# rt10.net
KiCad netlist of a schematic drawn in EAGLE
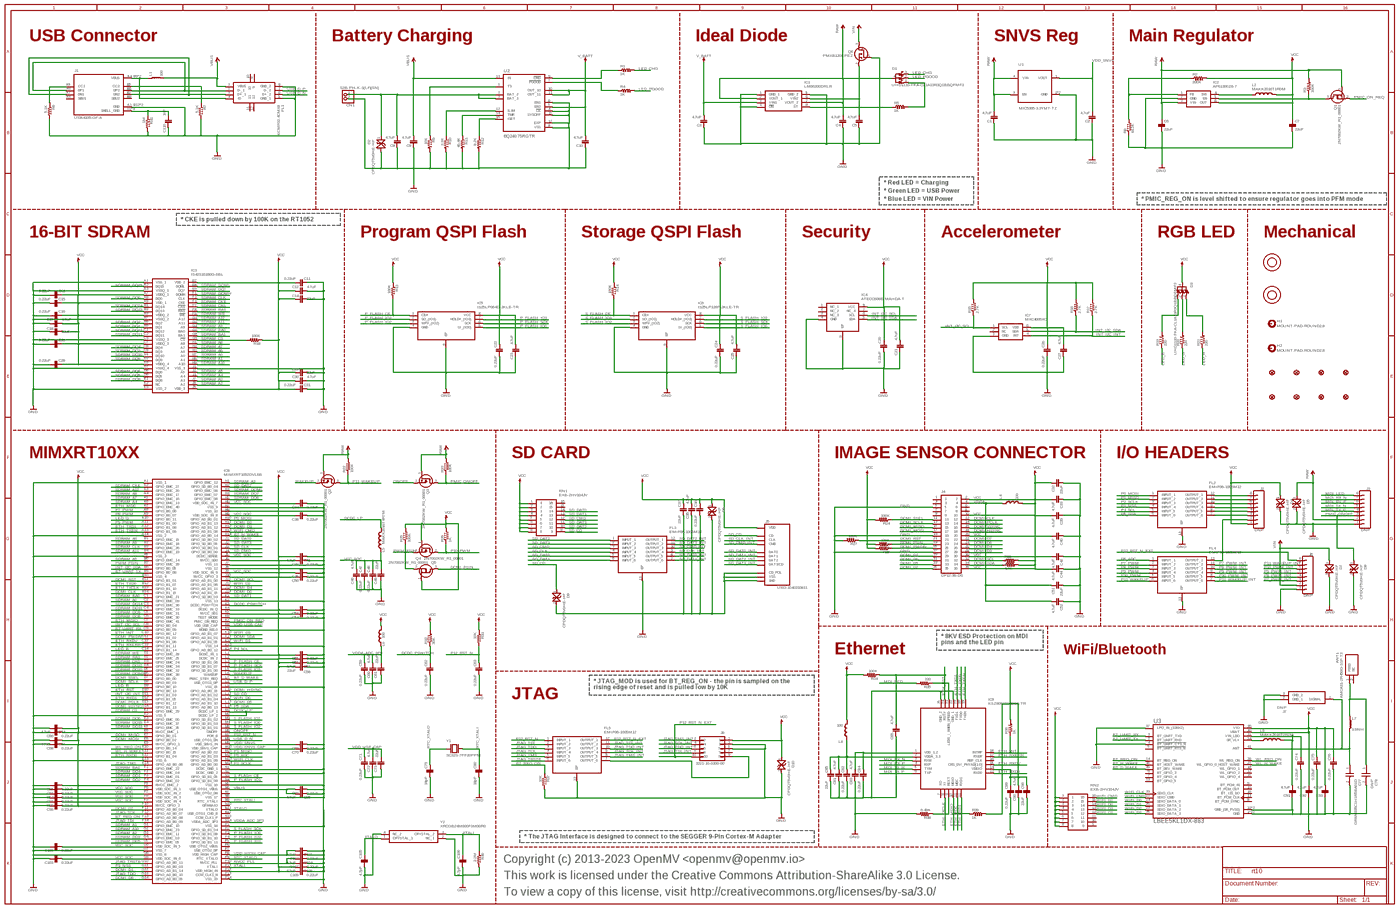
[diagram p0: schematic, sheet 1, overview]
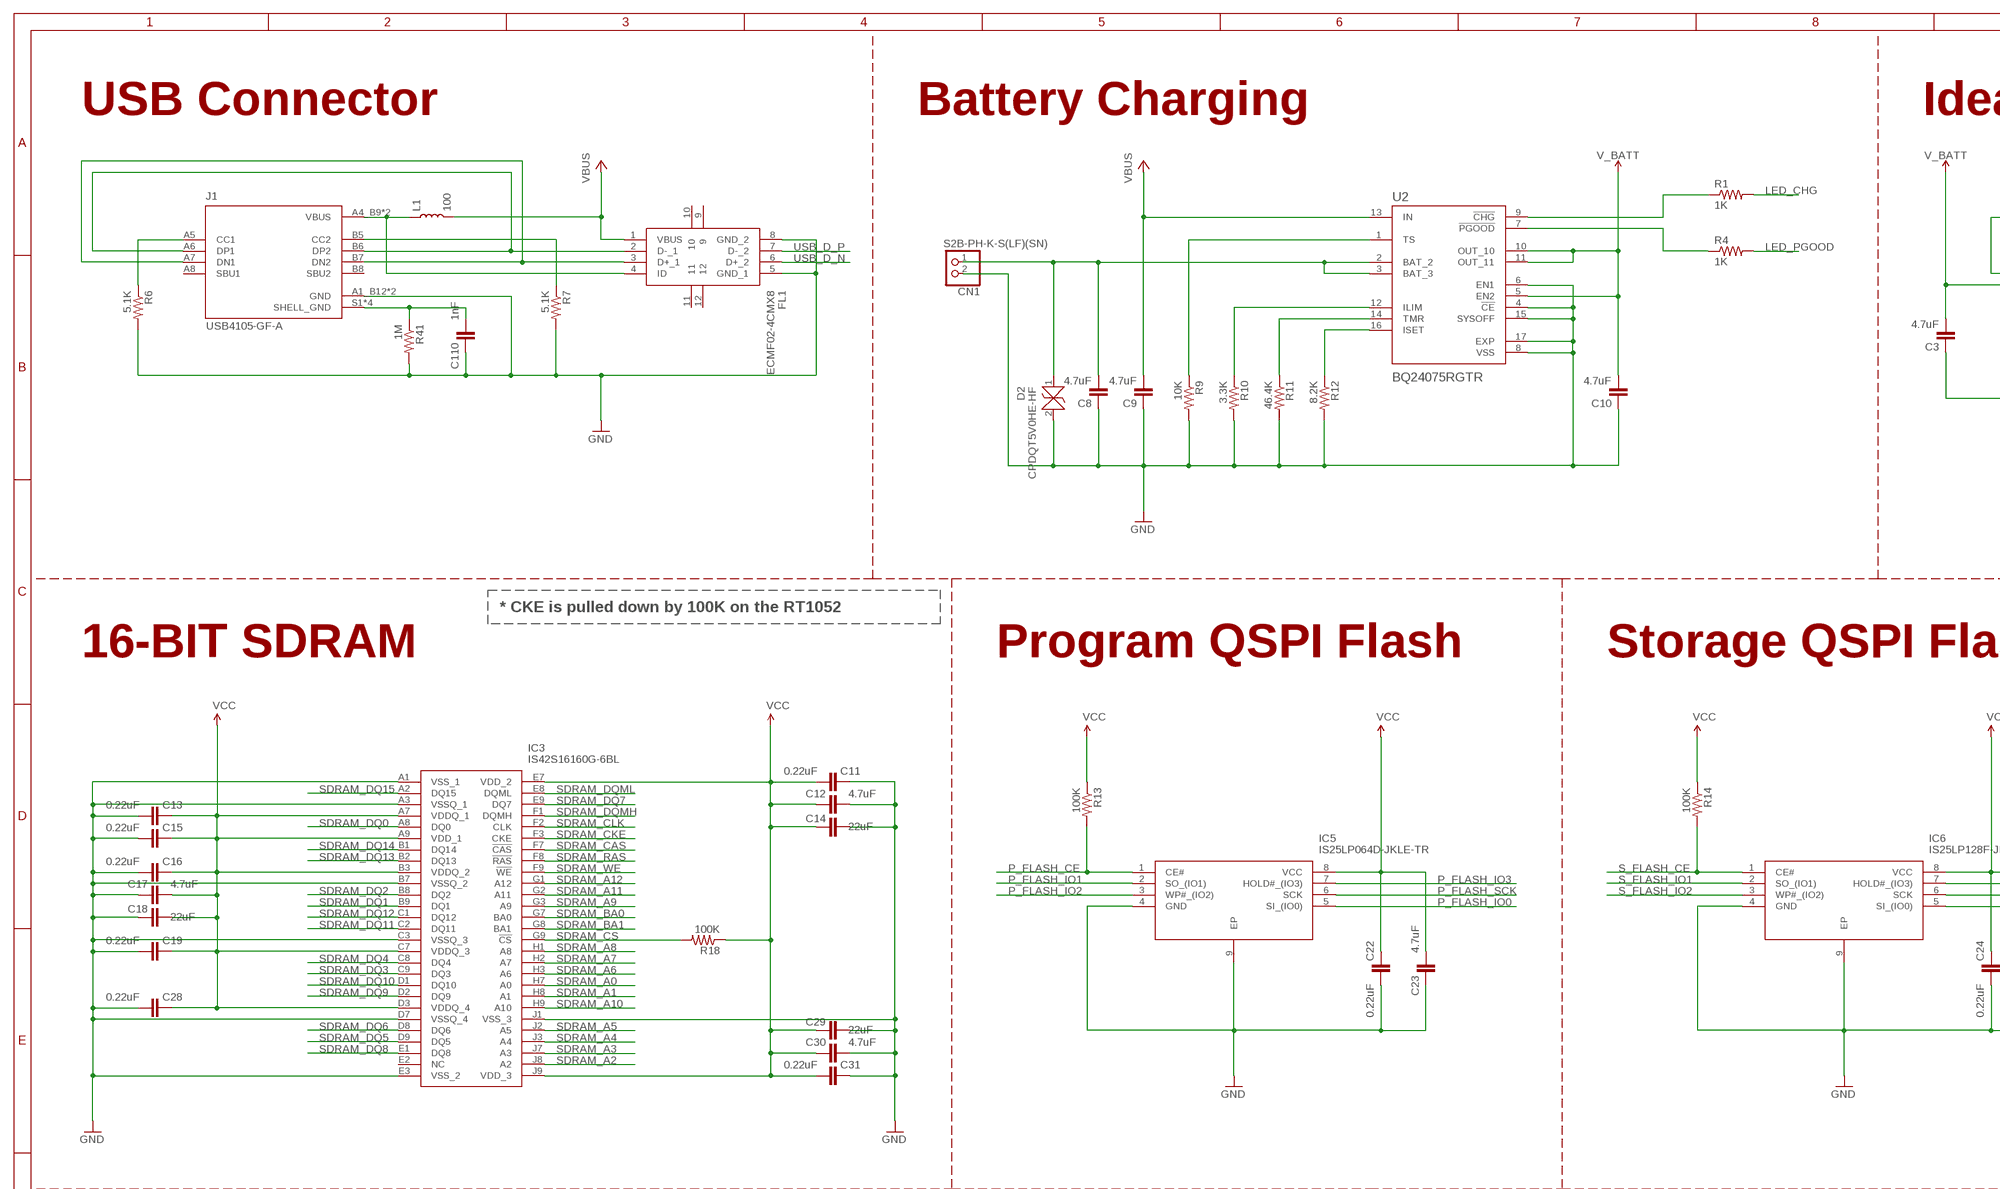
[diagram p1: schematic, sheet 1, part 1 of 4]
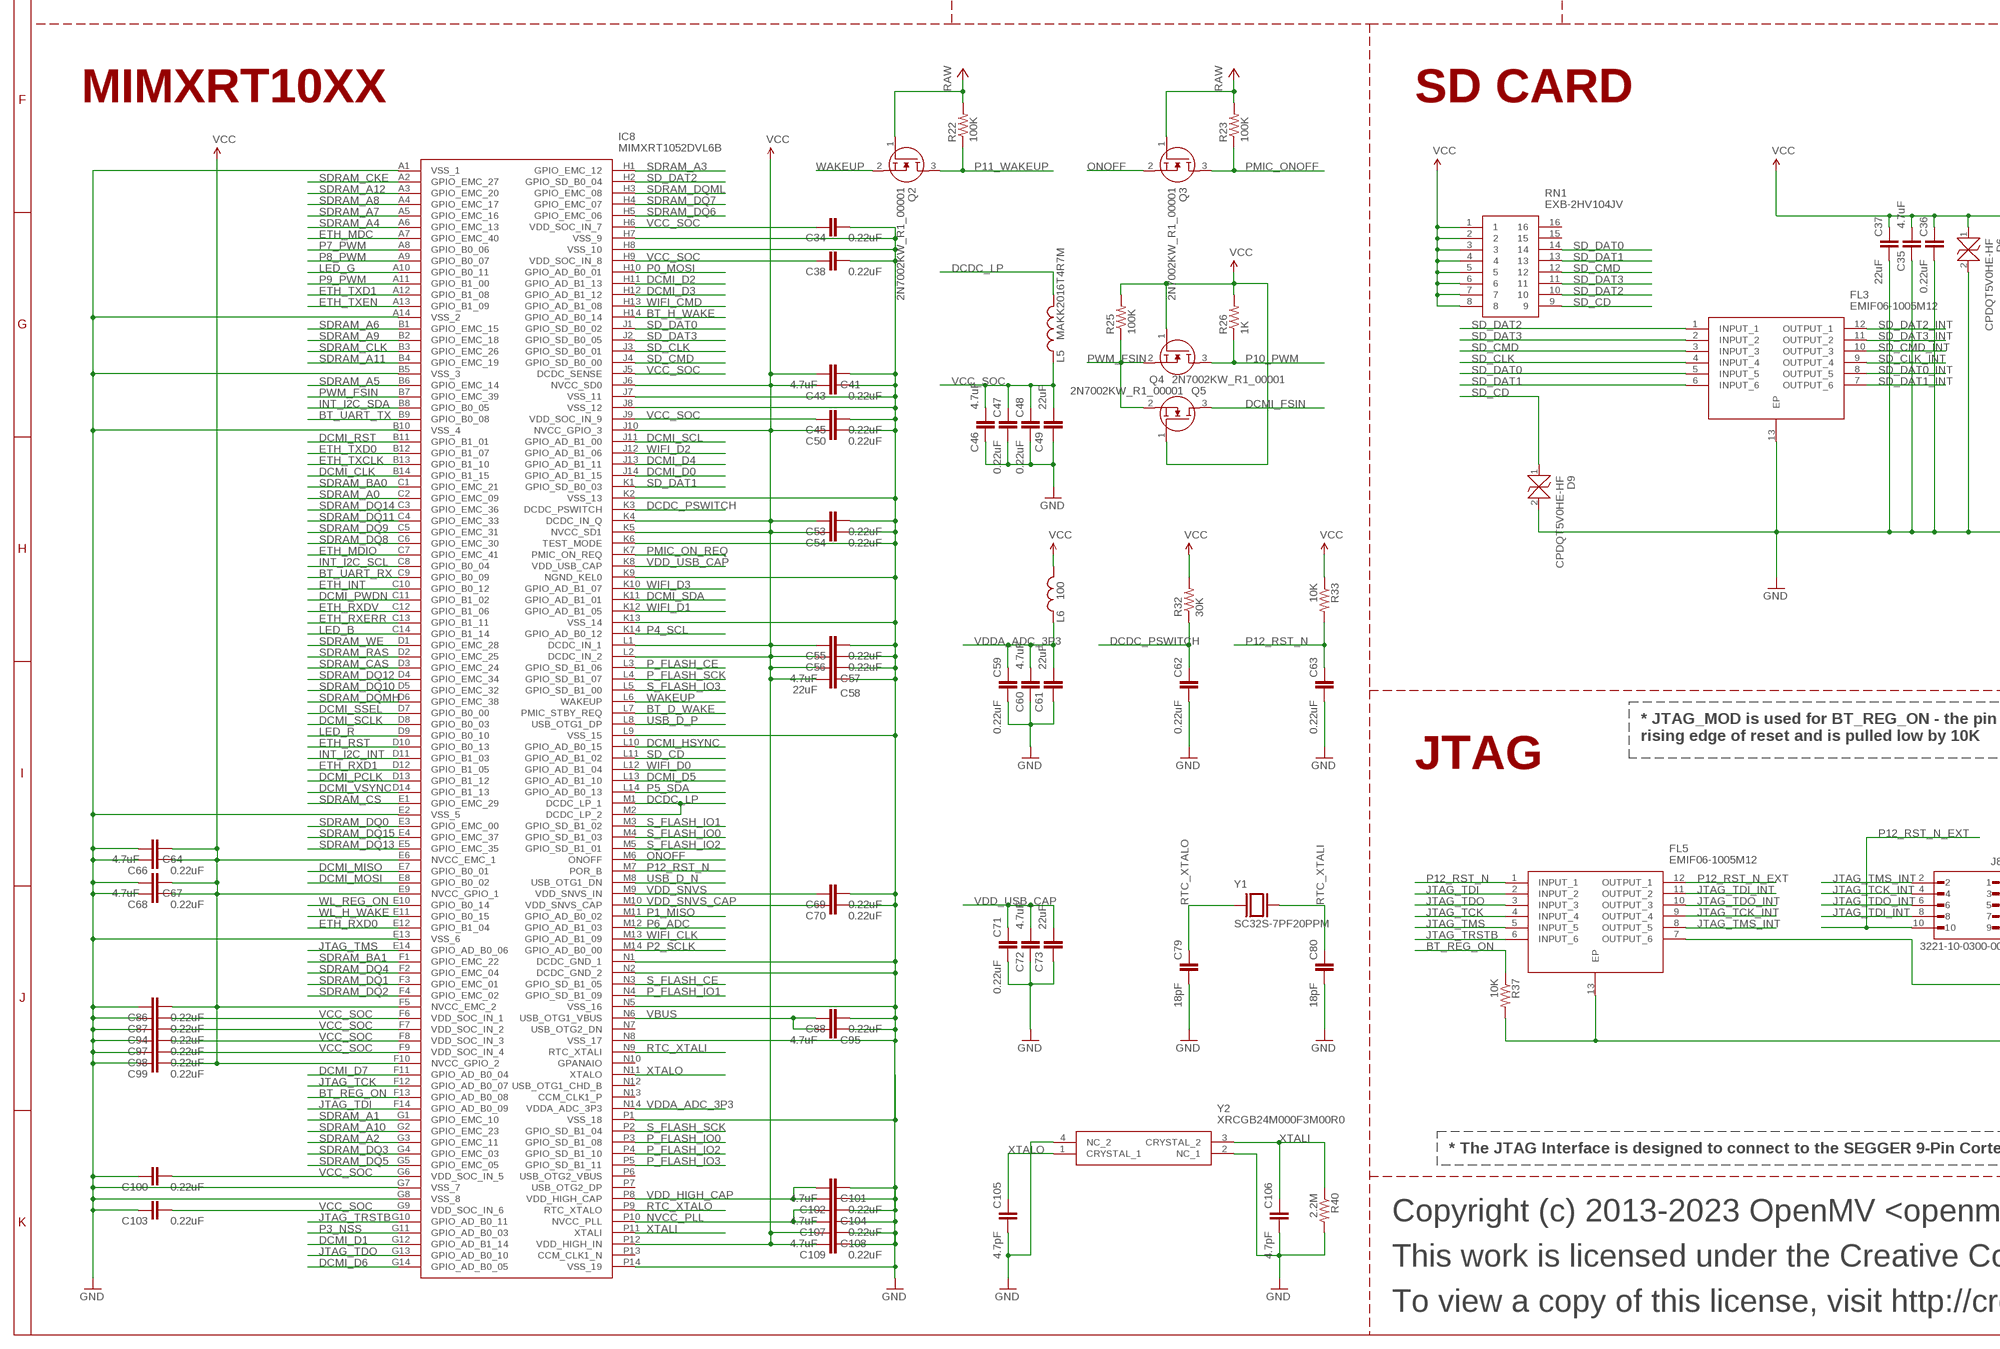
[diagram p2: schematic, sheet 1, part 2 of 4]
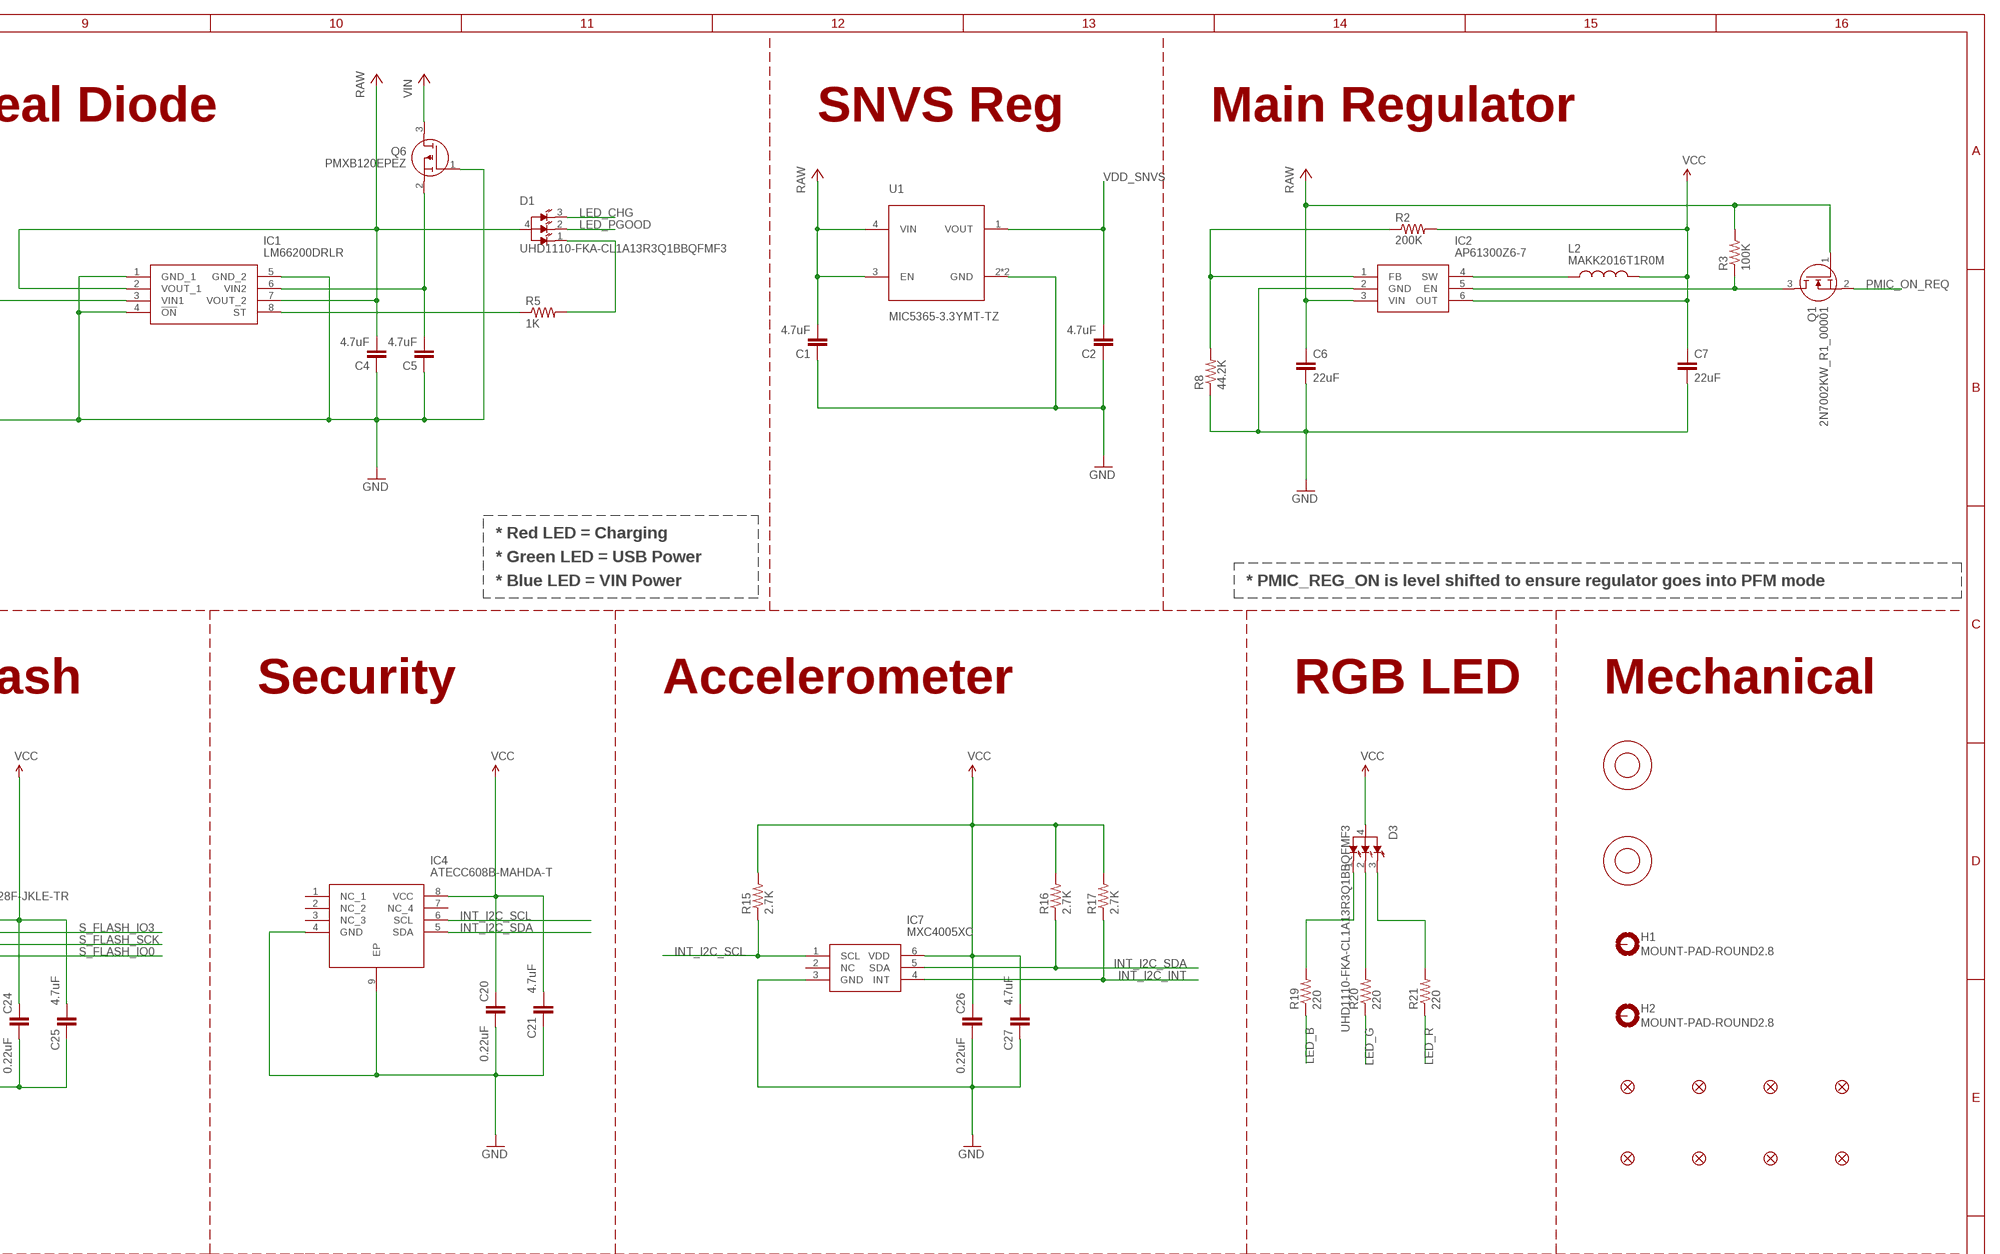
[diagram p3: schematic, sheet 1, part 3 of 4]
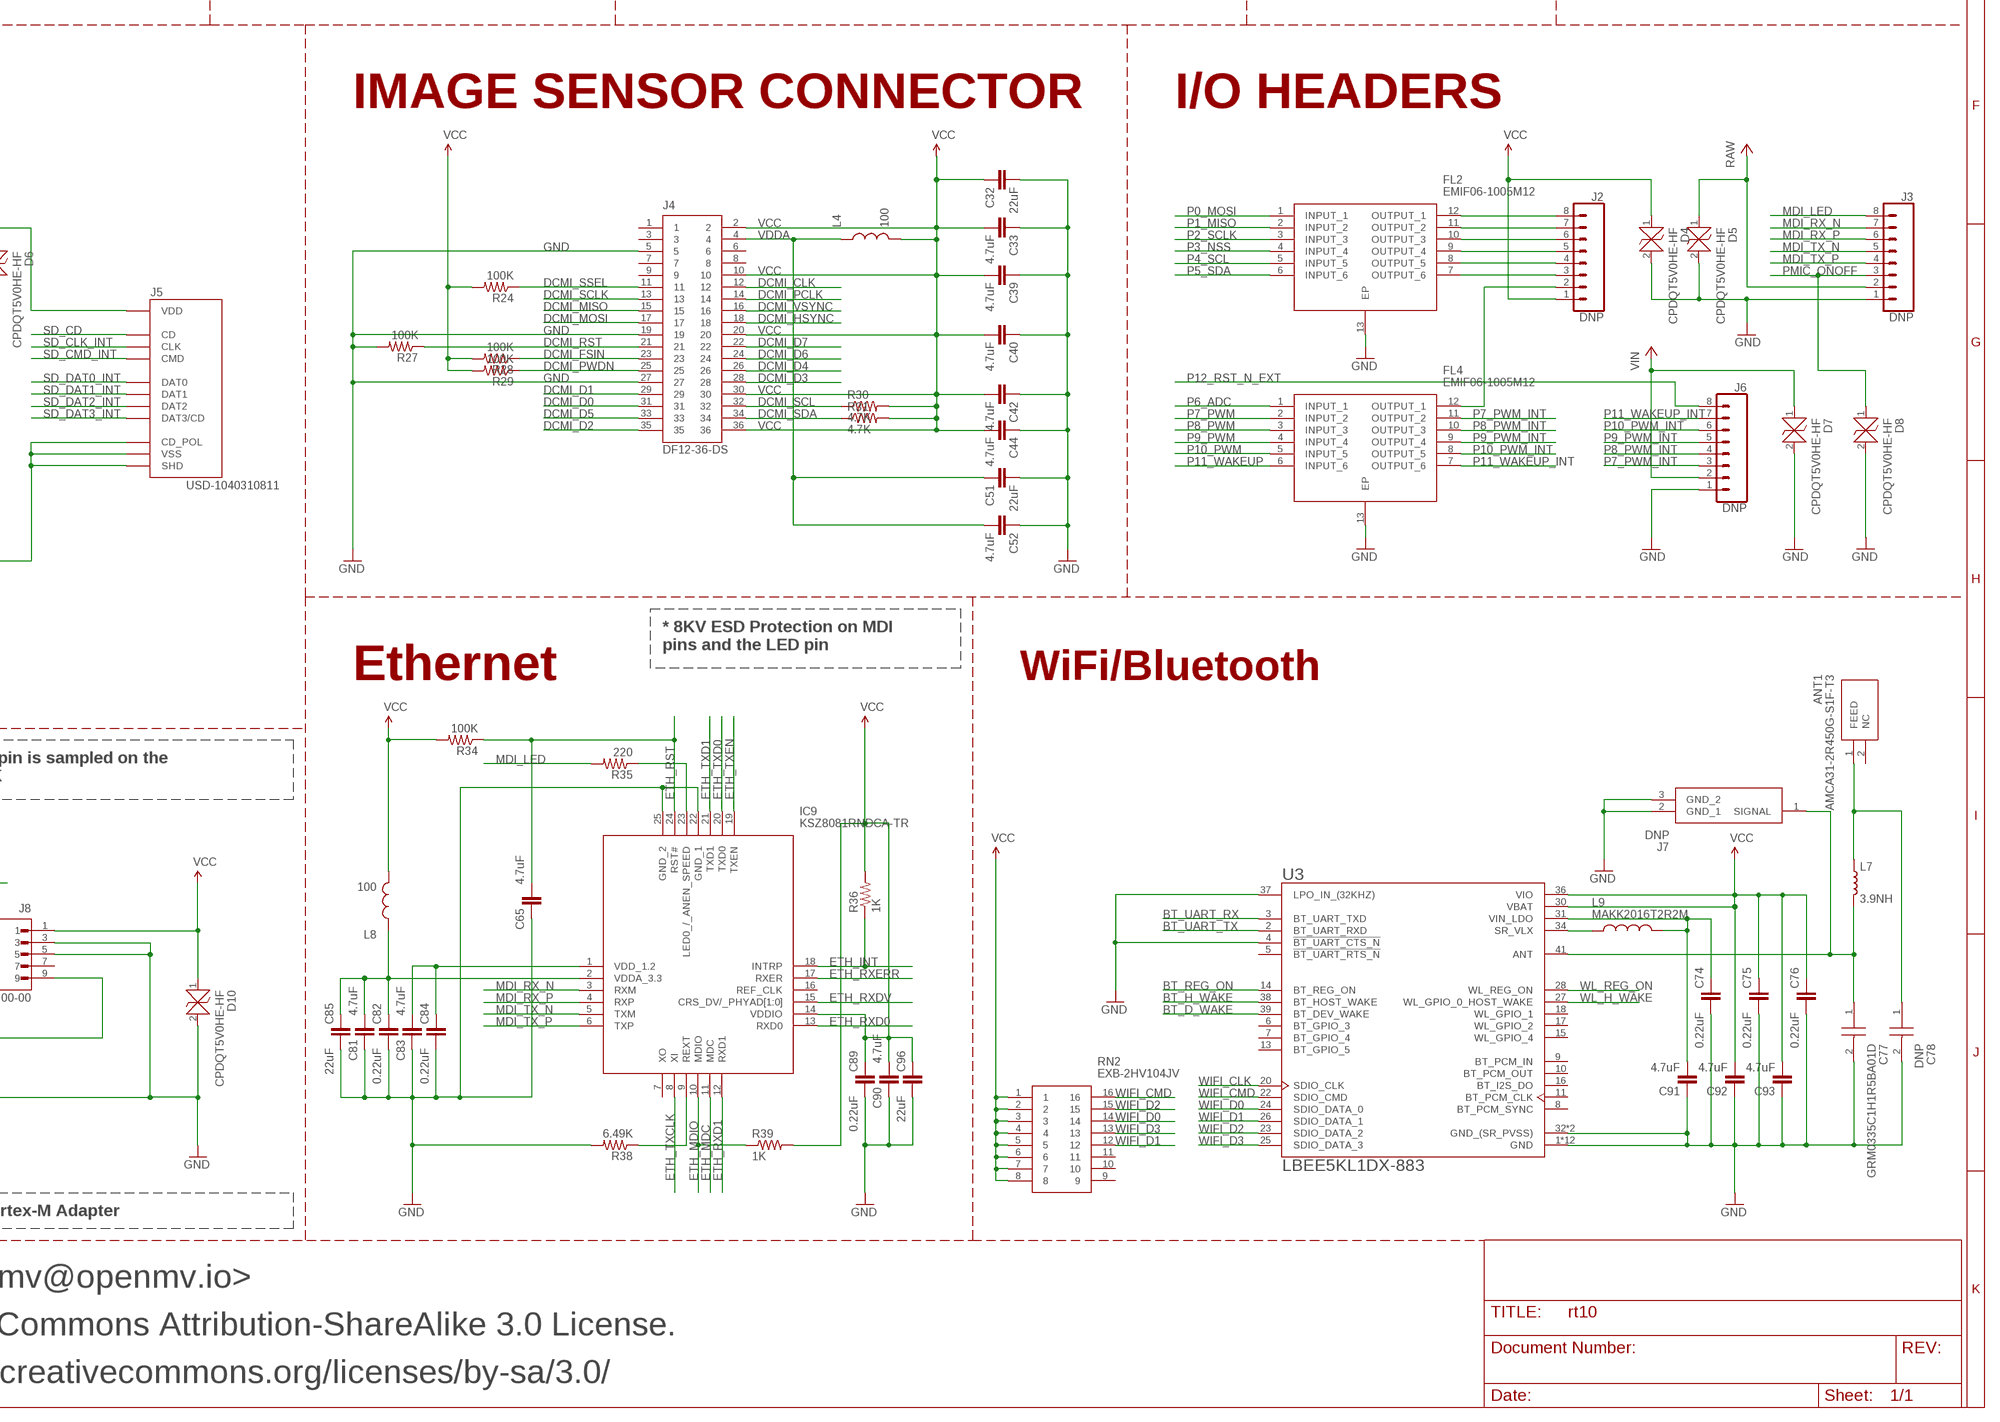
[diagram p4: schematic, sheet 1, part 4 of 4]

(export (version "E")
  (design (tool "Eeschema 10.0.6"))
  (components
    (comp (ref "ANT1")
      (value "AMCA31-2R450G-S1F-T3")
      (footprint "eagle-import:ANTC3216X140N")
      (fields (field (name "MOUSER_PART_NUMBER") "815-CA312R450GS1FT3"))
      (libsource (lib "eagle-import") (part "AMCA31-2R450G-S1F-T3"))
    )
    (comp (ref "C1")
      (value "4.7uF")
      (footprint "eagle-import:0402-CAP")
      (fields (field (name "MPN") "JMK105BBJ475MV-F"))
      (libsource (lib "eagle-import") (part "CAP0402-CAP"))
    )
    (comp (ref "C2")
      (value "4.7uF")
      (footprint "eagle-import:0402-CAP")
      (fields (field (name "MPN") "JMK105BBJ475MV-F"))
      (libsource (lib "eagle-import") (part "CAP0402-CAP"))
    )
    (comp (ref "C3")
      (value "4.7uF")
      (footprint "eagle-import:0402-CAP")
      (fields (field (name "MPN") "JMK105BBJ475MV-F"))
      (libsource (lib "eagle-import") (part "CAP0402-CAP"))
    )
    (comp (ref "C4")
      (value "4.7uF")
      (footprint "eagle-import:0402-CAP")
      (fields (field (name "MPN") "JMK105BBJ475MV-F"))
      (libsource (lib "eagle-import") (part "CAP0402-CAP"))
    )
    (comp (ref "C5")
      (value "4.7uF")
      (footprint "eagle-import:0402-CAP")
      (fields (field (name "MPN") "JMK105BBJ475MV-F"))
      (libsource (lib "eagle-import") (part "CAP0402-CAP"))
    )
    (comp (ref "C6")
      (value "22uF")
      (footprint "eagle-import:0805")
      (fields (field (name "MPN") "CL21A226MQQNNNE"))
      (libsource (lib "eagle-import") (part "22UF-0805-6.3V-20%"))
    )
    (comp (ref "C7")
      (value "22uF")
      (footprint "eagle-import:0805")
      (fields (field (name "MPN") "CL21A226MQQNNNE"))
      (libsource (lib "eagle-import") (part "22UF-0805-6.3V-20%"))
    )
    (comp (ref "C8")
      (value "4.7uF")
      (footprint "eagle-import:0402-CAP")
      (fields (field (name "MPN") "JMK105BBJ475MV-F"))
      (libsource (lib "eagle-import") (part "CAP0402-CAP"))
    )
    (comp (ref "C9")
      (value "4.7uF")
      (footprint "eagle-import:0402-CAP")
      (fields (field (name "MPN") "JMK105BBJ475MV-F"))
      (libsource (lib "eagle-import") (part "CAP0402-CAP"))
    )
    (comp (ref "C10")
      (value "4.7uF")
      (footprint "eagle-import:0402-CAP")
      (fields (field (name "MPN") "JMK105BBJ475MV-F"))
      (libsource (lib "eagle-import") (part "CAP0402-CAP"))
    )
    (comp (ref "C11")
      (value "0.22uF")
      (footprint "eagle-import:C0201")
      (fields (field (name "MPN") "GRM033R60J224ME15D"))
      (libsource (lib "eagle-import") (part "C-EUC0201"))
    )
    (comp (ref "C12")
      (value "4.7uF")
      (footprint "eagle-import:0402-CAP")
      (fields (field (name "MPN") "JMK105BBJ475MV-F"))
      (libsource (lib "eagle-import") (part "CAP0402-CAP"))
    )
    (comp (ref "C13")
      (value "0.22uF")
      (footprint "eagle-import:C0201")
      (fields (field (name "MPN") "GRM033R60J224ME15D"))
      (libsource (lib "eagle-import") (part "C-EUC0201"))
    )
    (comp (ref "C14")
      (value "22uF")
      (footprint "eagle-import:0805")
      (fields (field (name "MPN") "CL21A226MQQNNNE"))
      (libsource (lib "eagle-import") (part "22UF-0805-6.3V-20%"))
    )
    (comp (ref "C15")
      (value "0.22uF")
      (footprint "eagle-import:C0201")
      (fields (field (name "MPN") "GRM033R60J224ME15D"))
      (libsource (lib "eagle-import") (part "C-EUC0201"))
    )
    (comp (ref "C16")
      (value "0.22uF")
      (footprint "eagle-import:C0201")
      (fields (field (name "MPN") "GRM033R60J224ME15D"))
      (libsource (lib "eagle-import") (part "C-EUC0201"))
    )
    (comp (ref "C17")
      (value "4.7uF")
      (footprint "eagle-import:0402-CAP")
      (fields (field (name "MPN") "JMK105BBJ475MV-F"))
      (libsource (lib "eagle-import") (part "CAP0402-CAP"))
    )
    (comp (ref "C18")
      (value "22uF")
      (footprint "eagle-import:0805")
      (fields (field (name "MPN") "CL21A226MQQNNNE"))
      (libsource (lib "eagle-import") (part "22UF-0805-6.3V-20%"))
    )
    (comp (ref "C19")
      (value "0.22uF")
      (footprint "eagle-import:C0201")
      (fields (field (name "MPN") "GRM033R60J224ME15D"))
      (libsource (lib "eagle-import") (part "C-EUC0201"))
    )
    (comp (ref "C20")
      (value "0.22uF")
      (footprint "eagle-import:C0201")
      (fields (field (name "MPN") "GRM033R60J224ME15D"))
      (libsource (lib "eagle-import") (part "C-EUC0201"))
    )
    (comp (ref "C21")
      (value "4.7uF")
      (footprint "eagle-import:0402-CAP")
      (fields (field (name "MPN") "JMK105BBJ475MV-F"))
      (libsource (lib "eagle-import") (part "CAP0402-CAP"))
    )
    (comp (ref "C22")
      (value "0.22uF")
      (footprint "eagle-import:C0201")
      (fields (field (name "MPN") "GRM033R60J224ME15D"))
      (libsource (lib "eagle-import") (part "C-EUC0201"))
    )
    (comp (ref "C23")
      (value "4.7uF")
      (footprint "eagle-import:0402-CAP")
      (fields (field (name "MPN") "JMK105BBJ475MV-F"))
      (libsource (lib "eagle-import") (part "CAP0402-CAP"))
    )
    (comp (ref "C24")
      (value "0.22uF")
      (footprint "eagle-import:C0201")
      (fields (field (name "MPN") "GRM033R60J224ME15D"))
      (libsource (lib "eagle-import") (part "C-EUC0201"))
    )
    (comp (ref "C25")
      (value "4.7uF")
      (footprint "eagle-import:0402-CAP")
      (fields (field (name "MPN") "JMK105BBJ475MV-F"))
      (libsource (lib "eagle-import") (part "CAP0402-CAP"))
    )
    (comp (ref "C26")
      (value "0.22uF")
      (footprint "eagle-import:C0201")
      (fields (field (name "MPN") "GRM033R60J224ME15D"))
      (libsource (lib "eagle-import") (part "C-EUC0201"))
    )
    (comp (ref "C27")
      (value "4.7uF")
      (footprint "eagle-import:0402-CAP")
      (fields (field (name "MPN") "JMK105BBJ475MV-F"))
      (libsource (lib "eagle-import") (part "CAP0402-CAP"))
    )
    (comp (ref "C28")
      (value "0.22uF")
      (footprint "eagle-import:C0201")
      (fields (field (name "MPN") "GRM033R60J224ME15D"))
      (libsource (lib "eagle-import") (part "C-EUC0201"))
    )
    (comp (ref "C29")
      (value "22uF")
      (footprint "eagle-import:0805")
      (fields (field (name "MPN") "CL21A226MQQNNNE"))
      (libsource (lib "eagle-import") (part "22UF-0805-6.3V-20%"))
    )
    (comp (ref "C30")
      (value "4.7uF")
      (footprint "eagle-import:0402-CAP")
      (fields (field (name "MPN") "JMK105BBJ475MV-F"))
      (libsource (lib "eagle-import") (part "CAP0402-CAP"))
    )
    (comp (ref "C31")
      (value "0.22uF")
      (footprint "eagle-import:C0201")
      (fields (field (name "MPN") "GRM033R60J224ME15D"))
      (libsource (lib "eagle-import") (part "C-EUC0201"))
    )
    (comp (ref "C32")
      (value "22uF")
      (footprint "eagle-import:0805")
      (fields (field (name "MPN") "CL21A226MQQNNNE"))
      (libsource (lib "eagle-import") (part "22UF-0805-6.3V-20%"))
    )
    (comp (ref "C33")
      (value "4.7uF")
      (footprint "eagle-import:0402-CAP")
      (fields (field (name "MPN") "JMK105BBJ475MV-F"))
      (libsource (lib "eagle-import") (part "CAP0402-CAP"))
    )
    (comp (ref "C34")
      (value "0.22uF")
      (footprint "eagle-import:C0201")
      (fields (field (name "MPN") "GRM033R60J224ME15D"))
      (libsource (lib "eagle-import") (part "C-EUC0201"))
    )
    (comp (ref "C35")
      (value "4.7uF")
      (footprint "eagle-import:0402-CAP")
      (fields (field (name "MPN") "JMK105BBJ475MV-F"))
      (libsource (lib "eagle-import") (part "CAP0402-CAP"))
    )
    (comp (ref "C36")
      (value "0.22uF")
      (footprint "eagle-import:C0201")
      (fields (field (name "MPN") "GRM033R60J224ME15D"))
      (libsource (lib "eagle-import") (part "C-EUC0201"))
    )
    (comp (ref "C37")
      (value "22uF")
      (footprint "eagle-import:0805")
      (fields (field (name "MPN") "CL21A226MQQNNNE"))
      (libsource (lib "eagle-import") (part "22UF-0805-6.3V-20%"))
    )
    (comp (ref "C38")
      (value "0.22uF")
      (footprint "eagle-import:C0201")
      (fields (field (name "MPN") "GRM033R60J224ME15D"))
      (libsource (lib "eagle-import") (part "C-EUC0201"))
    )
    (comp (ref "C39")
      (value "4.7uF")
      (footprint "eagle-import:0402-CAP")
      (fields (field (name "MPN") "JMK105BBJ475MV-F"))
      (libsource (lib "eagle-import") (part "CAP0402-CAP"))
    )
    (comp (ref "C40")
      (value "4.7uF")
      (footprint "eagle-import:0402-CAP")
      (fields (field (name "MPN") "JMK105BBJ475MV-F"))
      (libsource (lib "eagle-import") (part "CAP0402-CAP"))
    )
    (comp (ref "C41")
      (value "4.7uF")
      (footprint "eagle-import:0402-CAP")
      (fields (field (name "MPN") "JMK105BBJ475MV-F"))
      (libsource (lib "eagle-import") (part "CAP0402-CAP"))
    )
    (comp (ref "C42")
      (value "4.7uF")
      (footprint "eagle-import:0402-CAP")
      (fields (field (name "MPN") "JMK105BBJ475MV-F"))
      (libsource (lib "eagle-import") (part "CAP0402-CAP"))
    )
    (comp (ref "C43")
      (value "0.22uF")
      (footprint "eagle-import:C0201")
      (fields (field (name "MPN") "GRM033R60J224ME15D"))
      (libsource (lib "eagle-import") (part "C-EUC0201"))
    )
    (comp (ref "C44")
      (value "4.7uF")
      (footprint "eagle-import:0402-CAP")
      (fields (field (name "MPN") "JMK105BBJ475MV-F"))
      (libsource (lib "eagle-import") (part "CAP0402-CAP"))
    )
    (comp (ref "C45")
      (value "0.22uF")
      (footprint "eagle-import:C0201")
      (fields (field (name "MPN") "GRM033R60J224ME15D"))
      (libsource (lib "eagle-import") (part "C-EUC0201"))
    )
    (comp (ref "C46")
      (value "4.7uF")
      (footprint "eagle-import:0402-CAP")
      (fields (field (name "MPN") "JMK105BBJ475MV-F"))
      (libsource (lib "eagle-import") (part "CAP0402-CAP"))
    )
    (comp (ref "C47")
      (value "0.22uF")
      (footprint "eagle-import:C0201")
      (fields (field (name "MPN") "GRM033R60J224ME15D"))
      (libsource (lib "eagle-import") (part "C-EUC0201"))
    )
    (comp (ref "C48")
      (value "0.22uF")
      (footprint "eagle-import:C0201")
      (fields (field (name "MPN") "GRM033R60J224ME15D"))
      (libsource (lib "eagle-import") (part "C-EUC0201"))
    )
    (comp (ref "C49")
      (value "22uF")
      (footprint "eagle-import:0805")
      (fields (field (name "MPN") "CL21A226MQQNNNE"))
      (libsource (lib "eagle-import") (part "22UF-0805-6.3V-20%"))
    )
    (comp (ref "C50")
      (value "0.22uF")
      (footprint "eagle-import:C0201")
      (fields (field (name "MPN") "GRM033R60J224ME15D"))
      (libsource (lib "eagle-import") (part "C-EUC0201"))
    )
    (comp (ref "C51")
      (value "22uF")
      (footprint "eagle-import:0805")
      (fields (field (name "MPN") "CL21A226MQQNNNE"))
      (libsource (lib "eagle-import") (part "22UF-0805-6.3V-20%"))
    )
    (comp (ref "C52")
      (value "4.7uF")
      (footprint "eagle-import:0402-CAP")
      (fields (field (name "MPN") "JMK105BBJ475MV-F"))
      (libsource (lib "eagle-import") (part "CAP0402-CAP"))
    )
    (comp (ref "C53")
      (value "0.22uF")
      (footprint "eagle-import:C0201")
      (fields (field (name "MPN") "GRM033R60J224ME15D"))
      (libsource (lib "eagle-import") (part "C-EUC0201"))
    )
    (comp (ref "C54")
      (value "0.22uF")
      (footprint "eagle-import:C0201")
      (fields (field (name "MPN") "GRM033R60J224ME15D"))
      (libsource (lib "eagle-import") (part "C-EUC0201"))
    )
    (comp (ref "C55")
      (value "0.22uF")
      (footprint "eagle-import:C0201")
      (fields (field (name "MPN") "GRM033R60J224ME15D"))
      (libsource (lib "eagle-import") (part "C-EUC0201"))
    )
    (comp (ref "C56")
      (value "0.22uF")
      (footprint "eagle-import:C0201")
      (fields (field (name "MPN") "GRM033R60J224ME15D"))
      (libsource (lib "eagle-import") (part "C-EUC0201"))
    )
    (comp (ref "C57")
      (value "4.7uF")
      (footprint "eagle-import:0402-CAP")
      (fields (field (name "MPN") "JMK105BBJ475MV-F"))
      (libsource (lib "eagle-import") (part "CAP0402-CAP"))
    )
    (comp (ref "C58")
      (value "22uF")
      (footprint "eagle-import:0805")
      (fields (field (name "MPN") "CL21A226MQQNNNE"))
      (libsource (lib "eagle-import") (part "22UF-0805-6.3V-20%"))
    )
    (comp (ref "C59")
      (value "0.22uF")
      (footprint "eagle-import:C0201")
      (fields (field (name "MPN") "GRM033R60J224ME15D"))
      (libsource (lib "eagle-import") (part "C-EUC0201"))
    )
    (comp (ref "C60")
      (value "4.7uF")
      (footprint "eagle-import:0402-CAP")
      (fields (field (name "MPN") "JMK105BBJ475MV-F"))
      (libsource (lib "eagle-import") (part "CAP0402-CAP"))
    )
    (comp (ref "C61")
      (value "22uF")
      (footprint "eagle-import:0805")
      (fields (field (name "MPN") "CL21A226MQQNNNE"))
      (libsource (lib "eagle-import") (part "22UF-0805-6.3V-20%"))
    )
    (comp (ref "C62")
      (value "0.22uF")
      (footprint "eagle-import:C0201")
      (fields (field (name "MPN") "GRM033R60J224ME15D"))
      (libsource (lib "eagle-import") (part "C-EUC0201"))
    )
    (comp (ref "C63")
      (value "0.22uF")
      (footprint "eagle-import:C0201")
      (fields (field (name "MPN") "GRM033R60J224ME15D"))
      (libsource (lib "eagle-import") (part "C-EUC0201"))
    )
    (comp (ref "C64")
      (value "4.7uF")
      (footprint "eagle-import:0402-CAP")
      (fields (field (name "MPN") "JMK105BBJ475MV-F"))
      (libsource (lib "eagle-import") (part "CAP0402-CAP"))
    )
    (comp (ref "C65")
      (value "4.7uF")
      (footprint "eagle-import:0402-CAP")
      (fields (field (name "MPN") "JMK105BBJ475MV-F"))
      (libsource (lib "eagle-import") (part "CAP0402-CAP"))
    )
    (comp (ref "C66")
      (value "0.22uF")
      (footprint "eagle-import:C0201")
      (fields (field (name "MPN") "GRM033R60J224ME15D"))
      (libsource (lib "eagle-import") (part "C-EUC0201"))
    )
    (comp (ref "C67")
      (value "4.7uF")
      (footprint "eagle-import:0402-CAP")
      (fields (field (name "MPN") "JMK105BBJ475MV-F"))
      (libsource (lib "eagle-import") (part "CAP0402-CAP"))
    )
    (comp (ref "C68")
      (value "0.22uF")
      (footprint "eagle-import:C0201")
      (fields (field (name "MPN") "GRM033R60J224ME15D"))
      (libsource (lib "eagle-import") (part "C-EUC0201"))
    )
    (comp (ref "C69")
      (value "0.22uF")
      (footprint "eagle-import:C0201")
      (fields (field (name "MPN") "GRM033R60J224ME15D"))
      (libsource (lib "eagle-import") (part "C-EUC0201"))
    )
    (comp (ref "C70")
      (value "0.22uF")
      (footprint "eagle-import:C0201")
      (fields (field (name "MPN") "GRM033R60J224ME15D"))
      (libsource (lib "eagle-import") (part "C-EUC0201"))
    )
    (comp (ref "C71")
      (value "0.22uF")
      (footprint "eagle-import:C0201")
      (fields (field (name "MPN") "GRM033R60J224ME15D"))
      (libsource (lib "eagle-import") (part "C-EUC0201"))
    )
    (comp (ref "C72")
      (value "4.7uF")
      (footprint "eagle-import:0402-CAP")
      (fields (field (name "MPN") "JMK105BBJ475MV-F"))
      (libsource (lib "eagle-import") (part "CAP0402-CAP"))
    )
    (comp (ref "C73")
      (value "22uF")
      (footprint "eagle-import:0805")
      (fields (field (name "MPN") "CL21A226MQQNNNE"))
      (libsource (lib "eagle-import") (part "22UF-0805-6.3V-20%"))
    )
    (comp (ref "C74")
      (value "0.22uF")
      (footprint "eagle-import:C0201")
      (fields (field (name "MPN") "GRM033R60J224ME15D"))
      (libsource (lib "eagle-import") (part "C-EUC0201"))
    )
    (comp (ref "C75")
      (value "0.22uF")
      (footprint "eagle-import:C0201")
      (fields (field (name "MPN") "GRM033R60J224ME15D"))
      (libsource (lib "eagle-import") (part "C-EUC0201"))
    )
    (comp (ref "C76")
      (value "0.22uF")
      (footprint "eagle-import:C0201")
      (fields (field (name "MPN") "GRM033R60J224ME15D"))
      (libsource (lib "eagle-import") (part "C-EUC0201"))
    )
    (comp (ref "C77")
      (value "GRM0335C1H1R5BA01D")
      (footprint "eagle-import:CAPC0603X33N")
      (fields (field (name "MOUSER_PART_NUMBER") "81-GRM0335C1H1R5BA1D"))
      (libsource (lib "eagle-import") (part "GRM0335C1H1R5BA01D"))
    )
    (comp (ref "C78")
      (value "DNP")
      (footprint "eagle-import:CAPC0603X33N")
      (fields
        (field (name "MANUFACTURER_PART_NUMBER") "GRM0335C1H1R5BA01D")
        (field (name "MOUSER_PART_NUMBER") "81-GRM0335C1H1R5BA1D")
      )
      (libsource (lib "eagle-import") (part "GRM0335C1H1R5BA01D"))
    )
    (comp (ref "C79")
      (value "18pF")
      (footprint "eagle-import:C0201")
      (fields (field (name "MPN") "GRM0335C1E180JA01D"))
      (libsource (lib "eagle-import") (part "C-EUC0201"))
    )
    (comp (ref "C80")
      (value "18pF")
      (footprint "eagle-import:C0201")
      (fields (field (name "MPN") "GRM0335C1E180JA01D"))
      (libsource (lib "eagle-import") (part "C-EUC0201"))
    )
    (comp (ref "C81")
      (value "4.7uF")
      (footprint "eagle-import:0402-CAP")
      (fields (field (name "MPN") "JMK105BBJ475MV-F"))
      (libsource (lib "eagle-import") (part "CAP0402-CAP"))
    )
    (comp (ref "C82")
      (value "0.22uF")
      (footprint "eagle-import:C0201")
      (fields (field (name "MPN") "GRM033R60J224ME15D"))
      (libsource (lib "eagle-import") (part "C-EUC0201"))
    )
    (comp (ref "C83")
      (value "4.7uF")
      (footprint "eagle-import:0402-CAP")
      (fields (field (name "MPN") "JMK105BBJ475MV-F"))
      (libsource (lib "eagle-import") (part "CAP0402-CAP"))
    )
    (comp (ref "C84")
      (value "0.22uF")
      (footprint "eagle-import:C0201")
      (fields (field (name "MPN") "GRM033R60J224ME15D"))
      (libsource (lib "eagle-import") (part "C-EUC0201"))
    )
    (comp (ref "C85")
      (value "22uF")
      (footprint "eagle-import:0805")
      (fields (field (name "MPN") "CL21A226MQQNNNE"))
      (libsource (lib "eagle-import") (part "22UF-0805-6.3V-20%"))
    )
    (comp (ref "C86")
      (value "0.22uF")
      (footprint "eagle-import:C0201")
      (fields (field (name "MPN") "GRM033R60J224ME15D"))
      (libsource (lib "eagle-import") (part "C-EUC0201"))
    )
    (comp (ref "C87")
      (value "0.22uF")
      (footprint "eagle-import:C0201")
      (fields (field (name "MPN") "GRM033R60J224ME15D"))
      (libsource (lib "eagle-import") (part "C-EUC0201"))
    )
    (comp (ref "C88")
      (value "0.22uF")
      (footprint "eagle-import:C0201")
      (fields (field (name "MPN") "GRM033R60J224ME15D"))
      (libsource (lib "eagle-import") (part "C-EUC0201"))
    )
    (comp (ref "C89")
      (value "0.22uF")
      (footprint "eagle-import:C0201")
      (fields (field (name "MPN") "GRM033R60J224ME15D"))
      (libsource (lib "eagle-import") (part "C-EUC0201"))
    )
    (comp (ref "C90")
      (value "4.7uF")
      (footprint "eagle-import:0402-CAP")
      (fields (field (name "MPN") "JMK105BBJ475MV-F"))
      (libsource (lib "eagle-import") (part "CAP0402-CAP"))
    )
    (comp (ref "C91")
      (value "4.7uF")
      (footprint "eagle-import:0402-CAP")
      (fields (field (name "MPN") "JMK105BBJ475MV-F"))
      (libsource (lib "eagle-import") (part "CAP0402-CAP"))
    )
    (comp (ref "C92")
      (value "4.7uF")
      (footprint "eagle-import:0402-CAP")
      (fields (field (name "MPN") "JMK105BBJ475MV-F"))
      (libsource (lib "eagle-import") (part "CAP0402-CAP"))
    )
    (comp (ref "C93")
      (value "4.7uF")
      (footprint "eagle-import:0402-CAP")
      (fields (field (name "MPN") "JMK105BBJ475MV-F"))
      (libsource (lib "eagle-import") (part "CAP0402-CAP"))
    )
    (comp (ref "C94")
      (value "0.22uF")
      (footprint "eagle-import:C0201")
      (fields (field (name "MPN") "GRM033R60J224ME15D"))
      (libsource (lib "eagle-import") (part "C-EUC0201"))
    )
    (comp (ref "C95")
      (value "4.7uF")
      (footprint "eagle-import:0402-CAP")
      (fields (field (name "MPN") "JMK105BBJ475MV-F"))
      (libsource (lib "eagle-import") (part "CAP0402-CAP"))
    )
    (comp (ref "C96")
      (value "22uF")
      (footprint "eagle-import:0805")
      (fields (field (name "MPN") "CL21A226MQQNNNE"))
      (libsource (lib "eagle-import") (part "22UF-0805-6.3V-20%"))
    )
    (comp (ref "C97")
      (value "0.22uF")
      (footprint "eagle-import:C0201")
      (fields (field (name "MPN") "GRM033R60J224ME15D"))
      (libsource (lib "eagle-import") (part "C-EUC0201"))
    )
    (comp (ref "C98")
      (value "0.22uF")
      (footprint "eagle-import:C0201")
      (fields (field (name "MPN") "GRM033R60J224ME15D"))
      (libsource (lib "eagle-import") (part "C-EUC0201"))
    )
    (comp (ref "C99")
      (value "0.22uF")
      (footprint "eagle-import:C0201")
      (fields (field (name "MPN") "GRM033R60J224ME15D"))
      (libsource (lib "eagle-import") (part "C-EUC0201"))
    )
    (comp (ref "C100")
      (value "0.22uF")
      (footprint "eagle-import:C0201")
      (fields (field (name "MPN") "GRM033R60J224ME15D"))
      (libsource (lib "eagle-import") (part "C-EUC0201"))
    )
    (comp (ref "C101")
      (value "4.7uF")
      (footprint "eagle-import:0402-CAP")
      (fields (field (name "MPN") "JMK105BBJ475MV-F"))
      (libsource (lib "eagle-import") (part "CAP0402-CAP"))
    )
    (comp (ref "C102")
      (value "0.22uF")
      (footprint "eagle-import:C0201")
      (fields (field (name "MPN") "GRM033R60J224ME15D"))
      (libsource (lib "eagle-import") (part "C-EUC0201"))
    )
    (comp (ref "C103")
      (value "0.22uF")
      (footprint "eagle-import:C0201")
      (fields (field (name "MPN") "GRM033R60J224ME15D"))
      (libsource (lib "eagle-import") (part "C-EUC0201"))
    )
    (comp (ref "C104")
      (value "4.7uF")
      (footprint "eagle-import:0402-CAP")
      (fields (field (name "MPN") "JMK105BBJ475MV-F"))
      (libsource (lib "eagle-import") (part "CAP0402-CAP"))
    )
    (comp (ref "C105")
      (value "4.7pF")
      (footprint "eagle-import:C0201")
      (fields (field (name "MPN") "GRM0335C1E4R7CA01D"))
      (libsource (lib "eagle-import") (part "C-EUC0201"))
    )
    (comp (ref "C106")
      (value "4.7pF")
      (footprint "eagle-import:C0201")
      (fields (field (name "MPN") "GRM0335C1E4R7CA01D"))
      (libsource (lib "eagle-import") (part "C-EUC0201"))
    )
    (comp (ref "C107")
      (value "0.22uF")
      (footprint "eagle-import:C0201")
      (fields (field (name "MPN") "GRM033R60J224ME15D"))
      (libsource (lib "eagle-import") (part "C-EUC0201"))
    )
    (comp (ref "C108")
      (value "4.7uF")
      (footprint "eagle-import:0402-CAP")
      (fields (field (name "MPN") "JMK105BBJ475MV-F"))
      (libsource (lib "eagle-import") (part "CAP0402-CAP"))
    )
    (comp (ref "C109")
      (value "0.22uF")
      (footprint "eagle-import:C0201")
      (fields (field (name "MPN") "GRM033R60J224ME15D"))
      (libsource (lib "eagle-import") (part "C-EUC0201"))
    )
    (comp (ref "C110")
      (value "1nF")
      (footprint "eagle-import:0402-CAP")
      (fields (field (name "MPN") "VJ0402Y102JXACW1BC"))
      (libsource (lib "eagle-import") (part "CAP0402-CAP"))
    )
    (comp (ref "CN1")
      (value "S2B-PH-K-S(LF)(SN)")
      (footprint "eagle-import:JST-PH-2-THM-RA")
      (libsource (lib "eagle-import") (part "JST_2PIN-THM-RA"))
    )
    (comp (ref "D1")
      (value "UHD1110-FKA-CL1A13R3Q1BBQFMF3")
      (footprint "eagle-import:LED_UHD1110-FKA-CL1A13R3Q1BBQFMF3")
      (fields (field (name "MF") "Cree Inc.") (field (name "MPN") "UHD1110-FKA-CL1A13r3q1BBQFMF3"))
      (libsource (lib "eagle-import") (part "UHD1110-FKA-CL1A13R3Q1BBQFMF3"))
    )
    (comp (ref "D2")
      (value "CPDQT5V0HE-HF")
      (footprint "eagle-import:CPDQT5V0HEHF")
      (libsource (lib "eagle-import") (part "CPDQT5V0HE-HF"))
    )
    (comp (ref "D3")
      (value "UHD1110-FKA-CL1A13R3Q1BBQFMF3")
      (footprint "eagle-import:LED_UHD1110-FKA-CL1A13R3Q1BBQFMF3")
      (fields (field (name "MF") "Cree Inc.") (field (name "MPN") "UHD1110-FKA-CL1A13r3q1BBQFMF3"))
      (libsource (lib "eagle-import") (part "UHD1110-FKA-CL1A13R3Q1BBQFMF3"))
    )
    (comp (ref "D4")
      (value "CPDQT5V0HE-HF")
      (footprint "eagle-import:CPDQT5V0HEHF")
      (libsource (lib "eagle-import") (part "CPDQT5V0HE-HF"))
    )
    (comp (ref "D5")
      (value "CPDQT5V0HE-HF")
      (footprint "eagle-import:CPDQT5V0HEHF")
      (libsource (lib "eagle-import") (part "CPDQT5V0HE-HF"))
    )
    (comp (ref "D6")
      (value "CPDQT5V0HE-HF")
      (footprint "eagle-import:CPDQT5V0HEHF")
      (libsource (lib "eagle-import") (part "CPDQT5V0HE-HF"))
    )
    (comp (ref "D7")
      (value "CPDQT5V0HE-HF")
      (footprint "eagle-import:CPDQT5V0HEHF")
      (libsource (lib "eagle-import") (part "CPDQT5V0HE-HF"))
    )
    (comp (ref "D8")
      (value "CPDQT5V0HE-HF")
      (footprint "eagle-import:CPDQT5V0HEHF")
      (libsource (lib "eagle-import") (part "CPDQT5V0HE-HF"))
    )
    (comp (ref "D9")
      (value "CPDQT5V0HE-HF")
      (footprint "eagle-import:CPDQT5V0HEHF")
      (libsource (lib "eagle-import") (part "CPDQT5V0HE-HF"))
    )
    (comp (ref "D10")
      (value "CPDQT5V0HE-HF")
      (footprint "eagle-import:CPDQT5V0HEHF")
      (libsource (lib "eagle-import") (part "CPDQT5V0HE-HF"))
    )
    (comp (ref "FD1")
      (value "FIDUCIAL1X2")
      (footprint "eagle-import:FIDUCIAL-1X2")
      (libsource (lib "eagle-import") (part "FIDUCIAL1X2"))
    )
    (comp (ref "FD2")
      (value "FIDUCIAL1X2")
      (footprint "eagle-import:FIDUCIAL-1X2")
      (libsource (lib "eagle-import") (part "FIDUCIAL1X2"))
    )
    (comp (ref "FD3")
      (value "FIDUCIAL1X2")
      (footprint "eagle-import:FIDUCIAL-1X2")
      (libsource (lib "eagle-import") (part "FIDUCIAL1X2"))
    )
    (comp (ref "FD4")
      (value "FIDUCIAL1X2")
      (footprint "eagle-import:FIDUCIAL-1X2")
      (libsource (lib "eagle-import") (part "FIDUCIAL1X2"))
    )
    (comp (ref "FD5")
      (value "FIDUCIAL1X2")
      (footprint "eagle-import:FIDUCIAL-1X2")
      (libsource (lib "eagle-import") (part "FIDUCIAL1X2"))
    )
    (comp (ref "FD6")
      (value "FIDUCIAL1X2")
      (footprint "eagle-import:FIDUCIAL-1X2")
      (libsource (lib "eagle-import") (part "FIDUCIAL1X2"))
    )
    (comp (ref "FD7")
      (value "FIDUCIAL1X2")
      (footprint "eagle-import:FIDUCIAL-1X2")
      (libsource (lib "eagle-import") (part "FIDUCIAL1X2"))
    )
    (comp (ref "FD8")
      (value "FIDUCIAL1X2")
      (footprint "eagle-import:FIDUCIAL-1X2")
      (libsource (lib "eagle-import") (part "FIDUCIAL1X2"))
    )
    (comp (ref "FL1")
      (value "ECMF02-4CMX8")
      (footprint "eagle-import:ECMF024CMX8")
      (fields (field (name "MOUSER_PART_NUMBER") "511-ECMF02-4CMX8"))
      (libsource (lib "eagle-import") (part "ECMF02-4CMX8"))
    )
    (comp (ref "FL2")
      (value "EMIF06-1005M12")
      (footprint "eagle-import:SON40P150X250X65-13N")
      (fields (field (name "MOUSER_PART_NUMBER") "511-EMIF06-1005M12"))
      (libsource (lib "eagle-import") (part "EMIF06-1005M12"))
    )
    (comp (ref "FL3")
      (value "EMIF06-1005M12")
      (footprint "eagle-import:SON40P150X250X65-13N")
      (fields (field (name "MOUSER_PART_NUMBER") "511-EMIF06-1005M12"))
      (libsource (lib "eagle-import") (part "EMIF06-1005M12"))
    )
    (comp (ref "FL4")
      (value "EMIF06-1005M12")
      (footprint "eagle-import:SON40P150X250X65-13N")
      (fields (field (name "MOUSER_PART_NUMBER") "511-EMIF06-1005M12"))
      (libsource (lib "eagle-import") (part "EMIF06-1005M12"))
    )
    (comp (ref "FL5")
      (value "EMIF06-1005M12")
      (footprint "eagle-import:SON40P150X250X65-13N")
      (fields (field (name "MOUSER_PART_NUMBER") "511-EMIF06-1005M12"))
      (libsource (lib "eagle-import") (part "EMIF06-1005M12"))
    )
    (comp (ref "H1")
      (value "MOUNT-PAD-ROUND2.8")
      (footprint "eagle-import:2,8-PAD")
      (libsource (lib "eagle-import") (part "MOUNT-PAD-ROUND2.8"))
    )
    (comp (ref "H2")
      (value "MOUNT-PAD-ROUND2.8")
      (footprint "eagle-import:2,8-PAD")
      (libsource (lib "eagle-import") (part "MOUNT-PAD-ROUND2.8"))
    )
    (comp (ref "IC1")
      (value "LM66200DRLR")
      (footprint "eagle-import:SOTFL50P160X60-8N")
      (fields (field (name "MOUSER_PART_NUMBER") "595-LM66200DRLR"))
      (libsource (lib "eagle-import") (part "LM66200DRLR"))
    )
    (comp (ref "IC2")
      (value "AP61300Z6-7")
      (footprint "eagle-import:SOTFL50P162X60-6N")
      (fields (field (name "MOUSER_PART_NUMBER") "621-AP61300Z6-7"))
      (libsource (lib "eagle-import") (part "AP61300Z6-7"))
    )
    (comp (ref "IC3")
      (value "IS42S16160G-6BL")
      (footprint "eagle-import:BGA54C80P9X9_800X800X120")
      (fields (field (name "MOUSER_PART_NUMBER") "870-IS42S16160G-6BL"))
      (libsource (lib "eagle-import") (part "IS42S16160G-6BL"))
    )
    (comp (ref "IC4")
      (value "ATECC608B-MAHDA-T")
      (footprint "eagle-import:SON50P300X200X60-9N")
      (fields (field (name "MOUSER_PART_NUMBER") "579-TECC608B-MAHDA-T"))
      (libsource (lib "eagle-import") (part "ATECC608B-MAHDA-T"))
    )
    (comp (ref "IC5")
      (value "IS25LP064D-JKLE-TR")
      (footprint "eagle-import:SON127P500X595X80-9N")
      (fields (field (name "MOUSER_PART_NUMBER") "870-5LP064D-JKLE-TR"))
      (libsource (lib "eagle-import") (part "IS25LP064D-JKLE-TR"))
    )
    (comp (ref "IC6")
      (value "IS25LP128F-JKLE-TR")
      (footprint "eagle-import:SON127P500X595X80-9N")
      (fields (field (name "MOUSER_PART_NUMBER") "870-IS25LP128FJKLETR"))
      (libsource (lib "eagle-import") (part "IS25LP128F-JKLE-TR"))
    )
    (comp (ref "IC7")
      (value "MXC4005XC")
      (footprint "eagle-import:MXC4005XC")
      (fields (field (name "MOUSER_PART_NUMBER") "438-MXC4005XC"))
      (libsource (lib "eagle-import") (part "MXC4005XC"))
    )
    (comp (ref "IC8")
      (value "MIMXRT1052DVL6B")
      (footprint "eagle-import:BGA196C65P14X14_1000X1000X143")
      (fields (field (name "MOUSER_PART_NUMBER") "771-MIMXRT1052DVL6B"))
      (libsource (lib "eagle-import") (part "MIMXRT1052DVL6B"))
    )
    (comp (ref "IC9")
      (value "KSZ8081RNDCA-TR")
      (footprint "eagle-import:QFN50P400X400X90-25N")
      (fields (field (name "MOUSER_PART_NUMBER") "998-KSZ8081RNDCATR"))
      (libsource (lib "eagle-import") (part "KSZ8081RNDCA-TR"))
    )
    (comp (ref "J1")
      (value "USB4105-GF-A")
      (footprint "eagle-import:GCT_USB4105-GF-A")
      (fields (field (name "MF") "GCT"))
      (libsource (lib "eagle-import") (part "USB4105-GF-A"))
    )
    (comp (ref "J2")
      (value "DNP")
      (footprint "eagle-import:1X08")
      (libsource (lib "eagle-import") (part "CONN_08{dblquote}"))
    )
    (comp (ref "J3")
      (value "DNP")
      (footprint "eagle-import:1X08")
      (libsource (lib "eagle-import") (part "CONN_08{dblquote}"))
    )
    (comp (ref "J4")
      (value "DF12-36-DS")
      (footprint "eagle-import:DF12-36-DS")
      (fields (field (name "MPN") "DF12NB-36DS-0.5V(51)"))
      (libsource (lib "eagle-import") (part "DF12-36-DS"))
    )
    (comp (ref "J5")
      (value "USD-1040310811")
      (footprint "eagle-import:1040310811")
      (fields (field (name "MPN") "104031-0811"))
      (libsource (lib "eagle-import") (part "USD-1040310811"))
    )
    (comp (ref "J6")
      (value "DNP")
      (footprint "eagle-import:1X08")
      (libsource (lib "eagle-import") (part "CONN_08{dblquote}"))
    )
    (comp (ref "J7")
      (value "DNP")
      (footprint "eagle-import:23370191")
      (fields
        (field (name "MANUFACTURER_PART_NUMBER") "2337019-1")
        (field (name "MOUSER_PART_NUMBER") "571-2337019-1")
      )
      (libsource (lib "eagle-import") (part "2337019-1"))
    )
    (comp (ref "J8")
      (value "3221-10-0300-00")
      (footprint "eagle-import:CNC_3221-10-0300-00")
      (fields (field (name "MF") "CNC Tech"))
      (libsource (lib "eagle-import") (part "3221-10-0300-00"))
    )
    (comp (ref "L1")
      (value "100")
      (footprint "eagle-import:0603")
      (fields (field (name "MPN") "MFBM1V1608-101-R"))
      (libsource (lib "eagle-import") (part "INDUCTOR-0603-33NH"))
    )
    (comp (ref "L2")
      (value "MAKK2016T1R0M")
      (footprint "eagle-import:INDC2016X100N")
      (fields (field (name "MF") "Taiyo Yuden"))
      (libsource (lib "eagle-import") (part "MAKK2016T1R0M"))
    )
    (comp (ref "L4")
      (value "100")
      (footprint "eagle-import:C0402")
      (fields (field (name "MPN") "MFBM1V1005-101-R"))
      (libsource (lib "eagle-import") (part "INDUCTOR0402"))
    )
    (comp (ref "L5")
      (value "MAKK2016T4R7M")
      (footprint "eagle-import:INDC2016X100N")
      (fields (field (name "MF") "Taiyo Yuden"))
      (libsource (lib "eagle-import") (part "MAKK2016T4R7M"))
    )
    (comp (ref "L6")
      (value "100")
      (footprint "eagle-import:C0402")
      (fields (field (name "MPN") "MFBM1V1005-101-R"))
      (libsource (lib "eagle-import") (part "INDUCTOR0402"))
    )
    (comp (ref "L7")
      (value "3.9NH")
      (footprint "eagle-import:0402")
      (fields (field (name "MPN") "L-07C3N9SV6T"))
      (libsource (lib "eagle-import") (part "INDUCTOR-0402-3.9NH"))
    )
    (comp (ref "L8")
      (value "100")
      (footprint "eagle-import:C0402")
      (fields (field (name "MPN") "MFBM1V1005-101-R"))
      (libsource (lib "eagle-import") (part "INDUCTOR0402"))
    )
    (comp (ref "L9")
      (value "MAKK2016T2R2M")
      (footprint "eagle-import:INDC2016X100N")
      (fields (field (name "MF") "Taiyo Yuden"))
      (libsource (lib "eagle-import") (part "MAKK2016T2R2M"))
    )
    (comp (ref "M1")
      (value "9774030151R")
      (footprint "eagle-import:9774030151R")
      (libsource (lib "eagle-import") (part "9774030151R"))
    )
    (comp (ref "M2")
      (value "9774030151R")
      (footprint "eagle-import:9774030151R")
      (libsource (lib "eagle-import") (part "9774030151R"))
    )
    (comp (ref "Q1")
      (value "2N7002KW_R1_00001")
      (footprint "eagle-import:SOT65P210X110-3N")
      (fields (field (name "MOUSER_PART_NUMBER") "241-2N7002KWR100001"))
      (libsource (lib "eagle-import") (part "2N7002KW_R1_00001"))
    )
    (comp (ref "Q2")
      (value "2N7002KW_R1_00001")
      (footprint "eagle-import:SOT65P210X110-3N")
      (fields (field (name "MOUSER_PART_NUMBER") "241-2N7002KWR100001"))
      (libsource (lib "eagle-import") (part "2N7002KW_R1_00001"))
    )
    (comp (ref "Q3")
      (value "2N7002KW_R1_00001")
      (footprint "eagle-import:SOT65P210X110-3N")
      (fields (field (name "MOUSER_PART_NUMBER") "241-2N7002KWR100001"))
      (libsource (lib "eagle-import") (part "2N7002KW_R1_00001"))
    )
    (comp (ref "Q4")
      (value "2N7002KW_R1_00001")
      (footprint "eagle-import:SOT65P210X110-3N")
      (fields (field (name "MOUSER_PART_NUMBER") "241-2N7002KWR100001"))
      (libsource (lib "eagle-import") (part "2N7002KW_R1_00001"))
    )
    (comp (ref "Q5")
      (value "2N7002KW_R1_00001")
      (footprint "eagle-import:SOT65P210X110-3N")
      (fields (field (name "MOUSER_PART_NUMBER") "241-2N7002KWR100001"))
      (libsource (lib "eagle-import") (part "2N7002KW_R1_00001"))
    )
    (comp (ref "Q6")
      (value "PMXB120EPEZ")
      (footprint "eagle-import:PMXB120EPEZ")
      (fields (field (name "MOUSER_PART_NUMBER") "771-PMXB120EPEZ"))
      (libsource (lib "eagle-import") (part "PMXB120EPEZ"))
    )
    (comp (ref "R1")
      (value "1K")
      (footprint "eagle-import:0402-RES")
      (fields (field (name "MPN") "CRCW04021K00FKEDC"))
      (libsource (lib "eagle-import") (part "RESISTOR0402-RES"))
    )
    (comp (ref "R2")
      (value "200K")
      (footprint "eagle-import:0402-RES")
      (fields (field (name "MPN") "CRCW0402200KFKEDC"))
      (libsource (lib "eagle-import") (part "RESISTOR0402-RES"))
    )
    (comp (ref "R3")
      (value "100K")
      (footprint "eagle-import:0402-RES")
      (fields (field (name "MPN") "AC0402FR-07100KL"))
      (libsource (lib "eagle-import") (part "RESISTOR0402-RES"))
    )
    (comp (ref "R4")
      (value "1K")
      (footprint "eagle-import:0402-RES")
      (fields (field (name "MPN") "CRCW04021K00FKEDC"))
      (libsource (lib "eagle-import") (part "RESISTOR0402-RES"))
    )
    (comp (ref "R5")
      (value "1K")
      (footprint "eagle-import:0402-RES")
      (fields (field (name "MPN") "CRCW04021K00FKEDC"))
      (libsource (lib "eagle-import") (part "RESISTOR0402-RES"))
    )
    (comp (ref "R6")
      (value "5.1K")
      (footprint "eagle-import:0402-RES")
      (fields (field (name "MPN") "RC0402JR-075K1L"))
      (libsource (lib "eagle-import") (part "RESISTOR0402-RES"))
    )
    (comp (ref "R7")
      (value "5.1K")
      (footprint "eagle-import:0402-RES")
      (fields (field (name "MPN") "RC0402JR-075K1L"))
      (libsource (lib "eagle-import") (part "RESISTOR0402-RES"))
    )
    (comp (ref "R8")
      (value "44.2K")
      (footprint "eagle-import:0402-RES")
      (fields (field (name "MPN") "AC0402FR-0744K2L"))
      (libsource (lib "eagle-import") (part "RESISTOR0402-RES"))
    )
    (comp (ref "R9")
      (value "10K")
      (footprint "eagle-import:0402-RES")
      (fields (field (name "MPN") "AC0402FR-1310KL"))
      (libsource (lib "eagle-import") (part "RESISTOR0402-RES"))
    )
    (comp (ref "R10")
      (value "3.3K")
      (footprint "eagle-import:0402-RES")
      (fields (field (name "MPN") "CRCW04023K30FKEDC"))
      (libsource (lib "eagle-import") (part "RESISTOR0402-RES"))
    )
    (comp (ref "R11")
      (value "46.4K")
      (footprint "eagle-import:0402-RES")
      (fields (field (name "MPN") "WR04X4642FTL"))
      (libsource (lib "eagle-import") (part "RESISTOR0402-RES"))
    )
    (comp (ref "R12")
      (value "8.2K")
      (footprint "eagle-import:0402-RES")
      (fields (field (name "MPN") "RC0402JR-078K2L"))
      (libsource (lib "eagle-import") (part "RESISTOR0402-RES"))
    )
    (comp (ref "R13")
      (value "100K")
      (footprint "eagle-import:0402-RES")
      (fields (field (name "MPN") "AC0402FR-07100KL"))
      (libsource (lib "eagle-import") (part "RESISTOR0402-RES"))
    )
    (comp (ref "R14")
      (value "100K")
      (footprint "eagle-import:0402-RES")
      (fields (field (name "MPN") "AC0402FR-07100KL"))
      (libsource (lib "eagle-import") (part "RESISTOR0402-RES"))
    )
    (comp (ref "R15")
      (value "2.7K")
      (footprint "eagle-import:0402-RES")
      (fields (field (name "MPN") "AC0402JR-072K7L"))
      (libsource (lib "eagle-import") (part "RESISTOR0402-RES"))
    )
    (comp (ref "R16")
      (value "2.7K")
      (footprint "eagle-import:0402-RES")
      (fields (field (name "MPN") "AC0402JR-072K7L"))
      (libsource (lib "eagle-import") (part "RESISTOR0402-RES"))
    )
    (comp (ref "R17")
      (value "2.7K")
      (footprint "eagle-import:0402-RES")
      (fields (field (name "MPN") "AC0402JR-072K7L"))
      (libsource (lib "eagle-import") (part "RESISTOR0402-RES"))
    )
    (comp (ref "R18")
      (value "100K")
      (footprint "eagle-import:0402-RES")
      (fields (field (name "MPN") "AC0402FR-07100KL"))
      (libsource (lib "eagle-import") (part "RESISTOR0402-RES"))
    )
    (comp (ref "R19")
      (value "220")
      (footprint "eagle-import:0402-RES")
      (fields (field (name "MPN") "CRGCQ0402F220R"))
      (libsource (lib "eagle-import") (part "RESISTOR0402-RES"))
    )
    (comp (ref "R20")
      (value "220")
      (footprint "eagle-import:0402-RES")
      (fields (field (name "MPN") "CRGCQ0402F220R"))
      (libsource (lib "eagle-import") (part "RESISTOR0402-RES"))
    )
    (comp (ref "R21")
      (value "220")
      (footprint "eagle-import:0402-RES")
      (fields (field (name "MPN") "CRGCQ0402F220R"))
      (libsource (lib "eagle-import") (part "RESISTOR0402-RES"))
    )
    (comp (ref "R22")
      (value "100K")
      (footprint "eagle-import:0402-RES")
      (fields (field (name "MPN") "AC0402FR-07100KL"))
      (libsource (lib "eagle-import") (part "RESISTOR0402-RES"))
    )
    (comp (ref "R23")
      (value "100K")
      (footprint "eagle-import:0402-RES")
      (fields (field (name "MPN") "AC0402FR-07100KL"))
      (libsource (lib "eagle-import") (part "RESISTOR0402-RES"))
    )
    (comp (ref "R24")
      (value "100K")
      (footprint "eagle-import:0402-RES")
      (fields (field (name "MPN") "AC0402FR-07100KL"))
      (libsource (lib "eagle-import") (part "RESISTOR0402-RES"))
    )
    (comp (ref "R25")
      (value "100K")
      (footprint "eagle-import:0402-RES")
      (fields (field (name "MPN") "AC0402FR-07100KL"))
      (libsource (lib "eagle-import") (part "RESISTOR0402-RES"))
    )
    (comp (ref "R26")
      (value "1K")
      (footprint "eagle-import:0402-RES")
      (fields (field (name "MPN") "CRCW04021K00FKEDC"))
      (libsource (lib "eagle-import") (part "RESISTOR0402-RES"))
    )
    (comp (ref "R27")
      (value "100K")
      (footprint "eagle-import:0402-RES")
      (fields (field (name "MPN") "AC0402FR-07100KL"))
      (libsource (lib "eagle-import") (part "RESISTOR0402-RES"))
    )
    (comp (ref "R28")
      (value "100K")
      (footprint "eagle-import:0402-RES")
      (fields (field (name "MPN") "AC0402FR-07100KL"))
      (libsource (lib "eagle-import") (part "RESISTOR0402-RES"))
    )
    (comp (ref "R29")
      (value "100K")
      (footprint "eagle-import:0402-RES")
      (fields (field (name "MPN") "AC0402FR-07100KL"))
      (libsource (lib "eagle-import") (part "RESISTOR0402-RES"))
    )
    (comp (ref "R30")
      (value "4.7K")
      (footprint "eagle-import:0402-RES")
      (fields (field (name "MPN") "AC0402FR-074K7L"))
      (libsource (lib "eagle-import") (part "RESISTOR0402-RES"))
    )
    (comp (ref "R31")
      (value "4.7K")
      (footprint "eagle-import:0402-RES")
      (fields (field (name "MPN") "AC0402FR-074K7L"))
      (libsource (lib "eagle-import") (part "RESISTOR0402-RES"))
    )
    (comp (ref "R32")
      (value "30K")
      (footprint "eagle-import:0402-RES")
      (fields (field (name "MPN") "0402WGF3002TCE"))
      (libsource (lib "eagle-import") (part "RESISTOR0402-RES"))
    )
    (comp (ref "R33")
      (value "10K")
      (footprint "eagle-import:0402-RES")
      (fields (field (name "MPN") "AC0402FR-1310KL"))
      (libsource (lib "eagle-import") (part "RESISTOR0402-RES"))
    )
    (comp (ref "R34")
      (value "100K")
      (footprint "eagle-import:0402-RES")
      (fields (field (name "MPN") "AC0402FR-07100KL"))
      (libsource (lib "eagle-import") (part "RESISTOR0402-RES"))
    )
    (comp (ref "R35")
      (value "220")
      (footprint "eagle-import:0402-RES")
      (fields (field (name "MPN") "CRGCQ0402F220R"))
      (libsource (lib "eagle-import") (part "RESISTOR0402-RES"))
    )
    (comp (ref "R36")
      (value "1K")
      (footprint "eagle-import:0402-RES")
      (fields (field (name "MPN") "CRCW04021K00FKEDC"))
      (libsource (lib "eagle-import") (part "RESISTOR0402-RES"))
    )
    (comp (ref "R37")
      (value "10K")
      (footprint "eagle-import:0402-RES")
      (fields (field (name "MPN") "AC0402FR-1310KL"))
      (libsource (lib "eagle-import") (part "RESISTOR0402-RES"))
    )
    (comp (ref "R38")
      (value "6.49K")
      (footprint "eagle-import:0402-RES")
      (fields (field (name "MPN") "CR0402-FX-6491GLF"))
      (libsource (lib "eagle-import") (part "RESISTOR0402-RES"))
    )
    (comp (ref "R39")
      (value "1K")
      (footprint "eagle-import:0402-RES")
      (fields (field (name "MPN") "CRCW04021K00FKEDC"))
      (libsource (lib "eagle-import") (part "RESISTOR0402-RES"))
    )
    (comp (ref "R40")
      (value "2.2M")
      (footprint "eagle-import:0402-RES")
      (fields (field (name "MPN") "RC0402FR-072M2L"))
      (libsource (lib "eagle-import") (part "RESISTOR0402-RES"))
    )
    (comp (ref "R41")
      (value "1M")
      (footprint "eagle-import:0402-RES")
      (fields (field (name "MPN") "CRCW04021M00FKEDC"))
      (libsource (lib "eagle-import") (part "RESISTOR0402-RES"))
    )
    (comp (ref "RN1")
      (value "EXB-2HV104JV")
      (footprint "eagle-import:EXB2HV104JV")
      (fields (field (name "MOUSER_PART_NUMBER") "667-EXB-2HV104JV"))
      (libsource (lib "eagle-import") (part "EXB-2HV104JV"))
    )
    (comp (ref "RN2")
      (value "EXB-2HV104JV")
      (footprint "eagle-import:EXB2HV104JV")
      (fields (field (name "MOUSER_PART_NUMBER") "667-EXB-2HV104JV"))
      (libsource (lib "eagle-import") (part "EXB-2HV104JV"))
    )
    (comp (ref "U1")
      (value "MIC5365-3.3YMT-TZ")
      (footprint "eagle-import:VREG_MIC5365-3.3YMT-TZ")
      (libsource (lib "eagle-import") (part "MIC5365-3.3YMT-TZ"))
    )
    (comp (ref "U2")
      (value "BQ24075RGTR")
      (footprint "eagle-import:QFN50P300X300X100-17N")
      (fields (field (name "MF") "Texas Instruments"))
      (libsource (lib "eagle-import") (part "BQ24075RGTR"))
    )
    (comp (ref "U3")
      (value "LBEE5KL1DX-883")
      (footprint "eagle-import:XCVR_LBEE5KL1DX-TEMP")
      (fields (field (name "MF") "Murata Electronics") (field (name "MP") "LBEE5KL1DX-TEMP"))
      (libsource (lib "eagle-import") (part "LBEE5KL1DX-TEMP"))
    )
    (comp (ref "Y1")
      (value "SC32S-7PF20PPM")
      (footprint "eagle-import:XTAL_ABS07-32.768KHZ-7-T")
      (fields (field (name "MF") "Abracon") (field (name "MP") "ABS07-32.768KHZ-7-T"))
      (libsource (lib "eagle-import") (part "ABS07-32.768KHZ-7-T"))
    )
    (comp (ref "Y2")
      (value "XRCGB24M000F3M00R0")
      (footprint "eagle-import:XRCGB24M000F3M00R0")
      (fields (field (name "MOUSER_PART_NUMBER") "81-XRCGB24M000F3M0R0"))
      (libsource (lib "eagle-import") (part "XRCGB24M000F3M00R0"))
    )
  )
  (nets
    (net (code "1") (name "/BT_D_WAKE") (class "Default")
      (node (ref "IC8") (pin "L7") (pinfunction "PMIC_STBY_REQ_L7") (pintype "bidirectional"))
      (node (ref "U3") (pin "39") (pinfunction "BT_DEV_WAKE_39") (pintype "bidirectional"))
    )
    (net (code "2") (name "/BT_H_WAKE") (class "Default")
      (node (ref "IC8") (pin "H14") (pinfunction "GPIO_AD_B0_14_H14") (pintype "bidirectional"))
      (node (ref "U3") (pin "38") (pinfunction "BT_HOST_WAKE_38") (pintype "bidirectional"))
    )
    (net (code "3") (name "/BT_REG_ON") (class "Default")
      (node (ref "IC8") (pin "F13") (pinfunction "GPIO_AD_B0_08_F13") (pintype "bidirectional"))
      (node (ref "R37") (pin "1") (pinfunction "1_1") (pintype "passive"))
      (node (ref "U3") (pin "14") (pinfunction "BT_REG_ON_14") (pintype "input"))
    )
    (net (code "4") (name "/BT_UART_RX") (class "Default")
      (node (ref "IC8") (pin "C9") (pinfunction "GPIO_B0_09_C9") (pintype "bidirectional"))
      (node (ref "U3") (pin "3") (pinfunction "BT_UART_TXD_3") (pintype "output"))
    )
    (net (code "5") (name "/BT_UART_TX") (class "Default")
      (node (ref "IC8") (pin "B9") (pinfunction "GPIO_B0_08_B9") (pintype "bidirectional"))
      (node (ref "U3") (pin "2") (pinfunction "BT_UART_RXD_2") (pintype "input"))
    )
    (net (code "6") (name "/DCDC_LP") (class "Default")
      (node (ref "IC8") (pin "M1") (pinfunction "DCDC_LP_1_M1") (pintype "bidirectional"))
      (node (ref "IC8") (pin "M2") (pinfunction "DCDC_LP_2_M2") (pintype "bidirectional"))
      (node (ref "L5") (pin "2") (pinfunction "2_2") (pintype "passive"))
    )
    (net (code "7") (name "/DCDC_PSWITCH") (class "Default")
      (node (ref "C62") (pin "1") (pinfunction "1_1") (pintype "passive"))
      (node (ref "IC8") (pin "K3") (pinfunction "DCDC_PSWITCH_K3") (pintype "bidirectional"))
      (node (ref "R32") (pin "1") (pinfunction "1_1") (pintype "passive"))
    )
    (net (code "8") (name "/DCMI_CLK") (class "Default")
      (node (ref "IC8") (pin "B14") (pinfunction "GPIO_B1_15_B14") (pintype "bidirectional"))
      (node (ref "J4") (pin "12") (pinfunction "12_12") (pintype "bidirectional"))
    )
    (net (code "9") (name "/DCMI_D0") (class "Default")
      (node (ref "IC8") (pin "J14") (pinfunction "GPIO_AD_B1_15_J14") (pintype "bidirectional"))
      (node (ref "J4") (pin "31") (pinfunction "31_31") (pintype "bidirectional"))
    )
    (net (code "10") (name "/DCMI_D1") (class "Default")
      (node (ref "IC8") (pin "G12") (pinfunction "GPIO_AD_B1_14_G12") (pintype "bidirectional"))
      (node (ref "J4") (pin "29") (pinfunction "29_29") (pintype "bidirectional"))
    )
    (net (code "11") (name "/DCMI_D2") (class "Default")
      (node (ref "IC8") (pin "H11") (pinfunction "GPIO_AD_B1_13_H11") (pintype "bidirectional"))
      (node (ref "J4") (pin "35") (pinfunction "35_35") (pintype "bidirectional"))
    )
    (net (code "12") (name "/DCMI_D3") (class "Default")
      (node (ref "IC8") (pin "H12") (pinfunction "GPIO_AD_B1_12_H12") (pintype "bidirectional"))
      (node (ref "J4") (pin "28") (pinfunction "28_28") (pintype "bidirectional"))
    )
    (net (code "13") (name "/DCMI_D4") (class "Default")
      (node (ref "IC8") (pin "J13") (pinfunction "GPIO_AD_B1_11_J13") (pintype "bidirectional"))
      (node (ref "J4") (pin "26") (pinfunction "26_26") (pintype "bidirectional"))
    )
    (net (code "14") (name "/DCMI_D5") (class "Default")
      (node (ref "IC8") (pin "L13") (pinfunction "GPIO_AD_B1_10_L13") (pintype "bidirectional"))
      (node (ref "J4") (pin "33") (pinfunction "33_33") (pintype "bidirectional"))
    )
    (net (code "15") (name "/DCMI_D6") (class "Default")
      (node (ref "IC8") (pin "G14") (pinfunction "GPIO_AD_B0_05_G14") (pintype "bidirectional"))
      (node (ref "J4") (pin "24") (pinfunction "24_24") (pintype "bidirectional"))
    )
    (net (code "16") (name "/DCMI_D7") (class "Default")
      (node (ref "IC8") (pin "F11") (pinfunction "GPIO_AD_B0_04_F11") (pintype "bidirectional"))
      (node (ref "J4") (pin "22") (pinfunction "22_22") (pintype "bidirectional"))
    )
    (net (code "17") (name "/DCMI_FSIN") (class "Default")
      (node (ref "J4") (pin "23") (pinfunction "23_23") (pintype "bidirectional"))
      (node (ref "Q5") (pin "3") (pinfunction "D_3") (pintype "bidirectional"))
      (node (ref "R28") (pin "1") (pinfunction "1_1") (pintype "passive"))
    )
    (net (code "18") (name "/DCMI_HSYNC") (class "Default")
      (node (ref "IC8") (pin "L10") (pinfunction "GPIO_AD_B0_15_L10") (pintype "bidirectional"))
      (node (ref "J4") (pin "18") (pinfunction "18_18") (pintype "bidirectional"))
    )
    (net (code "19") (name "/DCMI_MISO") (class "Default")
      (node (ref "IC8") (pin "E7") (pinfunction "GPIO_B0_01_E7") (pintype "bidirectional"))
      (node (ref "J4") (pin "15") (pinfunction "15_15") (pintype "bidirectional"))
    )
    (net (code "20") (name "/DCMI_MOSI") (class "Default")
      (node (ref "IC8") (pin "E8") (pinfunction "GPIO_B0_02_E8") (pintype "bidirectional"))
      (node (ref "J4") (pin "17") (pinfunction "17_17") (pintype "bidirectional"))
    )
    (net (code "21") (name "/DCMI_PCLK") (class "Default")
      (node (ref "IC8") (pin "D13") (pinfunction "GPIO_B1_12_D13") (pintype "bidirectional"))
      (node (ref "J4") (pin "14") (pinfunction "14_14") (pintype "bidirectional"))
    )
    (net (code "22") (name "/DCMI_PWDN") (class "Default")
      (node (ref "IC8") (pin "C11") (pinfunction "GPIO_B1_02_C11") (pintype "bidirectional"))
      (node (ref "J4") (pin "25") (pinfunction "25_25") (pintype "bidirectional"))
      (node (ref "R29") (pin "1") (pinfunction "1_1") (pintype "passive"))
    )
    (net (code "23") (name "/DCMI_RST") (class "Default")
      (node (ref "IC8") (pin "B11") (pinfunction "GPIO_B1_01_B11") (pintype "bidirectional"))
      (node (ref "J4") (pin "21") (pinfunction "21_21") (pintype "bidirectional"))
      (node (ref "R27") (pin "1") (pinfunction "1_1") (pintype "passive"))
    )
    (net (code "24") (name "/DCMI_SCL") (class "Default")
      (node (ref "IC8") (pin "J11") (pinfunction "GPIO_AD_B1_00_J11") (pintype "bidirectional"))
      (node (ref "J4") (pin "32") (pinfunction "32_32") (pintype "bidirectional"))
      (node (ref "R30") (pin "1") (pinfunction "1_1") (pintype "passive"))
    )
    (net (code "25") (name "/DCMI_SCLK") (class "Default")
      (node (ref "IC8") (pin "D8") (pinfunction "GPIO_B0_03_D8") (pintype "bidirectional"))
      (node (ref "J4") (pin "13") (pinfunction "13_13") (pintype "bidirectional"))
    )
    (net (code "26") (name "/DCMI_SDA") (class "Default")
      (node (ref "IC8") (pin "K11") (pinfunction "GPIO_AD_B1_01_K11") (pintype "bidirectional"))
      (node (ref "J4") (pin "34") (pinfunction "34_34") (pintype "bidirectional"))
      (node (ref "R31") (pin "1") (pinfunction "1_1") (pintype "passive"))
    )
    (net (code "27") (name "/DCMI_SSEL") (class "Default")
      (node (ref "IC8") (pin "D7") (pinfunction "GPIO_B0_00_D7") (pintype "bidirectional"))
      (node (ref "J4") (pin "11") (pinfunction "11_11") (pintype "bidirectional"))
      (node (ref "R24") (pin "1") (pinfunction "1_1") (pintype "passive"))
    )
    (net (code "28") (name "/DCMI_VSYNC") (class "Default")
      (node (ref "IC8") (pin "D14") (pinfunction "GPIO_B1_13_D14") (pintype "bidirectional"))
      (node (ref "J4") (pin "16") (pinfunction "16_16") (pintype "bidirectional"))
    )
    (net (code "29") (name "/ETH_INT") (class "Default")
      (node (ref "IC8") (pin "C10") (pinfunction "GPIO_B0_12_C10") (pintype "bidirectional"))
      (node (ref "IC9") (pin "18") (pinfunction "INTRP_18") (pintype "bidirectional"))
      (node (ref "R36") (pin "1") (pinfunction "1_1") (pintype "passive"))
    )
    (net (code "30") (name "/ETH_MDC") (class "Default")
      (node (ref "IC8") (pin "A7") (pinfunction "GPIO_EMC_40_A7") (pintype "bidirectional"))
      (node (ref "IC9") (pin "11") (pinfunction "MDC_11") (pintype "bidirectional"))
    )
    (net (code "31") (name "/ETH_MDIO") (class "Default")
      (node (ref "IC8") (pin "C7") (pinfunction "GPIO_EMC_41_C7") (pintype "bidirectional"))
      (node (ref "IC9") (pin "10") (pinfunction "MDIO_10") (pintype "bidirectional"))
      (node (ref "R39") (pin "1") (pinfunction "1_1") (pintype "passive"))
    )
    (net (code "32") (name "/ETH_RST") (class "Default")
      (node (ref "C65") (pin "2") (pinfunction "2_2") (pintype "passive"))
      (node (ref "IC8") (pin "D10") (pinfunction "GPIO_B0_13_D10") (pintype "bidirectional"))
      (node (ref "IC9") (pin "24") (pinfunction "RST#_24") (pintype "bidirectional"))
      (node (ref "R34") (pin "1") (pinfunction "1_1") (pintype "passive"))
    )
    (net (code "33") (name "/ETH_RXD0") (class "Default")
      (node (ref "IC8") (pin "E12") (pinfunction "GPIO_B1_04_E12") (pintype "bidirectional"))
      (node (ref "IC9") (pin "13") (pinfunction "RXD0_13") (pintype "bidirectional"))
    )
    (net (code "34") (name "/ETH_RXD1") (class "Default")
      (node (ref "IC8") (pin "D12") (pinfunction "GPIO_B1_05_D12") (pintype "bidirectional"))
      (node (ref "IC9") (pin "12") (pinfunction "RXD1_12") (pintype "bidirectional"))
    )
    (net (code "35") (name "/ETH_RXDV") (class "Default")
      (node (ref "IC8") (pin "C12") (pinfunction "GPIO_B1_06_C12") (pintype "bidirectional"))
      (node (ref "IC9") (pin "15") (pinfunction "CRS_DV/_PHYAD[1:0]_15") (pintype "bidirectional"))
    )
    (net (code "36") (name "/ETH_RXERR") (class "Default")
      (node (ref "IC8") (pin "C13") (pinfunction "GPIO_B1_11_C13") (pintype "bidirectional"))
      (node (ref "IC9") (pin "17") (pinfunction "RXER_17") (pintype "bidirectional"))
    )
    (net (code "37") (name "/ETH_TXCLK") (class "Default")
      (node (ref "IC8") (pin "B13") (pinfunction "GPIO_B1_10_B13") (pintype "bidirectional"))
      (node (ref "IC9") (pin "8") (pinfunction "XI_8") (pintype "bidirectional"))
    )
    (net (code "38") (name "/ETH_TXD0") (class "Default")
      (node (ref "IC8") (pin "B12") (pinfunction "GPIO_B1_07_B12") (pintype "bidirectional"))
      (node (ref "IC9") (pin "20") (pinfunction "TXD0_20") (pintype "bidirectional"))
    )
    (net (code "39") (name "/ETH_TXD1") (class "Default")
      (node (ref "IC8") (pin "A12") (pinfunction "GPIO_B1_08_A12") (pintype "bidirectional"))
      (node (ref "IC9") (pin "21") (pinfunction "TXD1_21") (pintype "bidirectional"))
    )
    (net (code "40") (name "/ETH_TXEN") (class "Default")
      (node (ref "IC8") (pin "A13") (pinfunction "GPIO_B1_09_A13") (pintype "bidirectional"))
      (node (ref "IC9") (pin "19") (pinfunction "TXEN_19") (pintype "bidirectional"))
    )
    (net (code "41") (name "/INT_I2C_INT") (class "Default")
      (node (ref "IC7") (pin "4") (pinfunction "INT_4") (pintype "bidirectional"))
      (node (ref "IC8") (pin "D11") (pinfunction "GPIO_B1_03_D11") (pintype "bidirectional"))
      (node (ref "R17") (pin "1") (pinfunction "1_1") (pintype "passive"))
    )
    (net (code "42") (name "/INT_I2C_SCL") (class "Default")
      (node (ref "IC4") (pin "6") (pinfunction "SCL_6") (pintype "bidirectional"))
      (node (ref "IC7") (pin "1") (pinfunction "SCL_1") (pintype "bidirectional"))
      (node (ref "IC8") (pin "C8") (pinfunction "GPIO_B0_04_C8") (pintype "bidirectional"))
      (node (ref "R15") (pin "1") (pinfunction "1_1") (pintype "passive"))
    )
    (net (code "43") (name "/INT_I2C_SDA") (class "Default")
      (node (ref "IC4") (pin "5") (pinfunction "SDA_5") (pintype "bidirectional"))
      (node (ref "IC7") (pin "5") (pinfunction "SDA_5") (pintype "bidirectional"))
      (node (ref "IC8") (pin "B8") (pinfunction "GPIO_B0_05_B8") (pintype "bidirectional"))
      (node (ref "R16") (pin "1") (pinfunction "1_1") (pintype "passive"))
    )
    (net (code "44") (name "/JTAG_TCK") (class "Default")
      (node (ref "FL5") (pin "4") (pinfunction "INPUT_4_4") (pintype "bidirectional"))
      (node (ref "IC8") (pin "F12") (pinfunction "GPIO_AD_B0_07_F12") (pintype "bidirectional"))
    )
    (net (code "45") (name "/JTAG_TCK_INT") (class "Default")
      (node (ref "FL5") (pin "9") (pinfunction "OUTPUT_4_9") (pintype "bidirectional"))
      (node (ref "J8") (pin "4") (pinfunction "4_4") (pintype "passive"))
    )
    (net (code "46") (name "/JTAG_TDI") (class "Default")
      (node (ref "FL5") (pin "2") (pinfunction "INPUT_2_2") (pintype "bidirectional"))
      (node (ref "IC8") (pin "F14") (pinfunction "GPIO_AD_B0_09_F14") (pintype "bidirectional"))
    )
    (net (code "47") (name "/JTAG_TDI_INT") (class "Default")
      (node (ref "FL5") (pin "11") (pinfunction "OUTPUT_2_11") (pintype "bidirectional"))
      (node (ref "J8") (pin "8") (pinfunction "8_8") (pintype "passive"))
    )
    (net (code "48") (name "/JTAG_TDO") (class "Default")
      (node (ref "FL5") (pin "3") (pinfunction "INPUT_3_3") (pintype "bidirectional"))
      (node (ref "IC8") (pin "G13") (pinfunction "GPIO_AD_B0_10_G13") (pintype "bidirectional"))
    )
    (net (code "49") (name "/JTAG_TDO_INT") (class "Default")
      (node (ref "FL5") (pin "10") (pinfunction "OUTPUT_3_10") (pintype "bidirectional"))
      (node (ref "J8") (pin "6") (pinfunction "6_6") (pintype "passive"))
    )
    (net (code "50") (name "/JTAG_TMS") (class "Default")
      (node (ref "FL5") (pin "5") (pinfunction "INPUT_5_5") (pintype "bidirectional"))
      (node (ref "IC8") (pin "E14") (pinfunction "GPIO_AD_B0_06_E14") (pintype "bidirectional"))
    )
    (net (code "51") (name "/JTAG_TMS_INT") (class "Default")
      (node (ref "FL5") (pin "8") (pinfunction "OUTPUT_5_8") (pintype "bidirectional"))
      (node (ref "J8") (pin "2") (pinfunction "2_2") (pintype "passive"))
    )
    (net (code "52") (name "/JTAG_TRSTB") (class "Default")
      (node (ref "FL5") (pin "6") (pinfunction "INPUT_6_6") (pintype "bidirectional"))
      (node (ref "IC8") (pin "G10") (pinfunction "GPIO_AD_B0_11_G10") (pintype "bidirectional"))
    )
    (net (code "53") (name "/LED_B") (class "Default")
      (node (ref "IC8") (pin "C14") (pinfunction "GPIO_B1_14_C14") (pintype "bidirectional"))
      (node (ref "R19") (pin "1") (pinfunction "1_1") (pintype "passive"))
    )
    (net (code "54") (name "/LED_CHG") (class "Default")
      (node (ref "D1") (pin "3") (pinfunction "RED_3") (pintype "passive"))
      (node (ref "R1") (pin "2") (pinfunction "2_2") (pintype "passive"))
    )
    (net (code "55") (name "/LED_G") (class "Default")
      (node (ref "IC8") (pin "A10") (pinfunction "GPIO_B0_11_A10") (pintype "bidirectional"))
      (node (ref "R20") (pin "1") (pinfunction "1_1") (pintype "passive"))
    )
    (net (code "56") (name "/LED_PGOOD") (class "Default")
      (node (ref "D1") (pin "2") (pinfunction "GREEN_2") (pintype "passive"))
      (node (ref "R4") (pin "2") (pinfunction "2_2") (pintype "passive"))
    )
    (net (code "57") (name "/LED_R") (class "Default")
      (node (ref "IC8") (pin "D9") (pinfunction "GPIO_B0_10_D9") (pintype "bidirectional"))
      (node (ref "R21") (pin "1") (pinfunction "1_1") (pintype "passive"))
    )
    (net (code "58") (name "/MDI_LED") (class "Default")
      (node (ref "J3") (pin "8") (pinfunction "8_8") (pintype "passive"))
      (node (ref "R35") (pin "2") (pinfunction "2_2") (pintype "passive"))
    )
    (net (code "59") (name "/MDI_RX_N") (class "Default")
      (node (ref "IC9") (pin "3") (pinfunction "RXM_3") (pintype "bidirectional"))
      (node (ref "J3") (pin "7") (pinfunction "7_7") (pintype "passive"))
    )
    (net (code "60") (name "/MDI_RX_P") (class "Default")
      (node (ref "IC9") (pin "4") (pinfunction "RXP_4") (pintype "bidirectional"))
      (node (ref "J3") (pin "6") (pinfunction "6_6") (pintype "passive"))
    )
    (net (code "61") (name "/MDI_TX_N") (class "Default")
      (node (ref "IC9") (pin "5") (pinfunction "TXM_5") (pintype "bidirectional"))
      (node (ref "J3") (pin "5") (pinfunction "5_5") (pintype "passive"))
    )
    (net (code "62") (name "/MDI_TX_P") (class "Default")
      (node (ref "IC9") (pin "6") (pinfunction "TXP_6") (pintype "bidirectional"))
      (node (ref "J3") (pin "4") (pinfunction "4_4") (pintype "passive"))
    )
    (net (code "63") (name "/NVCC_PLL") (class "Default")
      (node (ref "C104") (pin "2") (pinfunction "2_2") (pintype "passive"))
      (node (ref "C107") (pin "1") (pinfunction "1_1") (pintype "passive"))
      (node (ref "IC8") (pin "P10") (pinfunction "NVCC_PLL_P10") (pintype "bidirectional"))
    )
    (net (code "64") (name "/ONOFF") (class "Default")
      (node (ref "IC8") (pin "M6") (pinfunction "ONOFF_M6") (pintype "bidirectional"))
      (node (ref "Q3") (pin "2") (pinfunction "S_2") (pintype "bidirectional"))
    )
    (net (code "65") (name "/P0_MOSI") (class "Default")
      (node (ref "FL2") (pin "1") (pinfunction "INPUT_1_1") (pintype "bidirectional"))
      (node (ref "IC8") (pin "H10") (pinfunction "GPIO_AD_B0_01_H10") (pintype "bidirectional"))
    )
    (net (code "66") (name "/P1_MISO") (class "Default")
      (node (ref "FL2") (pin "2") (pinfunction "INPUT_2_2") (pintype "bidirectional"))
      (node (ref "IC8") (pin "M11") (pinfunction "GPIO_AD_B0_02_M11") (pintype "bidirectional"))
    )
    (net (code "67") (name "/P2_SCLK") (class "Default")
      (node (ref "FL2") (pin "3") (pinfunction "INPUT_3_3") (pintype "bidirectional"))
      (node (ref "IC8") (pin "M14") (pinfunction "GPIO_AD_B0_00_M14") (pintype "bidirectional"))
    )
    (net (code "68") (name "/P3_NSS") (class "Default")
      (node (ref "FL2") (pin "4") (pinfunction "INPUT_4_4") (pintype "bidirectional"))
      (node (ref "IC8") (pin "G11") (pinfunction "GPIO_AD_B0_03_G11") (pintype "bidirectional"))
    )
    (net (code "69") (name "/P4_SCL") (class "Default")
      (node (ref "FL2") (pin "5") (pinfunction "INPUT_5_5") (pintype "bidirectional"))
      (node (ref "IC8") (pin "K14") (pinfunction "GPIO_AD_B0_12_K14") (pintype "bidirectional"))
    )
    (net (code "70") (name "/P5_SDA") (class "Default")
      (node (ref "FL2") (pin "6") (pinfunction "INPUT_6_6") (pintype "bidirectional"))
      (node (ref "IC8") (pin "L14") (pinfunction "GPIO_AD_B0_13_L14") (pintype "bidirectional"))
    )
    (net (code "71") (name "/P6_ADC") (class "Default")
      (node (ref "FL4") (pin "1") (pinfunction "INPUT_1_1") (pintype "bidirectional"))
      (node (ref "IC8") (pin "M12") (pinfunction "GPIO_AD_B1_03_M12") (pintype "bidirectional"))
    )
    (net (code "72") (name "/P7_PWM") (class "Default")
      (node (ref "FL4") (pin "2") (pinfunction "INPUT_2_2") (pintype "bidirectional"))
      (node (ref "IC8") (pin "A8") (pinfunction "GPIO_B0_06_A8") (pintype "bidirectional"))
    )
    (net (code "73") (name "/P7_PWM_INT") (class "Default")
      (node (ref "FL4") (pin "11") (pinfunction "OUTPUT_2_11") (pintype "bidirectional"))
      (node (ref "J6") (pin "3") (pinfunction "3_3") (pintype "passive"))
    )
    (net (code "74") (name "/P8_PWM") (class "Default")
      (node (ref "FL4") (pin "3") (pinfunction "INPUT_3_3") (pintype "bidirectional"))
      (node (ref "IC8") (pin "A9") (pinfunction "GPIO_B0_07_A9") (pintype "bidirectional"))
    )
    (net (code "75") (name "/P8_PWM_INT") (class "Default")
      (node (ref "FL4") (pin "10") (pinfunction "OUTPUT_3_10") (pintype "bidirectional"))
      (node (ref "J6") (pin "4") (pinfunction "4_4") (pintype "passive"))
    )
    (net (code "76") (name "/P9_PWM") (class "Default")
      (node (ref "FL4") (pin "4") (pinfunction "INPUT_4_4") (pintype "bidirectional"))
      (node (ref "IC8") (pin "A11") (pinfunction "GPIO_B1_00_A11") (pintype "bidirectional"))
    )
    (net (code "77") (name "/P9_PWM_INT") (class "Default")
      (node (ref "FL4") (pin "9") (pinfunction "OUTPUT_4_9") (pintype "bidirectional"))
      (node (ref "J6") (pin "5") (pinfunction "5_5") (pintype "passive"))
    )
    (net (code "78") (name "/P10_PWM") (class "Default")
      (node (ref "FL4") (pin "5") (pinfunction "INPUT_5_5") (pintype "bidirectional"))
      (node (ref "Q4") (pin "3") (pinfunction "D_3") (pintype "bidirectional"))
      (node (ref "R26") (pin "1") (pinfunction "1_1") (pintype "passive"))
    )
    (net (code "79") (name "/P10_PWM_INT") (class "Default")
      (node (ref "FL4") (pin "8") (pinfunction "OUTPUT_5_8") (pintype "bidirectional"))
      (node (ref "J6") (pin "6") (pinfunction "6_6") (pintype "passive"))
    )
    (net (code "80") (name "/P11_WAKEUP") (class "Default")
      (node (ref "FL4") (pin "6") (pinfunction "INPUT_6_6") (pintype "bidirectional"))
      (node (ref "Q2") (pin "3") (pinfunction "D_3") (pintype "bidirectional"))
      (node (ref "R22") (pin "1") (pinfunction "1_1") (pintype "passive"))
    )
    (net (code "81") (name "/P11_WAKEUP_INT") (class "Default")
      (node (ref "FL4") (pin "7") (pinfunction "OUTPUT_6_7") (pintype "bidirectional"))
      (node (ref "J6") (pin "7") (pinfunction "7_7") (pintype "passive"))
    )
    (net (code "82") (name "/P12_RST_N") (class "Default")
      (node (ref "C63") (pin "1") (pinfunction "1_1") (pintype "passive"))
      (node (ref "FL5") (pin "1") (pinfunction "INPUT_1_1") (pintype "bidirectional"))
      (node (ref "IC8") (pin "M7") (pinfunction "POR_B_M7") (pintype "bidirectional"))
      (node (ref "R33") (pin "2") (pinfunction "2_2") (pintype "passive"))
    )
    (net (code "83") (name "/P12_RST_N_EXT") (class "Default")
      (node (ref "FL5") (pin "12") (pinfunction "OUTPUT_1_12") (pintype "bidirectional"))
      (node (ref "J6") (pin "8") (pinfunction "8_8") (pintype "passive"))
      (node (ref "J8") (pin "10") (pinfunction "10_10") (pintype "passive"))
    )
    (net (code "84") (name "/PMIC_ONOFF") (class "Default")
      (node (ref "D8") (pin "1") (pinfunction "1_1") (pintype "bidirectional"))
      (node (ref "J3") (pin "3") (pinfunction "3_3") (pintype "passive"))
      (node (ref "Q3") (pin "3") (pinfunction "D_3") (pintype "bidirectional"))
      (node (ref "R23") (pin "1") (pinfunction "1_1") (pintype "passive"))
    )
    (net (code "85") (name "/PMIC_ON_REQ") (class "Default")
      (node (ref "IC8") (pin "K7") (pinfunction "PMIC_ON_REQ_K7") (pintype "bidirectional"))
      (node (ref "Q1") (pin "2") (pinfunction "S_2") (pintype "bidirectional"))
    )
    (net (code "86") (name "/PWM_FSIN") (class "Default")
      (node (ref "IC8") (pin "B7") (pinfunction "GPIO_EMC_39_B7") (pintype "bidirectional"))
      (node (ref "Q4") (pin "2") (pinfunction "S_2") (pintype "bidirectional"))
      (node (ref "Q5") (pin "2") (pinfunction "S_2") (pintype "bidirectional"))
      (node (ref "R25") (pin "1") (pinfunction "1_1") (pintype "passive"))
    )
    (net (code "87") (name "/P_FLASH_CE") (class "Default")
      (node (ref "IC5") (pin "1") (pinfunction "CE#_1") (pintype "bidirectional"))
      (node (ref "IC8") (pin "L3") (pinfunction "GPIO_SD_B1_06_L3") (pintype "bidirectional"))
      (node (ref "R13") (pin "2") (pinfunction "2_2") (pintype "passive"))
    )
    (net (code "88") (name "/P_FLASH_IO0") (class "Default")
      (node (ref "IC5") (pin "5") (pinfunction "SI_(IO0)_5") (pintype "bidirectional"))
      (node (ref "IC8") (pin "P3") (pinfunction "GPIO_SD_B1_08_P3") (pintype "bidirectional"))
    )
    (net (code "89") (name "/P_FLASH_IO1") (class "Default")
      (node (ref "IC5") (pin "2") (pinfunction "SO_(IO1)_2") (pintype "bidirectional"))
      (node (ref "IC8") (pin "N4") (pinfunction "GPIO_SD_B1_09_N4") (pintype "bidirectional"))
    )
    (net (code "90") (name "/P_FLASH_IO2") (class "Default")
      (node (ref "IC5") (pin "3") (pinfunction "WP#_(IO2)_3") (pintype "bidirectional"))
      (node (ref "IC8") (pin "P4") (pinfunction "GPIO_SD_B1_10_P4") (pintype "bidirectional"))
    )
    (net (code "91") (name "/P_FLASH_IO3") (class "Default")
      (node (ref "IC5") (pin "7") (pinfunction "HOLD#_(IO3)_7") (pintype "bidirectional"))
      (node (ref "IC8") (pin "P5") (pinfunction "GPIO_SD_B1_11_P5") (pintype "bidirectional"))
    )
    (net (code "92") (name "/P_FLASH_SCK") (class "Default")
      (node (ref "IC5") (pin "6") (pinfunction "SCK_6") (pintype "bidirectional"))
      (node (ref "IC8") (pin "L4") (pinfunction "GPIO_SD_B1_07_L4") (pintype "bidirectional"))
    )
    (net (code "93") (name "/RTC_XTALI") (class "Default")
      (node (ref "C80") (pin "1") (pinfunction "1_1") (pintype "passive"))
      (node (ref "IC8") (pin "N9") (pinfunction "RTC_XTALI_N9") (pintype "bidirectional"))
      (node (ref "Y1") (pin "2") (pinfunction "2_2") (pintype "passive"))
    )
    (net (code "94") (name "/RTC_XTALO") (class "Default")
      (node (ref "C79") (pin "1") (pinfunction "1_1") (pintype "passive"))
      (node (ref "IC8") (pin "P9") (pinfunction "RTC_XTALO_P9") (pintype "bidirectional"))
      (node (ref "Y1") (pin "1") (pinfunction "1_1") (pintype "passive"))
    )
    (net (code "95") (name "/SDRAM_A0") (class "Default")
      (node (ref "IC3") (pin "H7") (pinfunction "A0_H7") (pintype "bidirectional"))
      (node (ref "IC8") (pin "C2") (pinfunction "GPIO_EMC_09_C2") (pintype "bidirectional"))
    )
    (net (code "96") (name "/SDRAM_A1") (class "Default")
      (node (ref "IC3") (pin "H8") (pinfunction "A1_H8") (pintype "bidirectional"))
      (node (ref "IC8") (pin "G1") (pinfunction "GPIO_EMC_10_G1") (pintype "bidirectional"))
    )
    (net (code "97") (name "/SDRAM_A2") (class "Default")
      (node (ref "IC3") (pin "J8") (pinfunction "A2_J8") (pintype "bidirectional"))
      (node (ref "IC8") (pin "G3") (pinfunction "GPIO_EMC_11_G3") (pintype "bidirectional"))
    )
    (net (code "98") (name "/SDRAM_A3") (class "Default")
      (node (ref "IC3") (pin "J7") (pinfunction "A3_J7") (pintype "bidirectional"))
      (node (ref "IC8") (pin "H1") (pinfunction "GPIO_EMC_12_H1") (pintype "bidirectional"))
    )
    (net (code "99") (name "/SDRAM_A4") (class "Default")
      (node (ref "IC3") (pin "J3") (pinfunction "A4_J3") (pintype "bidirectional"))
      (node (ref "IC8") (pin "A6") (pinfunction "GPIO_EMC_13_A6") (pintype "bidirectional"))
    )
    (net (code "100") (name "/SDRAM_A5") (class "Default")
      (node (ref "IC3") (pin "J2") (pinfunction "A5_J2") (pintype "bidirectional"))
      (node (ref "IC8") (pin "B6") (pinfunction "GPIO_EMC_14_B6") (pintype "bidirectional"))
    )
    (net (code "101") (name "/SDRAM_A6") (class "Default")
      (node (ref "IC3") (pin "H3") (pinfunction "A6_H3") (pintype "bidirectional"))
      (node (ref "IC8") (pin "B1") (pinfunction "GPIO_EMC_15_B1") (pintype "bidirectional"))
    )
    (net (code "102") (name "/SDRAM_A7") (class "Default")
      (node (ref "IC3") (pin "H2") (pinfunction "A7_H2") (pintype "bidirectional"))
      (node (ref "IC8") (pin "A5") (pinfunction "GPIO_EMC_16_A5") (pintype "bidirectional"))
    )
    (net (code "103") (name "/SDRAM_A8") (class "Default")
      (node (ref "IC3") (pin "H1") (pinfunction "A8_H1") (pintype "bidirectional"))
      (node (ref "IC8") (pin "A4") (pinfunction "GPIO_EMC_17_A4") (pintype "bidirectional"))
    )
    (net (code "104") (name "/SDRAM_A9") (class "Default")
      (node (ref "IC3") (pin "G3") (pinfunction "A9_G3") (pintype "bidirectional"))
      (node (ref "IC8") (pin "B2") (pinfunction "GPIO_EMC_18_B2") (pintype "bidirectional"))
    )
    (net (code "105") (name "/SDRAM_A10") (class "Default")
      (node (ref "IC3") (pin "H9") (pinfunction "A10_H9") (pintype "bidirectional"))
      (node (ref "IC8") (pin "G2") (pinfunction "GPIO_EMC_23_G2") (pintype "bidirectional"))
    )
    (net (code "106") (name "/SDRAM_A11") (class "Default")
      (node (ref "IC3") (pin "G2") (pinfunction "A11_G2") (pintype "bidirectional"))
      (node (ref "IC8") (pin "B4") (pinfunction "GPIO_EMC_19_B4") (pintype "bidirectional"))
    )
    (net (code "107") (name "/SDRAM_A12") (class "Default")
      (node (ref "IC3") (pin "G1") (pinfunction "A12_G1") (pintype "bidirectional"))
      (node (ref "IC8") (pin "A3") (pinfunction "GPIO_EMC_20_A3") (pintype "bidirectional"))
    )
    (net (code "108") (name "/SDRAM_BA0") (class "Default")
      (node (ref "IC3") (pin "G7") (pinfunction "BA0_G7") (pintype "bidirectional"))
      (node (ref "IC8") (pin "C1") (pinfunction "GPIO_EMC_21_C1") (pintype "bidirectional"))
    )
    (net (code "109") (name "/SDRAM_BA1") (class "Default")
      (node (ref "IC3") (pin "G8") (pinfunction "BA1_G8") (pintype "bidirectional"))
      (node (ref "IC8") (pin "F1") (pinfunction "GPIO_EMC_22_F1") (pintype "bidirectional"))
    )
    (net (code "110") (name "/SDRAM_CAS") (class "Default")
      (node (ref "IC3") (pin "F7") (pinfunction "~{CAS}_F7") (pintype "bidirectional"))
      (node (ref "IC8") (pin "D3") (pinfunction "GPIO_EMC_24_D3") (pintype "bidirectional"))
    )
    (net (code "111") (name "/SDRAM_CKE") (class "Default")
      (node (ref "IC3") (pin "F3") (pinfunction "CKE_F3") (pintype "bidirectional"))
      (node (ref "IC8") (pin "A2") (pinfunction "GPIO_EMC_27_A2") (pintype "bidirectional"))
    )
    (net (code "112") (name "/SDRAM_CLK") (class "Default")
      (node (ref "IC3") (pin "F2") (pinfunction "CLK_F2") (pintype "bidirectional"))
      (node (ref "IC8") (pin "B3") (pinfunction "GPIO_EMC_26_B3") (pintype "bidirectional"))
    )
    (net (code "113") (name "/SDRAM_CS") (class "Default")
      (node (ref "IC3") (pin "G9") (pinfunction "~{CS}_G9") (pintype "bidirectional"))
      (node (ref "IC8") (pin "E1") (pinfunction "GPIO_EMC_29_E1") (pintype "bidirectional"))
      (node (ref "R18") (pin "2") (pinfunction "2_2") (pintype "passive"))
    )
    (net (code "114") (name "/SDRAM_DQ0") (class "Default")
      (node (ref "IC3") (pin "A8") (pinfunction "DQ0_A8") (pintype "bidirectional"))
      (node (ref "IC8") (pin "E3") (pinfunction "GPIO_EMC_00_E3") (pintype "bidirectional"))
    )
    (net (code "115") (name "/SDRAM_DQ1") (class "Default")
      (node (ref "IC3") (pin "B9") (pinfunction "DQ1_B9") (pintype "bidirectional"))
      (node (ref "IC8") (pin "F3") (pinfunction "GPIO_EMC_01_F3") (pintype "bidirectional"))
    )
    (net (code "116") (name "/SDRAM_DQ2") (class "Default")
      (node (ref "IC3") (pin "B8") (pinfunction "DQ2_B8") (pintype "bidirectional"))
      (node (ref "IC8") (pin "F4") (pinfunction "GPIO_EMC_02_F4") (pintype "bidirectional"))
    )
    (net (code "117") (name "/SDRAM_DQ3") (class "Default")
      (node (ref "IC3") (pin "C9") (pinfunction "DQ3_C9") (pintype "bidirectional"))
      (node (ref "IC8") (pin "G4") (pinfunction "GPIO_EMC_03_G4") (pintype "bidirectional"))
    )
    (net (code "118") (name "/SDRAM_DQ4") (class "Default")
      (node (ref "IC3") (pin "C8") (pinfunction "DQ4_C8") (pintype "bidirectional"))
      (node (ref "IC8") (pin "F2") (pinfunction "GPIO_EMC_04_F2") (pintype "bidirectional"))
    )
    (net (code "119") (name "/SDRAM_DQ5") (class "Default")
      (node (ref "IC3") (pin "D9") (pinfunction "DQ5_D9") (pintype "bidirectional"))
      (node (ref "IC8") (pin "G5") (pinfunction "GPIO_EMC_05_G5") (pintype "bidirectional"))
    )
    (net (code "120") (name "/SDRAM_DQ6") (class "Default")
      (node (ref "IC3") (pin "D8") (pinfunction "DQ6_D8") (pintype "bidirectional"))
      (node (ref "IC8") (pin "H5") (pinfunction "GPIO_EMC_06_H5") (pintype "bidirectional"))
    )
    (net (code "121") (name "/SDRAM_DQ7") (class "Default")
      (node (ref "IC3") (pin "E9") (pinfunction "DQ7_E9") (pintype "bidirectional"))
      (node (ref "IC8") (pin "H4") (pinfunction "GPIO_EMC_07_H4") (pintype "bidirectional"))
    )
    (net (code "122") (name "/SDRAM_DQ8") (class "Default")
      (node (ref "IC3") (pin "E1") (pinfunction "DQ8_E1") (pintype "bidirectional"))
      (node (ref "IC8") (pin "C6") (pinfunction "GPIO_EMC_30_C6") (pintype "bidirectional"))
    )
    (net (code "123") (name "/SDRAM_DQ9") (class "Default")
      (node (ref "IC3") (pin "D2") (pinfunction "DQ9_D2") (pintype "bidirectional"))
      (node (ref "IC8") (pin "C5") (pinfunction "GPIO_EMC_31_C5") (pintype "bidirectional"))
    )
    (net (code "124") (name "/SDRAM_DQ10") (class "Default")
      (node (ref "IC3") (pin "D1") (pinfunction "DQ10_D1") (pintype "bidirectional"))
      (node (ref "IC8") (pin "D5") (pinfunction "GPIO_EMC_32_D5") (pintype "bidirectional"))
    )
    (net (code "125") (name "/SDRAM_DQ11") (class "Default")
      (node (ref "IC3") (pin "C2") (pinfunction "DQ11_C2") (pintype "bidirectional"))
      (node (ref "IC8") (pin "C4") (pinfunction "GPIO_EMC_33_C4") (pintype "bidirectional"))
    )
    (net (code "126") (name "/SDRAM_DQ12") (class "Default")
      (node (ref "IC3") (pin "C1") (pinfunction "DQ12_C1") (pintype "bidirectional"))
      (node (ref "IC8") (pin "D4") (pinfunction "GPIO_EMC_34_D4") (pintype "bidirectional"))
    )
    (net (code "127") (name "/SDRAM_DQ13") (class "Default")
      (node (ref "IC3") (pin "B2") (pinfunction "DQ13_B2") (pintype "bidirectional"))
      (node (ref "IC8") (pin "E5") (pinfunction "GPIO_EMC_35_E5") (pintype "bidirectional"))
    )
    (net (code "128") (name "/SDRAM_DQ14") (class "Default")
      (node (ref "IC3") (pin "B1") (pinfunction "DQ14_B1") (pintype "bidirectional"))
      (node (ref "IC8") (pin "C3") (pinfunction "GPIO_EMC_36_C3") (pintype "bidirectional"))
    )
    (net (code "129") (name "/SDRAM_DQ15") (class "Default")
      (node (ref "IC3") (pin "A2") (pinfunction "DQ15_A2") (pintype "bidirectional"))
      (node (ref "IC8") (pin "E4") (pinfunction "GPIO_EMC_37_E4") (pintype "bidirectional"))
    )
    (net (code "130") (name "/SDRAM_DQMH") (class "Default")
      (node (ref "IC3") (pin "F1") (pinfunction "DQMH_F1") (pintype "bidirectional"))
      (node (ref "IC8") (pin "D6") (pinfunction "GPIO_EMC_38_D6") (pintype "bidirectional"))
    )
    (net (code "131") (name "/SDRAM_DQML") (class "Default")
      (node (ref "IC3") (pin "E8") (pinfunction "DQML_E8") (pintype "bidirectional"))
      (node (ref "IC8") (pin "H3") (pinfunction "GPIO_EMC_08_H3") (pintype "bidirectional"))
    )
    (net (code "132") (name "/SDRAM_RAS") (class "Default")
      (node (ref "IC3") (pin "F8") (pinfunction "~{RAS}_F8") (pintype "bidirectional"))
      (node (ref "IC8") (pin "D2") (pinfunction "GPIO_EMC_25_D2") (pintype "bidirectional"))
    )
    (net (code "133") (name "/SDRAM_WE") (class "Default")
      (node (ref "IC3") (pin "F9") (pinfunction "~{WE}_F9") (pintype "bidirectional"))
      (node (ref "IC8") (pin "D1") (pinfunction "GPIO_EMC_28_D1") (pintype "bidirectional"))
    )
    (net (code "134") (name "/SD_CD") (class "Default")
      (node (ref "D9") (pin "1") (pinfunction "1_1") (pintype "bidirectional"))
      (node (ref "IC8") (pin "L11") (pinfunction "GPIO_AD_B1_02_L11") (pintype "bidirectional"))
      (node (ref "J5") (pin "CD$1") (pinfunction "CD_CD$1") (pintype "power_in"))
      (node (ref "RN1") (pin "9") (pinfunction "9_9") (pintype "bidirectional"))
    )
    (net (code "135") (name "/SD_CLK") (class "Default")
      (node (ref "FL3") (pin "4") (pinfunction "INPUT_4_4") (pintype "bidirectional"))
      (node (ref "IC8") (pin "J3") (pinfunction "GPIO_SD_B0_01_J3") (pintype "bidirectional"))
    )
    (net (code "136") (name "/SD_CLK_INT") (class "Default")
      (node (ref "FL3") (pin "9") (pinfunction "OUTPUT_4_9") (pintype "bidirectional"))
      (node (ref "J5") (pin "P$5") (pinfunction "CLK_P$5") (pintype "bidirectional"))
    )
    (net (code "137") (name "/SD_CMD") (class "Default")
      (node (ref "FL3") (pin "3") (pinfunction "INPUT_3_3") (pintype "bidirectional"))
      (node (ref "IC8") (pin "J4") (pinfunction "GPIO_SD_B0_00_J4") (pintype "bidirectional"))
      (node (ref "RN1") (pin "12") (pinfunction "12_12") (pintype "bidirectional"))
    )
    (net (code "138") (name "/SD_CMD_INT") (class "Default")
      (node (ref "FL3") (pin "10") (pinfunction "OUTPUT_3_10") (pintype "bidirectional"))
      (node (ref "J5") (pin "P$3") (pinfunction "CMD_P$3") (pintype "bidirectional"))
    )
    (net (code "139") (name "/SD_DAT0") (class "Default")
      (node (ref "FL3") (pin "5") (pinfunction "INPUT_5_5") (pintype "bidirectional"))
      (node (ref "IC8") (pin "J1") (pinfunction "GPIO_SD_B0_02_J1") (pintype "bidirectional"))
      (node (ref "RN1") (pin "14") (pinfunction "14_14") (pintype "bidirectional"))
    )
    (net (code "140") (name "/SD_DAT0_INT") (class "Default")
      (node (ref "FL3") (pin "8") (pinfunction "OUTPUT_5_8") (pintype "bidirectional"))
      (node (ref "J5") (pin "P$7") (pinfunction "DAT0_P$7") (pintype "bidirectional"))
    )
    (net (code "141") (name "/SD_DAT1") (class "Default")
      (node (ref "FL3") (pin "6") (pinfunction "INPUT_6_6") (pintype "bidirectional"))
      (node (ref "IC8") (pin "K1") (pinfunction "GPIO_SD_B0_03_K1") (pintype "bidirectional"))
      (node (ref "RN1") (pin "13") (pinfunction "13_13") (pintype "bidirectional"))
    )
    (net (code "142") (name "/SD_DAT1_INT") (class "Default")
      (node (ref "FL3") (pin "7") (pinfunction "OUTPUT_6_7") (pintype "bidirectional"))
      (node (ref "J5") (pin "P$8") (pinfunction "DAT1_P$8") (pintype "bidirectional"))
    )
    (net (code "143") (name "/SD_DAT2") (class "Default")
      (node (ref "FL3") (pin "1") (pinfunction "INPUT_1_1") (pintype "bidirectional"))
      (node (ref "IC8") (pin "H2") (pinfunction "GPIO_SD_B0_04_H2") (pintype "bidirectional"))
      (node (ref "RN1") (pin "10") (pinfunction "10_10") (pintype "bidirectional"))
    )
    (net (code "144") (name "/SD_DAT2_INT") (class "Default")
      (node (ref "FL3") (pin "12") (pinfunction "OUTPUT_1_12") (pintype "bidirectional"))
      (node (ref "J5") (pin "P$1") (pinfunction "DAT2_P$1") (pintype "bidirectional"))
    )
    (net (code "145") (name "/SD_DAT3") (class "Default")
      (node (ref "FL3") (pin "2") (pinfunction "INPUT_2_2") (pintype "bidirectional"))
      (node (ref "IC8") (pin "J2") (pinfunction "GPIO_SD_B0_05_J2") (pintype "bidirectional"))
      (node (ref "RN1") (pin "11") (pinfunction "11_11") (pintype "bidirectional"))
    )
    (net (code "146") (name "/SD_DAT3_INT") (class "Default")
      (node (ref "FL3") (pin "11") (pinfunction "OUTPUT_2_11") (pintype "bidirectional"))
      (node (ref "J5") (pin "P$2") (pinfunction "DAT3/CD_P$2") (pintype "bidirectional"))
    )
    (net (code "147") (name "/S_FLASH_CE") (class "Default")
      (node (ref "IC6") (pin "1") (pinfunction "CE#_1") (pintype "bidirectional"))
      (node (ref "IC8") (pin "N3") (pinfunction "GPIO_SD_B1_05_N3") (pintype "bidirectional"))
      (node (ref "R14") (pin "2") (pinfunction "2_2") (pintype "passive"))
    )
    (net (code "148") (name "/S_FLASH_IO0") (class "Default")
      (node (ref "IC6") (pin "5") (pinfunction "SI_(IO0)_5") (pintype "bidirectional"))
      (node (ref "IC8") (pin "M4") (pinfunction "GPIO_SD_B1_03_M4") (pintype "bidirectional"))
    )
    (net (code "149") (name "/S_FLASH_IO1") (class "Default")
      (node (ref "IC6") (pin "2") (pinfunction "SO_(IO1)_2") (pintype "bidirectional"))
      (node (ref "IC8") (pin "M3") (pinfunction "GPIO_SD_B1_02_M3") (pintype "bidirectional"))
    )
    (net (code "150") (name "/S_FLASH_IO2") (class "Default")
      (node (ref "IC6") (pin "3") (pinfunction "WP#_(IO2)_3") (pintype "bidirectional"))
      (node (ref "IC8") (pin "M5") (pinfunction "GPIO_SD_B1_01_M5") (pintype "bidirectional"))
    )
    (net (code "151") (name "/S_FLASH_IO3") (class "Default")
      (node (ref "IC6") (pin "7") (pinfunction "HOLD#_(IO3)_7") (pintype "bidirectional"))
      (node (ref "IC8") (pin "L5") (pinfunction "GPIO_SD_B1_00_L5") (pintype "bidirectional"))
    )
    (net (code "152") (name "/S_FLASH_SCK") (class "Default")
      (node (ref "IC6") (pin "6") (pinfunction "SCK_6") (pintype "bidirectional"))
      (node (ref "IC8") (pin "P2") (pinfunction "GPIO_SD_B1_04_P2") (pintype "bidirectional"))
    )
    (net (code "153") (name "/USB_D_N") (class "Default")
      (node (ref "FL1") (pin "6") (pinfunction "D+_2_6") (pintype "bidirectional"))
      (node (ref "IC8") (pin "M8") (pinfunction "USB_OTG1_DN_M8") (pintype "bidirectional"))
    )
    (net (code "154") (name "/USB_D_P") (class "Default")
      (node (ref "FL1") (pin "7") (pinfunction "D-_2_7") (pintype "bidirectional"))
      (node (ref "IC8") (pin "L8") (pinfunction "USB_OTG1_DP_L8") (pintype "bidirectional"))
    )
    (net (code "155") (name "/VCC_SOC") (class "Default")
      (node (ref "C100") (pin "2") (pinfunction "2_2") (pintype "passive"))
      (node (ref "C103") (pin "2") (pinfunction "2_2") (pintype "passive"))
      (node (ref "C34") (pin "1") (pinfunction "1_1") (pintype "passive"))
      (node (ref "C38") (pin "1") (pinfunction "1_1") (pintype "passive"))
      (node (ref "C45") (pin "1") (pinfunction "1_1") (pintype "passive"))
      (node (ref "C46") (pin "2") (pinfunction "2_2") (pintype "passive"))
      (node (ref "C47") (pin "1") (pinfunction "1_1") (pintype "passive"))
      (node (ref "C48") (pin "1") (pinfunction "1_1") (pintype "passive"))
      (node (ref "C49") (pin "2") (pinfunction "2_2") (pintype "passive"))
      (node (ref "C87") (pin "2") (pinfunction "2_2") (pintype "passive"))
      (node (ref "C94") (pin "2") (pinfunction "2_2") (pintype "passive"))
      (node (ref "C97") (pin "2") (pinfunction "2_2") (pintype "passive"))
      (node (ref "C98") (pin "2") (pinfunction "2_2") (pintype "passive"))
      (node (ref "IC8") (pin "F6") (pinfunction "VDD_SOC_IN_1_F6") (pintype "bidirectional"))
      (node (ref "IC8") (pin "F7") (pinfunction "VDD_SOC_IN_2_F7") (pintype "bidirectional"))
      (node (ref "IC8") (pin "F8") (pinfunction "VDD_SOC_IN_3_F8") (pintype "bidirectional"))
      (node (ref "IC8") (pin "F9") (pinfunction "VDD_SOC_IN_4_F9") (pintype "bidirectional"))
      (node (ref "IC8") (pin "G6") (pinfunction "VDD_SOC_IN_5_G6") (pintype "bidirectional"))
      (node (ref "IC8") (pin "G9") (pinfunction "VDD_SOC_IN_6_G9") (pintype "bidirectional"))
      (node (ref "IC8") (pin "H6") (pinfunction "VDD_SOC_IN_7_H6") (pintype "bidirectional"))
      (node (ref "IC8") (pin "H9") (pinfunction "VDD_SOC_IN_8_H9") (pintype "bidirectional"))
      (node (ref "IC8") (pin "J5") (pinfunction "DCDC_SENSE_J5") (pintype "bidirectional"))
      (node (ref "IC8") (pin "J9") (pinfunction "VDD_SOC_IN_9_J9") (pintype "bidirectional"))
      (node (ref "L5") (pin "1") (pinfunction "1_1") (pintype "passive"))
    )
    (net (code "156") (name "/VDDA") (class "Default")
      (node (ref "C51") (pin "1") (pinfunction "1_1") (pintype "passive"))
      (node (ref "C52") (pin "2") (pinfunction "2_2") (pintype "passive"))
      (node (ref "J4") (pin "4") (pinfunction "4_4") (pintype "bidirectional"))
      (node (ref "L4") (pin "1") (pinfunction "1_1") (pintype "passive"))
    )
    (net (code "157") (name "/VDDA_ADC_3P3") (class "Default")
      (node (ref "C59") (pin "1") (pinfunction "1_1") (pintype "passive"))
      (node (ref "C60") (pin "2") (pinfunction "2_2") (pintype "passive"))
      (node (ref "C61") (pin "2") (pinfunction "2_2") (pintype "passive"))
      (node (ref "IC8") (pin "N14") (pinfunction "VDDA_ADC_3P3_N14") (pintype "bidirectional"))
      (node (ref "L6") (pin "1") (pinfunction "1_1") (pintype "passive"))
    )
    (net (code "158") (name "/VDD_HIGH_CAP") (class "Default")
      (node (ref "C101") (pin "2") (pinfunction "2_2") (pintype "passive"))
      (node (ref "C102") (pin "1") (pinfunction "1_1") (pintype "passive"))
      (node (ref "IC8") (pin "P8") (pinfunction "VDD_HIGH_CAP_P8") (pintype "bidirectional"))
    )
    (net (code "159") (name "/VDD_SNVS") (class "Default")
      (node (ref "C2") (pin "2") (pinfunction "2_2") (pintype "passive"))
      (node (ref "C69") (pin "1") (pinfunction "1_1") (pintype "passive"))
      (node (ref "IC8") (pin "M9") (pinfunction "VDD_SNVS_IN_M9") (pintype "bidirectional"))
      (node (ref "U1") (pin "1") (pinfunction "VOUT_1") (pintype "bidirectional"))
    )
    (net (code "160") (name "/VDD_SNVS_CAP") (class "Default")
      (node (ref "C70") (pin "1") (pinfunction "1_1") (pintype "passive"))
      (node (ref "IC8") (pin "M10") (pinfunction "VDD_SNVS_CAP_M10") (pintype "bidirectional"))
    )
    (net (code "161") (name "/VDD_USB_CAP") (class "Default")
      (node (ref "C71") (pin "1") (pinfunction "1_1") (pintype "passive"))
      (node (ref "C72") (pin "2") (pinfunction "2_2") (pintype "passive"))
      (node (ref "C73") (pin "2") (pinfunction "2_2") (pintype "passive"))
      (node (ref "IC8") (pin "K8") (pinfunction "VDD_USB_CAP_K8") (pintype "bidirectional"))
    )
    (net (code "162") (name "/WAKEUP") (class "Default")
      (node (ref "IC8") (pin "L6") (pinfunction "WAKEUP_L6") (pintype "bidirectional"))
      (node (ref "Q2") (pin "2") (pinfunction "S_2") (pintype "bidirectional"))
    )
    (net (code "163") (name "/WIFI_CLK") (class "Default")
      (node (ref "IC8") (pin "M13") (pinfunction "GPIO_AD_B1_09_M13") (pintype "bidirectional"))
      (node (ref "U3") (pin "20") (pinfunction "SDIO_CLK_20") (pintype "input"))
    )
    (net (code "164") (name "/WIFI_CMD") (class "Default")
      (node (ref "IC8") (pin "H13") (pinfunction "GPIO_AD_B1_08_H13") (pintype "bidirectional"))
      (node (ref "RN2") (pin "16") (pinfunction "16_16") (pintype "bidirectional"))
      (node (ref "U3") (pin "22") (pinfunction "SDIO_CMD_22") (pintype "bidirectional"))
    )
    (net (code "165") (name "/WIFI_D0") (class "Default")
      (node (ref "IC8") (pin "L12") (pinfunction "GPIO_AD_B1_04_L12") (pintype "bidirectional"))
      (node (ref "RN2") (pin "14") (pinfunction "14_14") (pintype "bidirectional"))
      (node (ref "U3") (pin "24") (pinfunction "SDIO_DATA_0_24") (pintype "bidirectional"))
    )
    (net (code "166") (name "/WIFI_D1") (class "Default")
      (node (ref "IC8") (pin "K12") (pinfunction "GPIO_AD_B1_05_K12") (pintype "bidirectional"))
      (node (ref "RN2") (pin "12") (pinfunction "12_12") (pintype "bidirectional"))
      (node (ref "U3") (pin "26") (pinfunction "SDIO_DATA_1_26") (pintype "bidirectional"))
    )
    (net (code "167") (name "/WIFI_D2") (class "Default")
      (node (ref "IC8") (pin "J12") (pinfunction "GPIO_AD_B1_06_J12") (pintype "bidirectional"))
      (node (ref "RN2") (pin "15") (pinfunction "15_15") (pintype "bidirectional"))
      (node (ref "U3") (pin "23") (pinfunction "SDIO_DATA_2_23") (pintype "bidirectional"))
    )
    (net (code "168") (name "/WIFI_D3") (class "Default")
      (node (ref "IC8") (pin "K10") (pinfunction "GPIO_AD_B1_07_K10") (pintype "bidirectional"))
      (node (ref "RN2") (pin "13") (pinfunction "13_13") (pintype "bidirectional"))
      (node (ref "U3") (pin "25") (pinfunction "SDIO_DATA_3_25") (pintype "bidirectional"))
    )
    (net (code "169") (name "/WL_H_WAKE") (class "Default")
      (node (ref "IC8") (pin "E11") (pinfunction "GPIO_B0_15_E11") (pintype "bidirectional"))
      (node (ref "U3") (pin "27") (pinfunction "WL_GPIO_0_HOST_WAKE_27") (pintype "bidirectional"))
    )
    (net (code "170") (name "/WL_REG_ON") (class "Default")
      (node (ref "IC8") (pin "E10") (pinfunction "GPIO_B0_14_E10") (pintype "bidirectional"))
      (node (ref "U3") (pin "28") (pinfunction "WL_REG_ON_28") (pintype "input"))
    )
    (net (code "171") (name "/XTALI") (class "Default")
      (node (ref "C106") (pin "1") (pinfunction "1_1") (pintype "passive"))
      (node (ref "IC8") (pin "P11") (pinfunction "XTALI_P11") (pintype "bidirectional"))
      (node (ref "R40") (pin "1") (pinfunction "1_1") (pintype "passive"))
      (node (ref "Y2") (pin "3") (pinfunction "CRYSTAL_2_3") (pintype "bidirectional"))
    )
    (net (code "172") (name "/XTALO") (class "Default")
      (node (ref "C105") (pin "1") (pinfunction "1_1") (pintype "passive"))
      (node (ref "IC8") (pin "N11") (pinfunction "XTALO_N11") (pintype "bidirectional"))
      (node (ref "Y2") (pin "1") (pinfunction "CRYSTAL_1_1") (pintype "bidirectional"))
    )
    (net (code "173") (name "GND") (class "Default")
      (node (ref "C1") (pin "1") (pinfunction "1_1") (pintype "passive"))
      (node (ref "C10") (pin "1") (pinfunction "1_1") (pintype "passive"))
      (node (ref "C100") (pin "1") (pinfunction "1_1") (pintype "passive"))
      (node (ref "C101") (pin "1") (pinfunction "1_1") (pintype "passive"))
      (node (ref "C102") (pin "2") (pinfunction "2_2") (pintype "passive"))
      (node (ref "C103") (pin "1") (pinfunction "1_1") (pintype "passive"))
      (node (ref "C104") (pin "1") (pinfunction "1_1") (pintype "passive"))
      (node (ref "C105") (pin "2") (pinfunction "2_2") (pintype "passive"))
      (node (ref "C106") (pin "2") (pinfunction "2_2") (pintype "passive"))
      (node (ref "C107") (pin "2") (pinfunction "2_2") (pintype "passive"))
      (node (ref "C108") (pin "1") (pinfunction "1_1") (pintype "passive"))
      (node (ref "C109") (pin "2") (pinfunction "2_2") (pintype "passive"))
      (node (ref "C11") (pin "1") (pinfunction "1_1") (pintype "passive"))
      (node (ref "C110") (pin "1") (pinfunction "1_1") (pintype "passive"))
      (node (ref "C12") (pin "2") (pinfunction "2_2") (pintype "passive"))
      (node (ref "C13") (pin "2") (pinfunction "2_2") (pintype "passive"))
      (node (ref "C14") (pin "2") (pinfunction "2_2") (pintype "passive"))
      (node (ref "C15") (pin "2") (pinfunction "2_2") (pintype "passive"))
      (node (ref "C16") (pin "2") (pinfunction "2_2") (pintype "passive"))
      (node (ref "C17") (pin "1") (pinfunction "1_1") (pintype "passive"))
      (node (ref "C18") (pin "1") (pinfunction "1_1") (pintype "passive"))
      (node (ref "C19") (pin "2") (pinfunction "2_2") (pintype "passive"))
      (node (ref "C2") (pin "1") (pinfunction "1_1") (pintype "passive"))
      (node (ref "C20") (pin "2") (pinfunction "2_2") (pintype "passive"))
      (node (ref "C21") (pin "1") (pinfunction "1_1") (pintype "passive"))
      (node (ref "C22") (pin "2") (pinfunction "2_2") (pintype "passive"))
      (node (ref "C23") (pin "1") (pinfunction "1_1") (pintype "passive"))
      (node (ref "C24") (pin "2") (pinfunction "2_2") (pintype "passive"))
      (node (ref "C25") (pin "1") (pinfunction "1_1") (pintype "passive"))
      (node (ref "C26") (pin "2") (pinfunction "2_2") (pintype "passive"))
      (node (ref "C27") (pin "1") (pinfunction "1_1") (pintype "passive"))
      (node (ref "C28") (pin "2") (pinfunction "2_2") (pintype "passive"))
      (node (ref "C29") (pin "2") (pinfunction "2_2") (pintype "passive"))
      (node (ref "C3") (pin "1") (pinfunction "1_1") (pintype "passive"))
      (node (ref "C30") (pin "2") (pinfunction "2_2") (pintype "passive"))
      (node (ref "C31") (pin "1") (pinfunction "1_1") (pintype "passive"))
      (node (ref "C32") (pin "2") (pinfunction "2_2") (pintype "passive"))
      (node (ref "C33") (pin "1") (pinfunction "1_1") (pintype "passive"))
      (node (ref "C34") (pin "2") (pinfunction "2_2") (pintype "passive"))
      (node (ref "C35") (pin "1") (pinfunction "1_1") (pintype "passive"))
      (node (ref "C36") (pin "2") (pinfunction "2_2") (pintype "passive"))
      (node (ref "C37") (pin "2") (pinfunction "2_2") (pintype "passive"))
      (node (ref "C38") (pin "2") (pinfunction "2_2") (pintype "passive"))
      (node (ref "C39") (pin "1") (pinfunction "1_1") (pintype "passive"))
      (node (ref "C4") (pin "1") (pinfunction "1_1") (pintype "passive"))
      (node (ref "C40") (pin "1") (pinfunction "1_1") (pintype "passive"))
      (node (ref "C41") (pin "1") (pinfunction "1_1") (pintype "passive"))
      (node (ref "C42") (pin "1") (pinfunction "1_1") (pintype "passive"))
      (node (ref "C43") (pin "2") (pinfunction "2_2") (pintype "passive"))
      (node (ref "C44") (pin "1") (pinfunction "1_1") (pintype "passive"))
      (node (ref "C45") (pin "2") (pinfunction "2_2") (pintype "passive"))
      (node (ref "C46") (pin "1") (pinfunction "1_1") (pintype "passive"))
      (node (ref "C47") (pin "2") (pinfunction "2_2") (pintype "passive"))
      (node (ref "C48") (pin "2") (pinfunction "2_2") (pintype "passive"))
      (node (ref "C49") (pin "1") (pinfunction "1_1") (pintype "passive"))
      (node (ref "C5") (pin "1") (pinfunction "1_1") (pintype "passive"))
      (node (ref "C50") (pin "2") (pinfunction "2_2") (pintype "passive"))
      (node (ref "C51") (pin "2") (pinfunction "2_2") (pintype "passive"))
      (node (ref "C52") (pin "1") (pinfunction "1_1") (pintype "passive"))
      (node (ref "C53") (pin "2") (pinfunction "2_2") (pintype "passive"))
      (node (ref "C54") (pin "2") (pinfunction "2_2") (pintype "passive"))
      (node (ref "C55") (pin "2") (pinfunction "2_2") (pintype "passive"))
      (node (ref "C56") (pin "2") (pinfunction "2_2") (pintype "passive"))
      (node (ref "C57") (pin "1") (pinfunction "1_1") (pintype "passive"))
      (node (ref "C58") (pin "1") (pinfunction "1_1") (pintype "passive"))
      (node (ref "C59") (pin "2") (pinfunction "2_2") (pintype "passive"))
      (node (ref "C6") (pin "2") (pinfunction "2_2") (pintype "passive"))
      (node (ref "C60") (pin "1") (pinfunction "1_1") (pintype "passive"))
      (node (ref "C61") (pin "1") (pinfunction "1_1") (pintype "passive"))
      (node (ref "C62") (pin "2") (pinfunction "2_2") (pintype "passive"))
      (node (ref "C63") (pin "2") (pinfunction "2_2") (pintype "passive"))
      (node (ref "C64") (pin "2") (pinfunction "2_2") (pintype "passive"))
      (node (ref "C65") (pin "1") (pinfunction "1_1") (pintype "passive"))
      (node (ref "C66") (pin "1") (pinfunction "1_1") (pintype "passive"))
      (node (ref "C67") (pin "2") (pinfunction "2_2") (pintype "passive"))
      (node (ref "C68") (pin "1") (pinfunction "1_1") (pintype "passive"))
      (node (ref "C69") (pin "2") (pinfunction "2_2") (pintype "passive"))
      (node (ref "C7") (pin "2") (pinfunction "2_2") (pintype "passive"))
      (node (ref "C70") (pin "2") (pinfunction "2_2") (pintype "passive"))
      (node (ref "C71") (pin "2") (pinfunction "2_2") (pintype "passive"))
      (node (ref "C72") (pin "1") (pinfunction "1_1") (pintype "passive"))
      (node (ref "C73") (pin "1") (pinfunction "1_1") (pintype "passive"))
      (node (ref "C74") (pin "2") (pinfunction "2_2") (pintype "passive"))
      (node (ref "C75") (pin "2") (pinfunction "2_2") (pintype "passive"))
      (node (ref "C76") (pin "2") (pinfunction "2_2") (pintype "passive"))
      (node (ref "C77") (pin "2") (pinfunction "2_2") (pintype "bidirectional"))
      (node (ref "C78") (pin "2") (pinfunction "2_2") (pintype "bidirectional"))
      (node (ref "C79") (pin "2") (pinfunction "2_2") (pintype "passive"))
      (node (ref "C8") (pin "1") (pinfunction "1_1") (pintype "passive"))
      (node (ref "C80") (pin "2") (pinfunction "2_2") (pintype "passive"))
      (node (ref "C81") (pin "1") (pinfunction "1_1") (pintype "passive"))
      (node (ref "C82") (pin "2") (pinfunction "2_2") (pintype "passive"))
      (node (ref "C83") (pin "1") (pinfunction "1_1") (pintype "passive"))
      (node (ref "C84") (pin "2") (pinfunction "2_2") (pintype "passive"))
      (node (ref "C85") (pin "2") (pinfunction "2_2") (pintype "passive"))
      (node (ref "C86") (pin "1") (pinfunction "1_1") (pintype "passive"))
      (node (ref "C87") (pin "1") (pinfunction "1_1") (pintype "passive"))
      (node (ref "C88") (pin "2") (pinfunction "2_2") (pintype "passive"))
      (node (ref "C89") (pin "2") (pinfunction "2_2") (pintype "passive"))
      (node (ref "C9") (pin "1") (pinfunction "1_1") (pintype "passive"))
      (node (ref "C90") (pin "1") (pinfunction "1_1") (pintype "passive"))
      (node (ref "C91") (pin "1") (pinfunction "1_1") (pintype "passive"))
      (node (ref "C92") (pin "1") (pinfunction "1_1") (pintype "passive"))
      (node (ref "C93") (pin "1") (pinfunction "1_1") (pintype "passive"))
      (node (ref "C94") (pin "1") (pinfunction "1_1") (pintype "passive"))
      (node (ref "C95") (pin "1") (pinfunction "1_1") (pintype "passive"))
      (node (ref "C96") (pin "2") (pinfunction "2_2") (pintype "passive"))
      (node (ref "C97") (pin "1") (pinfunction "1_1") (pintype "passive"))
      (node (ref "C98") (pin "1") (pinfunction "1_1") (pintype "passive"))
      (node (ref "C99") (pin "1") (pinfunction "1_1") (pintype "passive"))
      (node (ref "CN1") (pin "2") (pinfunction "1_2") (pintype "passive"))
      (node (ref "D10") (pin "2") (pinfunction "2_2") (pintype "bidirectional"))
      (node (ref "D2") (pin "2") (pinfunction "2_2") (pintype "bidirectional"))
      (node (ref "D4") (pin "2") (pinfunction "2_2") (pintype "bidirectional"))
      (node (ref "D5") (pin "2") (pinfunction "2_2") (pintype "bidirectional"))
      (node (ref "D6") (pin "2") (pinfunction "2_2") (pintype "bidirectional"))
      (node (ref "D7") (pin "2") (pinfunction "2_2") (pintype "bidirectional"))
      (node (ref "D8") (pin "2") (pinfunction "2_2") (pintype "bidirectional"))
      (node (ref "D9") (pin "2") (pinfunction "2_2") (pintype "bidirectional"))
      (node (ref "FL1") (pin "5") (pinfunction "GND_1_5") (pintype "bidirectional"))
      (node (ref "FL1") (pin "8") (pinfunction "GND_2_8") (pintype "bidirectional"))
      (node (ref "FL2") (pin "13") (pinfunction "EP_13") (pintype "bidirectional"))
      (node (ref "FL3") (pin "13") (pinfunction "EP_13") (pintype "bidirectional"))
      (node (ref "FL4") (pin "13") (pinfunction "EP_13") (pintype "bidirectional"))
      (node (ref "FL5") (pin "13") (pinfunction "EP_13") (pintype "bidirectional"))
      (node (ref "IC1") (pin "1") (pinfunction "GND_1_1") (pintype "bidirectional"))
      (node (ref "IC1") (pin "4") (pinfunction "~{ON}_4") (pintype "bidirectional"))
      (node (ref "IC1") (pin "5") (pinfunction "GND_2_5") (pintype "bidirectional"))
      (node (ref "IC2") (pin "2") (pinfunction "GND_2") (pintype "bidirectional"))
      (node (ref "IC3") (pin "A1") (pinfunction "VSS_1_A1") (pintype "bidirectional"))
      (node (ref "IC3") (pin "A3") (pinfunction "VSSQ_1_A3") (pintype "bidirectional"))
      (node (ref "IC3") (pin "B7") (pinfunction "VSSQ_2_B7") (pintype "bidirectional"))
      (node (ref "IC3") (pin "C3") (pinfunction "VSSQ_3_C3") (pintype "bidirectional"))
      (node (ref "IC3") (pin "D7") (pinfunction "VSSQ_4_D7") (pintype "bidirectional"))
      (node (ref "IC3") (pin "E3") (pinfunction "VSS_2_E3") (pintype "bidirectional"))
      (node (ref "IC3") (pin "J1") (pinfunction "VSS_3_J1") (pintype "bidirectional"))
      (node (ref "IC4") (pin "4") (pinfunction "GND_4") (pintype "bidirectional"))
      (node (ref "IC4") (pin "9") (pinfunction "EP_9") (pintype "bidirectional"))
      (node (ref "IC5") (pin "4") (pinfunction "GND_4") (pintype "bidirectional"))
      (node (ref "IC5") (pin "9") (pinfunction "EP_9") (pintype "bidirectional"))
      (node (ref "IC6") (pin "4") (pinfunction "GND_4") (pintype "bidirectional"))
      (node (ref "IC6") (pin "9") (pinfunction "EP_9") (pintype "bidirectional"))
      (node (ref "IC7") (pin "3") (pinfunction "GND_3") (pintype "bidirectional"))
      (node (ref "IC8") (pin "A1") (pinfunction "VSS_1_A1") (pintype "bidirectional"))
      (node (ref "IC8") (pin "A14") (pinfunction "VSS_2_A14") (pintype "bidirectional"))
      (node (ref "IC8") (pin "B10") (pinfunction "VSS_4_B10") (pintype "bidirectional"))
      (node (ref "IC8") (pin "B5") (pinfunction "VSS_3_B5") (pintype "bidirectional"))
      (node (ref "IC8") (pin "E13") (pinfunction "VSS_6_E13") (pintype "bidirectional"))
      (node (ref "IC8") (pin "E2") (pinfunction "VSS_5_E2") (pintype "bidirectional"))
      (node (ref "IC8") (pin "G7") (pinfunction "VSS_7_G7") (pintype "bidirectional"))
      (node (ref "IC8") (pin "G8") (pinfunction "VSS_8_G8") (pintype "bidirectional"))
      (node (ref "IC8") (pin "H7") (pinfunction "VSS_9_H7") (pintype "bidirectional"))
      (node (ref "IC8") (pin "H8") (pinfunction "VSS_10_H8") (pintype "bidirectional"))
      (node (ref "IC8") (pin "J7") (pinfunction "VSS_11_J7") (pintype "bidirectional"))
      (node (ref "IC8") (pin "J8") (pinfunction "VSS_12_J8") (pintype "bidirectional"))
      (node (ref "IC8") (pin "K13") (pinfunction "VSS_14_K13") (pintype "bidirectional"))
      (node (ref "IC8") (pin "K2") (pinfunction "VSS_13_K2") (pintype "bidirectional"))
      (node (ref "IC8") (pin "K6") (pinfunction "TEST_MODE_K6") (pintype "bidirectional"))
      (node (ref "IC8") (pin "K9") (pinfunction "NGND_KEL0_K9") (pintype "bidirectional"))
      (node (ref "IC8") (pin "L9") (pinfunction "VSS_15_L9") (pintype "bidirectional"))
      (node (ref "IC8") (pin "N1") (pinfunction "DCDC_GND_1_N1") (pintype "bidirectional"))
      (node (ref "IC8") (pin "N2") (pinfunction "DCDC_GND_2_N2") (pintype "bidirectional"))
      (node (ref "IC8") (pin "N5") (pinfunction "VSS_16_N5") (pintype "bidirectional"))
      (node (ref "IC8") (pin "N8") (pinfunction "VSS_17_N8") (pintype "bidirectional"))
      (node (ref "IC8") (pin "P1") (pinfunction "VSS_18_P1") (pintype "bidirectional"))
      (node (ref "IC8") (pin "P14") (pinfunction "VSS_19_P14") (pintype "bidirectional"))
      (node (ref "IC9") (pin "22") (pinfunction "GND_1_22") (pintype "bidirectional"))
      (node (ref "IC9") (pin "25") (pinfunction "GND_2_25") (pintype "bidirectional"))
      (node (ref "J1") (pin "A1_B12") (pinfunction "GND_A1_B12") (pintype "power_in"))
      (node (ref "J1") (pin "B1_A12") (pinfunction "GND_B1_A12") (pintype "power_in"))
      (node (ref "J3") (pin "1") (pinfunction "1_1") (pintype "passive"))
      (node (ref "J4") (pin "19") (pinfunction "19_19") (pintype "bidirectional"))
      (node (ref "J4") (pin "27") (pinfunction "27_27") (pintype "bidirectional"))
      (node (ref "J4") (pin "5") (pinfunction "5_5") (pintype "bidirectional"))
      (node (ref "J5") (pin "CD$2") (pinfunction "CD_POL_CD$2") (pintype "power_in"))
      (node (ref "J5") (pin "G$1") (pinfunction "SHD_G$1") (pintype "power_in"))
      (node (ref "J5") (pin "G$2") (pinfunction "SHD_G$2") (pintype "power_in"))
      (node (ref "J5") (pin "G$3") (pinfunction "SHD_G$3") (pintype "power_in"))
      (node (ref "J5") (pin "G$4") (pinfunction "SHD_G$4") (pintype "power_in"))
      (node (ref "J5") (pin "P$6") (pinfunction "VSS_P$6") (pintype "power_in"))
      (node (ref "J6") (pin "1") (pinfunction "1_1") (pintype "passive"))
      (node (ref "J7") (pin "2") (pinfunction "GND_1_2") (pintype "bidirectional"))
      (node (ref "J7") (pin "3") (pinfunction "GND_2_3") (pintype "bidirectional"))
      (node (ref "J8") (pin "3") (pinfunction "3_3") (pintype "passive"))
      (node (ref "J8") (pin "5") (pinfunction "5_5") (pintype "passive"))
      (node (ref "Q6") (pin "1") (pinfunction "G_1") (pintype "bidirectional"))
      (node (ref "R10") (pin "2") (pinfunction "2_2") (pintype "passive"))
      (node (ref "R11") (pin "2") (pinfunction "2_2") (pintype "passive"))
      (node (ref "R12") (pin "2") (pinfunction "2_2") (pintype "passive"))
      (node (ref "R27") (pin "2") (pinfunction "2_2") (pintype "passive"))
      (node (ref "R37") (pin "2") (pinfunction "2_2") (pintype "passive"))
      (node (ref "R38") (pin "2") (pinfunction "2_2") (pintype "passive"))
      (node (ref "R40") (pin "2") (pinfunction "2_2") (pintype "passive"))
      (node (ref "R41") (pin "2") (pinfunction "2_2") (pintype "passive"))
      (node (ref "R6") (pin "2") (pinfunction "2_2") (pintype "passive"))
      (node (ref "R7") (pin "2") (pinfunction "2_2") (pintype "passive"))
      (node (ref "R8") (pin "1") (pinfunction "1_1") (pintype "passive"))
      (node (ref "R9") (pin "2") (pinfunction "2_2") (pintype "passive"))
      (node (ref "U1") (pin "2") (pinfunction "GND_2") (pintype "bidirectional"))
      (node (ref "U1") (pin "EP") (pinfunction "GND_EP") (pintype "bidirectional"))
      (node (ref "U2") (pin "15") (pinfunction "SYSOFF_15") (pintype "input"))
      (node (ref "U2") (pin "17") (pinfunction "EXP_17") (pintype "power_in"))
      (node (ref "U2") (pin "4") (pinfunction "~{CE}_4") (pintype "input"))
      (node (ref "U2") (pin "6") (pinfunction "EN1_6") (pintype "input"))
      (node (ref "U2") (pin "8") (pinfunction "VSS_8") (pintype "power_in"))
      (node (ref "U3") (pin "1") (pinfunction "GND_1") (pintype "power_in"))
      (node (ref "U3") (pin "12") (pinfunction "GND_12") (pintype "power_in"))
      (node (ref "U3") (pin "19") (pinfunction "GND_19") (pintype "power_in"))
      (node (ref "U3") (pin "21") (pinfunction "GND_21") (pintype "power_in"))
      (node (ref "U3") (pin "29") (pinfunction "GND_29") (pintype "power_in"))
      (node (ref "U3") (pin "32") (pinfunction "GND_(SR_PVSS)_32") (pintype "power_in"))
      (node (ref "U3") (pin "33") (pinfunction "GND_(SR_PVSS)_33") (pintype "power_in"))
      (node (ref "U3") (pin "35") (pinfunction "GND_35") (pintype "power_in"))
      (node (ref "U3") (pin "37") (pinfunction "LPO_IN_(32KHZ)_37") (pintype "input"))
      (node (ref "U3") (pin "4") (pinfunction "~{BT_UART_CTS_N}_4") (pintype "input"))
      (node (ref "U3") (pin "40") (pinfunction "GND_40") (pintype "power_in"))
      (node (ref "U3") (pin "42") (pinfunction "GND_42") (pintype "power_in"))
      (node (ref "U3") (pin "43") (pinfunction "GND_43") (pintype "power_in"))
      (node (ref "U3") (pin "44") (pinfunction "GND_44") (pintype "power_in"))
      (node (ref "U3") (pin "45") (pinfunction "GND_45") (pintype "power_in"))
      (node (ref "U3") (pin "46") (pinfunction "GND_46") (pintype "power_in"))
      (node (ref "Y2") (pin "2") (pinfunction "NC_1_2") (pintype "bidirectional"))
      (node (ref "Y2") (pin "4") (pinfunction "NC_2_4") (pintype "bidirectional"))
    )
    (net (code "174") (name "Net-(ANT1-FEED)") (class "Default")
      (node (ref "ANT1") (pin "1") (pinfunction "FEED_1") (pintype "input"))
      (node (ref "C78") (pin "1") (pinfunction "1_1") (pintype "bidirectional"))
      (node (ref "L7") (pin "1") (pinfunction "1_1") (pintype "passive"))
    )
    (net (code "175") (name "Net-(C110-Pad2)") (class "Default")
      (node (ref "C110") (pin "2") (pinfunction "2_2") (pintype "passive"))
      (node (ref "J1") (pin "S1") (pinfunction "SHELL_GND_S1") (pintype "power_in"))
      (node (ref "J1") (pin "S2") (pinfunction "SHELL_GND_S2") (pintype "power_in"))
      (node (ref "J1") (pin "S3") (pinfunction "SHELL_GND_S3") (pintype "power_in"))
      (node (ref "J1") (pin "S4") (pinfunction "SHELL_GND_S4") (pintype "power_in"))
      (node (ref "R41") (pin "1") (pinfunction "1_1") (pintype "passive"))
    )
    (net (code "176") (name "Net-(CN1-2)") (class "Default")
      (node (ref "C8") (pin "2") (pinfunction "2_2") (pintype "passive"))
      (node (ref "CN1") (pin "1") (pinfunction "2_1") (pintype "passive"))
      (node (ref "D2") (pin "1") (pinfunction "1_1") (pintype "bidirectional"))
      (node (ref "U2") (pin "2") (pinfunction "BAT_2_2") (pintype "bidirectional"))
      (node (ref "U2") (pin "3") (pinfunction "BAT_3_3") (pintype "bidirectional"))
    )
    (net (code "177") (name "Net-(D1-BLUE)") (class "Default")
      (node (ref "D1") (pin "1") (pinfunction "BLUE_1") (pintype "passive"))
      (node (ref "R5") (pin "2") (pinfunction "2_2") (pintype "passive"))
    )
    (net (code "178") (name "Net-(D3-BLUE)") (class "Default")
      (node (ref "D3") (pin "1") (pinfunction "BLUE_1") (pintype "passive"))
      (node (ref "R19") (pin "2") (pinfunction "2_2") (pintype "passive"))
    )
    (net (code "179") (name "Net-(D3-GREEN)") (class "Default")
      (node (ref "D3") (pin "2") (pinfunction "GREEN_2") (pintype "passive"))
      (node (ref "R20") (pin "2") (pinfunction "2_2") (pintype "passive"))
    )
    (net (code "180") (name "Net-(D3-RED)") (class "Default")
      (node (ref "D3") (pin "3") (pinfunction "RED_3") (pintype "passive"))
      (node (ref "R21") (pin "2") (pinfunction "2_2") (pintype "passive"))
    )
    (net (code "181") (name "Net-(FL1-D+_1)") (class "Default")
      (node (ref "FL1") (pin "3") (pinfunction "D+_1_3") (pintype "bidirectional"))
      (node (ref "J1") (pin "A7") (pinfunction "DN1_A7") (pintype "bidirectional"))
      (node (ref "J1") (pin "B7") (pinfunction "DN2_B7") (pintype "bidirectional"))
    )
    (net (code "182") (name "Net-(FL1-D-_1)") (class "Default")
      (node (ref "FL1") (pin "2") (pinfunction "D-_1_2") (pintype "bidirectional"))
      (node (ref "J1") (pin "A6") (pinfunction "DP1_A6") (pintype "bidirectional"))
      (node (ref "J1") (pin "B6") (pinfunction "DP2_B6") (pintype "bidirectional"))
    )
    (net (code "183") (name "Net-(FL1-ID)") (class "Default")
      (node (ref "FL1") (pin "4") (pinfunction "ID_4") (pintype "bidirectional"))
      (node (ref "J1") (pin "A4_B9") (pinfunction "VBUS_A4_B9") (pintype "power_in"))
      (node (ref "J1") (pin "B4_A9") (pinfunction "VBUS_B4_A9") (pintype "power_in"))
      (node (ref "L1") (pin "1") (pinfunction "1_1") (pintype "passive"))
    )
    (net (code "184") (name "Net-(FL2-OUTPUT_1)") (class "Default")
      (node (ref "FL2") (pin "12") (pinfunction "OUTPUT_1_12") (pintype "bidirectional"))
      (node (ref "J2") (pin "8") (pinfunction "8_8") (pintype "passive"))
    )
    (net (code "185") (name "Net-(FL2-OUTPUT_2)") (class "Default")
      (node (ref "FL2") (pin "11") (pinfunction "OUTPUT_2_11") (pintype "bidirectional"))
      (node (ref "J2") (pin "7") (pinfunction "7_7") (pintype "passive"))
    )
    (net (code "186") (name "Net-(FL2-OUTPUT_3)") (class "Default")
      (node (ref "FL2") (pin "10") (pinfunction "OUTPUT_3_10") (pintype "bidirectional"))
      (node (ref "J2") (pin "6") (pinfunction "6_6") (pintype "passive"))
    )
    (net (code "187") (name "Net-(FL2-OUTPUT_4)") (class "Default")
      (node (ref "FL2") (pin "9") (pinfunction "OUTPUT_4_9") (pintype "bidirectional"))
      (node (ref "J2") (pin "5") (pinfunction "5_5") (pintype "passive"))
    )
    (net (code "188") (name "Net-(FL2-OUTPUT_5)") (class "Default")
      (node (ref "FL2") (pin "8") (pinfunction "OUTPUT_5_8") (pintype "bidirectional"))
      (node (ref "J2") (pin "4") (pinfunction "4_4") (pintype "passive"))
    )
    (net (code "189") (name "Net-(FL2-OUTPUT_6)") (class "Default")
      (node (ref "FL2") (pin "7") (pinfunction "OUTPUT_6_7") (pintype "bidirectional"))
      (node (ref "J2") (pin "3") (pinfunction "3_3") (pintype "passive"))
    )
    (net (code "190") (name "Net-(FL4-OUTPUT_1)") (class "Default")
      (node (ref "FL4") (pin "12") (pinfunction "OUTPUT_1_12") (pintype "bidirectional"))
      (node (ref "J2") (pin "2") (pinfunction "2_2") (pintype "passive"))
    )
    (net (code "191") (name "Net-(FL5-OUTPUT_6)") (class "Default")
      (node (ref "FL5") (pin "7") (pinfunction "OUTPUT_6_7") (pintype "bidirectional"))
      (node (ref "J8") (pin "9") (pinfunction "9_9") (pintype "passive"))
    )
    (net (code "192") (name "Net-(IC1-ST)") (class "Default")
      (node (ref "IC1") (pin "8") (pinfunction "ST_8") (pintype "bidirectional"))
      (node (ref "R5") (pin "1") (pinfunction "1_1") (pintype "passive"))
    )
    (net (code "193") (name "Net-(IC1-VIN2)") (class "Default")
      (node (ref "C5") (pin "2") (pinfunction "2_2") (pintype "passive"))
      (node (ref "IC1") (pin "6") (pinfunction "VIN2_6") (pintype "bidirectional"))
      (node (ref "Q6") (pin "2") (pinfunction "S_2") (pintype "bidirectional"))
    )
    (net (code "194") (name "Net-(IC2-EN)") (class "Default")
      (node (ref "IC2") (pin "5") (pinfunction "EN_5") (pintype "bidirectional"))
      (node (ref "Q1") (pin "3") (pinfunction "D_3") (pintype "bidirectional"))
      (node (ref "R3") (pin "1") (pinfunction "1_1") (pintype "passive"))
    )
    (net (code "195") (name "Net-(IC2-FB)") (class "Default")
      (node (ref "IC2") (pin "1") (pinfunction "FB_1") (pintype "bidirectional"))
      (node (ref "R2") (pin "1") (pinfunction "1_1") (pintype "passive"))
      (node (ref "R8") (pin "2") (pinfunction "2_2") (pintype "passive"))
    )
    (net (code "196") (name "Net-(IC2-SW)") (class "Default")
      (node (ref "IC2") (pin "4") (pinfunction "SW_4") (pintype "bidirectional"))
      (node (ref "L2") (pin "1") (pinfunction "1_1") (pintype "passive"))
    )
    (net (code "197") (name "Net-(IC9-LED0_{slash}_ANEN_SPEED)") (class "Default")
      (node (ref "IC9") (pin "23") (pinfunction "LED0_/_ANEN_SPEED_23") (pintype "bidirectional"))
      (node (ref "R35") (pin "1") (pinfunction "1_1") (pintype "passive"))
    )
    (net (code "198") (name "Net-(IC9-REXT)") (class "Default")
      (node (ref "IC9") (pin "9") (pinfunction "REXT_9") (pintype "bidirectional"))
      (node (ref "R38") (pin "1") (pinfunction "1_1") (pintype "passive"))
    )
    (net (code "199") (name "Net-(IC9-VDDA_3.3)") (class "Default")
      (node (ref "C81") (pin "2") (pinfunction "2_2") (pintype "passive"))
      (node (ref "C82") (pin "1") (pinfunction "1_1") (pintype "passive"))
      (node (ref "C85") (pin "1") (pinfunction "1_1") (pintype "passive"))
      (node (ref "IC9") (pin "2") (pinfunction "VDDA_3.3_2") (pintype "bidirectional"))
      (node (ref "L8") (pin "1") (pinfunction "1_1") (pintype "passive"))
    )
    (net (code "200") (name "Net-(IC9-VDD_1.2)") (class "Default")
      (node (ref "C83") (pin "2") (pinfunction "2_2") (pintype "passive"))
      (node (ref "C84") (pin "1") (pinfunction "1_1") (pintype "passive"))
      (node (ref "IC9") (pin "1") (pinfunction "VDD_1.2_1") (pintype "bidirectional"))
    )
    (net (code "201") (name "Net-(J1-CC1)") (class "Default")
      (node (ref "J1") (pin "A5") (pinfunction "CC1_A5") (pintype "bidirectional"))
      (node (ref "R6") (pin "1") (pinfunction "1_1") (pintype "passive"))
    )
    (net (code "202") (name "Net-(J1-CC2)") (class "Default")
      (node (ref "J1") (pin "B5") (pinfunction "CC2_B5") (pintype "bidirectional"))
      (node (ref "R7") (pin "1") (pinfunction "1_1") (pintype "passive"))
    )
    (net (code "203") (name "Net-(J7-SIGNAL)") (class "Default")
      (node (ref "C77") (pin "1") (pinfunction "1_1") (pintype "bidirectional"))
      (node (ref "J7") (pin "1") (pinfunction "SIGNAL_1") (pintype "bidirectional"))
      (node (ref "L7") (pin "2") (pinfunction "2_2") (pintype "passive"))
      (node (ref "U3") (pin "41") (pinfunction "ANT_41") (pintype "passive"))
    )
    (net (code "204") (name "Net-(U2-ILIM)") (class "Default")
      (node (ref "R10") (pin "1") (pinfunction "1_1") (pintype "passive"))
      (node (ref "U2") (pin "12") (pinfunction "ILIM_12") (pintype "input"))
    )
    (net (code "205") (name "Net-(U2-ISET)") (class "Default")
      (node (ref "R12") (pin "1") (pinfunction "1_1") (pintype "passive"))
      (node (ref "U2") (pin "16") (pinfunction "ISET_16") (pintype "bidirectional"))
    )
    (net (code "206") (name "Net-(U2-TMR)") (class "Default")
      (node (ref "R11") (pin "1") (pinfunction "1_1") (pintype "passive"))
      (node (ref "U2") (pin "14") (pinfunction "TMR_14") (pintype "input"))
    )
    (net (code "207") (name "Net-(U2-TS)") (class "Default")
      (node (ref "R9") (pin "1") (pinfunction "1_1") (pintype "passive"))
      (node (ref "U2") (pin "1") (pinfunction "TS_1") (pintype "input"))
    )
    (net (code "208") (name "Net-(U2-~{CHG})") (class "Default")
      (node (ref "R1") (pin "1") (pinfunction "1_1") (pintype "passive"))
      (node (ref "U2") (pin "9") (pinfunction "~{CHG}_9") (pintype "output"))
    )
    (net (code "209") (name "Net-(U2-~{PGOOD})") (class "Default")
      (node (ref "R4") (pin "1") (pinfunction "1_1") (pintype "passive"))
      (node (ref "U2") (pin "7") (pinfunction "~{PGOOD}_7") (pintype "output"))
    )
    (net (code "210") (name "Net-(U3-SR_VLX)") (class "Default")
      (node (ref "L9") (pin "1") (pinfunction "1_1") (pintype "passive"))
      (node (ref "U3") (pin "34") (pinfunction "SR_VLX_34") (pintype "output"))
    )
    (net (code "211") (name "Net-(U3-VIN_LDO)") (class "Default")
      (node (ref "C74") (pin "1") (pinfunction "1_1") (pintype "passive"))
      (node (ref "C91") (pin "2") (pinfunction "2_2") (pintype "passive"))
      (node (ref "L9") (pin "2") (pinfunction "2_2") (pintype "passive"))
      (node (ref "U3") (pin "31") (pinfunction "VIN_LDO_31") (pintype "power_in"))
    )
    (net (code "212") (name "RAW") (class "Default")
      (node (ref "C1") (pin "2") (pinfunction "2_2") (pintype "passive"))
      (node (ref "C4") (pin "2") (pinfunction "2_2") (pintype "passive"))
      (node (ref "C6") (pin "1") (pinfunction "1_1") (pintype "passive"))
      (node (ref "D1") (pin "4") (pinfunction "ANODE_4") (pintype "passive"))
      (node (ref "D5") (pin "1") (pinfunction "1_1") (pintype "bidirectional"))
      (node (ref "IC1") (pin "2") (pinfunction "VOUT_1_2") (pintype "bidirectional"))
      (node (ref "IC1") (pin "7") (pinfunction "VOUT_2_7") (pintype "bidirectional"))
      (node (ref "IC2") (pin "3") (pinfunction "VIN_3") (pintype "bidirectional"))
      (node (ref "J3") (pin "2") (pinfunction "2_2") (pintype "passive"))
      (node (ref "Q1") (pin "1") (pinfunction "G_1") (pintype "bidirectional"))
      (node (ref "Q2") (pin "1") (pinfunction "G_1") (pintype "bidirectional"))
      (node (ref "Q3") (pin "1") (pinfunction "G_1") (pintype "bidirectional"))
      (node (ref "R22") (pin "2") (pinfunction "2_2") (pintype "passive"))
      (node (ref "R23") (pin "2") (pinfunction "2_2") (pintype "passive"))
      (node (ref "R3") (pin "2") (pinfunction "2_2") (pintype "passive"))
      (node (ref "U1") (pin "3") (pinfunction "EN_3") (pintype "bidirectional"))
      (node (ref "U1") (pin "4") (pinfunction "VIN_4") (pintype "bidirectional"))
    )
    (net (code "213") (name "VBUS") (class "Default")
      (node (ref "C88") (pin "1") (pinfunction "1_1") (pintype "passive"))
      (node (ref "C9") (pin "2") (pinfunction "2_2") (pintype "passive"))
      (node (ref "C95") (pin "2") (pinfunction "2_2") (pintype "passive"))
      (node (ref "FL1") (pin "1") (pinfunction "VBUS_1") (pintype "bidirectional"))
      (node (ref "IC8") (pin "N6") (pinfunction "USB_OTG1_VBUS_N6") (pintype "bidirectional"))
      (node (ref "L1") (pin "2") (pinfunction "2_2") (pintype "passive"))
      (node (ref "U2") (pin "13") (pinfunction "IN_13") (pintype "input"))
    )
    (net (code "214") (name "VCC") (class "Default")
      (node (ref "C108") (pin "2") (pinfunction "2_2") (pintype "passive"))
      (node (ref "C109") (pin "1") (pinfunction "1_1") (pintype "passive"))
      (node (ref "C11") (pin "2") (pinfunction "2_2") (pintype "passive"))
      (node (ref "C12") (pin "1") (pinfunction "1_1") (pintype "passive"))
      (node (ref "C13") (pin "1") (pinfunction "1_1") (pintype "passive"))
      (node (ref "C14") (pin "1") (pinfunction "1_1") (pintype "passive"))
      (node (ref "C15") (pin "1") (pinfunction "1_1") (pintype "passive"))
      (node (ref "C16") (pin "1") (pinfunction "1_1") (pintype "passive"))
      (node (ref "C17") (pin "2") (pinfunction "2_2") (pintype "passive"))
      (node (ref "C18") (pin "2") (pinfunction "2_2") (pintype "passive"))
      (node (ref "C19") (pin "1") (pinfunction "1_1") (pintype "passive"))
      (node (ref "C20") (pin "1") (pinfunction "1_1") (pintype "passive"))
      (node (ref "C21") (pin "2") (pinfunction "2_2") (pintype "passive"))
      (node (ref "C22") (pin "1") (pinfunction "1_1") (pintype "passive"))
      (node (ref "C23") (pin "2") (pinfunction "2_2") (pintype "passive"))
      (node (ref "C24") (pin "1") (pinfunction "1_1") (pintype "passive"))
      (node (ref "C25") (pin "2") (pinfunction "2_2") (pintype "passive"))
      (node (ref "C26") (pin "1") (pinfunction "1_1") (pintype "passive"))
      (node (ref "C27") (pin "2") (pinfunction "2_2") (pintype "passive"))
      (node (ref "C28") (pin "1") (pinfunction "1_1") (pintype "passive"))
      (node (ref "C29") (pin "1") (pinfunction "1_1") (pintype "passive"))
      (node (ref "C30") (pin "1") (pinfunction "1_1") (pintype "passive"))
      (node (ref "C31") (pin "2") (pinfunction "2_2") (pintype "passive"))
      (node (ref "C32") (pin "1") (pinfunction "1_1") (pintype "passive"))
      (node (ref "C33") (pin "2") (pinfunction "2_2") (pintype "passive"))
      (node (ref "C35") (pin "2") (pinfunction "2_2") (pintype "passive"))
      (node (ref "C36") (pin "1") (pinfunction "1_1") (pintype "passive"))
      (node (ref "C37") (pin "1") (pinfunction "1_1") (pintype "passive"))
      (node (ref "C39") (pin "2") (pinfunction "2_2") (pintype "passive"))
      (node (ref "C40") (pin "2") (pinfunction "2_2") (pintype "passive"))
      (node (ref "C41") (pin "2") (pinfunction "2_2") (pintype "passive"))
      (node (ref "C42") (pin "2") (pinfunction "2_2") (pintype "passive"))
      (node (ref "C43") (pin "1") (pinfunction "1_1") (pintype "passive"))
      (node (ref "C44") (pin "2") (pinfunction "2_2") (pintype "passive"))
      (node (ref "C50") (pin "1") (pinfunction "1_1") (pintype "passive"))
      (node (ref "C53") (pin "1") (pinfunction "1_1") (pintype "passive"))
      (node (ref "C54") (pin "1") (pinfunction "1_1") (pintype "passive"))
      (node (ref "C55") (pin "1") (pinfunction "1_1") (pintype "passive"))
      (node (ref "C56") (pin "1") (pinfunction "1_1") (pintype "passive"))
      (node (ref "C57") (pin "2") (pinfunction "2_2") (pintype "passive"))
      (node (ref "C58") (pin "2") (pinfunction "2_2") (pintype "passive"))
      (node (ref "C64") (pin "1") (pinfunction "1_1") (pintype "passive"))
      (node (ref "C66") (pin "2") (pinfunction "2_2") (pintype "passive"))
      (node (ref "C67") (pin "1") (pinfunction "1_1") (pintype "passive"))
      (node (ref "C68") (pin "2") (pinfunction "2_2") (pintype "passive"))
      (node (ref "C7") (pin "1") (pinfunction "1_1") (pintype "passive"))
      (node (ref "C75") (pin "1") (pinfunction "1_1") (pintype "passive"))
      (node (ref "C76") (pin "1") (pinfunction "1_1") (pintype "passive"))
      (node (ref "C86") (pin "2") (pinfunction "2_2") (pintype "passive"))
      (node (ref "C89") (pin "1") (pinfunction "1_1") (pintype "passive"))
      (node (ref "C90") (pin "2") (pinfunction "2_2") (pintype "passive"))
      (node (ref "C92") (pin "2") (pinfunction "2_2") (pintype "passive"))
      (node (ref "C93") (pin "2") (pinfunction "2_2") (pintype "passive"))
      (node (ref "C96") (pin "1") (pinfunction "1_1") (pintype "passive"))
      (node (ref "C99") (pin "2") (pinfunction "2_2") (pintype "passive"))
      (node (ref "D10") (pin "1") (pinfunction "1_1") (pintype "bidirectional"))
      (node (ref "D3") (pin "4") (pinfunction "ANODE_4") (pintype "passive"))
      (node (ref "D4") (pin "1") (pinfunction "1_1") (pintype "bidirectional"))
      (node (ref "D6") (pin "1") (pinfunction "1_1") (pintype "bidirectional"))
      (node (ref "IC2") (pin "6") (pinfunction "OUT_6") (pintype "bidirectional"))
      (node (ref "IC3") (pin "A7") (pinfunction "VDDQ_1_A7") (pintype "bidirectional"))
      (node (ref "IC3") (pin "A9") (pinfunction "VDD_1_A9") (pintype "bidirectional"))
      (node (ref "IC3") (pin "B3") (pinfunction "VDDQ_2_B3") (pintype "bidirectional"))
      (node (ref "IC3") (pin "C7") (pinfunction "VDDQ_3_C7") (pintype "bidirectional"))
      (node (ref "IC3") (pin "D3") (pinfunction "VDDQ_4_D3") (pintype "bidirectional"))
      (node (ref "IC3") (pin "E7") (pinfunction "VDD_2_E7") (pintype "bidirectional"))
      (node (ref "IC3") (pin "J9") (pinfunction "VDD_3_J9") (pintype "bidirectional"))
      (node (ref "IC4") (pin "8") (pinfunction "VCC_8") (pintype "bidirectional"))
      (node (ref "IC5") (pin "8") (pinfunction "VCC_8") (pintype "bidirectional"))
      (node (ref "IC6") (pin "8") (pinfunction "VCC_8") (pintype "bidirectional"))
      (node (ref "IC7") (pin "6") (pinfunction "VDD_6") (pintype "bidirectional"))
      (node (ref "IC8") (pin "E6") (pinfunction "NVCC_EMC_1_E6") (pintype "bidirectional"))
      (node (ref "IC8") (pin "E9") (pinfunction "NVCC_GPIO_1_E9") (pintype "bidirectional"))
      (node (ref "IC8") (pin "F10") (pinfunction "NVCC_GPIO_2_F10") (pintype "bidirectional"))
      (node (ref "IC8") (pin "F5") (pinfunction "NVCC_EMC_2_F5") (pintype "bidirectional"))
      (node (ref "IC8") (pin "J10") (pinfunction "NVCC_GPIO_3_J10") (pintype "bidirectional"))
      (node (ref "IC8") (pin "J6") (pinfunction "NVCC_SD0_J6") (pintype "bidirectional"))
      (node (ref "IC8") (pin "K4") (pinfunction "DCDC_IN_Q_K4") (pintype "bidirectional"))
      (node (ref "IC8") (pin "K5") (pinfunction "NVCC_SD1_K5") (pintype "bidirectional"))
      (node (ref "IC8") (pin "L1") (pinfunction "DCDC_IN_1_L1") (pintype "bidirectional"))
      (node (ref "IC8") (pin "L2") (pinfunction "DCDC_IN_2_L2") (pintype "bidirectional"))
      (node (ref "IC8") (pin "P12") (pinfunction "VDD_HIGH_IN_P12") (pintype "bidirectional"))
      (node (ref "IC9") (pin "14") (pinfunction "VDDIO_14") (pintype "bidirectional"))
      (node (ref "J2") (pin "1") (pinfunction "1_1") (pintype "passive"))
      (node (ref "J4") (pin "10") (pinfunction "10_10") (pintype "bidirectional"))
      (node (ref "J4") (pin "2") (pinfunction "2_2") (pintype "bidirectional"))
      (node (ref "J4") (pin "20") (pinfunction "20_20") (pintype "bidirectional"))
      (node (ref "J4") (pin "30") (pinfunction "30_30") (pintype "bidirectional"))
      (node (ref "J4") (pin "36") (pinfunction "36_36") (pintype "bidirectional"))
      (node (ref "J5") (pin "P$4") (pinfunction "VDD_P$4") (pintype "power_in"))
      (node (ref "J8") (pin "1") (pinfunction "1_1") (pintype "passive"))
      (node (ref "L2") (pin "2") (pinfunction "2_2") (pintype "passive"))
      (node (ref "L4") (pin "2") (pinfunction "2_2") (pintype "passive"))
      (node (ref "L6") (pin "2") (pinfunction "2_2") (pintype "passive"))
      (node (ref "L8") (pin "2") (pinfunction "2_2") (pintype "passive"))
      (node (ref "Q4") (pin "1") (pinfunction "G_1") (pintype "bidirectional"))
      (node (ref "Q5") (pin "1") (pinfunction "G_1") (pintype "bidirectional"))
      (node (ref "R13") (pin "1") (pinfunction "1_1") (pintype "passive"))
      (node (ref "R14") (pin "1") (pinfunction "1_1") (pintype "passive"))
      (node (ref "R15") (pin "2") (pinfunction "2_2") (pintype "passive"))
      (node (ref "R16") (pin "2") (pinfunction "2_2") (pintype "passive"))
      (node (ref "R17") (pin "2") (pinfunction "2_2") (pintype "passive"))
      (node (ref "R18") (pin "1") (pinfunction "1_1") (pintype "passive"))
      (node (ref "R2") (pin "2") (pinfunction "2_2") (pintype "passive"))
      (node (ref "R24") (pin "2") (pinfunction "2_2") (pintype "passive"))
      (node (ref "R25") (pin "2") (pinfunction "2_2") (pintype "passive"))
      (node (ref "R26") (pin "2") (pinfunction "2_2") (pintype "passive"))
      (node (ref "R28") (pin "2") (pinfunction "2_2") (pintype "passive"))
      (node (ref "R29") (pin "2") (pinfunction "2_2") (pintype "passive"))
      (node (ref "R30") (pin "2") (pinfunction "2_2") (pintype "passive"))
      (node (ref "R31") (pin "2") (pinfunction "2_2") (pintype "passive"))
      (node (ref "R32") (pin "2") (pinfunction "2_2") (pintype "passive"))
      (node (ref "R33") (pin "1") (pinfunction "1_1") (pintype "passive"))
      (node (ref "R34") (pin "2") (pinfunction "2_2") (pintype "passive"))
      (node (ref "R36") (pin "2") (pinfunction "2_2") (pintype "passive"))
      (node (ref "R39") (pin "2") (pinfunction "2_2") (pintype "passive"))
      (node (ref "RN1") (pin "1") (pinfunction "1_1") (pintype "bidirectional"))
      (node (ref "RN1") (pin "2") (pinfunction "2_2") (pintype "bidirectional"))
      (node (ref "RN1") (pin "3") (pinfunction "3_3") (pintype "bidirectional"))
      (node (ref "RN1") (pin "4") (pinfunction "4_4") (pintype "bidirectional"))
      (node (ref "RN1") (pin "5") (pinfunction "5_5") (pintype "bidirectional"))
      (node (ref "RN1") (pin "6") (pinfunction "6_6") (pintype "bidirectional"))
      (node (ref "RN1") (pin "7") (pinfunction "7_7") (pintype "bidirectional"))
      (node (ref "RN1") (pin "8") (pinfunction "8_8") (pintype "bidirectional"))
      (node (ref "RN2") (pin "1") (pinfunction "1_1") (pintype "bidirectional"))
      (node (ref "RN2") (pin "2") (pinfunction "2_2") (pintype "bidirectional"))
      (node (ref "RN2") (pin "3") (pinfunction "3_3") (pintype "bidirectional"))
      (node (ref "RN2") (pin "4") (pinfunction "4_4") (pintype "bidirectional"))
      (node (ref "RN2") (pin "5") (pinfunction "5_5") (pintype "bidirectional"))
      (node (ref "RN2") (pin "6") (pinfunction "6_6") (pintype "bidirectional"))
      (node (ref "RN2") (pin "7") (pinfunction "7_7") (pintype "bidirectional"))
      (node (ref "RN2") (pin "8") (pinfunction "8_8") (pintype "bidirectional"))
      (node (ref "U3") (pin "30") (pinfunction "VBAT_30") (pintype "power_in"))
      (node (ref "U3") (pin "36") (pinfunction "VIO_36") (pintype "power_in"))
    )
    (net (code "215") (name "VIN") (class "Default")
      (node (ref "D7") (pin "1") (pinfunction "1_1") (pintype "bidirectional"))
      (node (ref "J6") (pin "2") (pinfunction "2_2") (pintype "passive"))
      (node (ref "Q6") (pin "3") (pinfunction "D_3") (pintype "bidirectional"))
    )
    (net (code "216") (name "V_BATT") (class "Default")
      (node (ref "C10") (pin "2") (pinfunction "2_2") (pintype "passive"))
      (node (ref "C3") (pin "2") (pinfunction "2_2") (pintype "passive"))
      (node (ref "IC1") (pin "3") (pinfunction "VIN1_3") (pintype "bidirectional"))
      (node (ref "U2") (pin "10") (pinfunction "OUT_10_10") (pintype "output"))
      (node (ref "U2") (pin "11") (pinfunction "OUT_11_11") (pintype "output"))
      (node (ref "U2") (pin "5") (pinfunction "EN2_5") (pintype "input"))
    )
    (net (code "217") (name "unconnected-(ANT1-NC-Pad2)") (class "Default")
      (node (ref "ANT1") (pin "2") (pinfunction "NC_2") (pintype "no_connect"))
    )
    (net (code "218") (name "unconnected-(FL1-Pad9)") (class "Default")
      (node (ref "FL1") (pin "9") (pinfunction "9_9") (pintype "bidirectional"))
    )
    (net (code "219") (name "unconnected-(FL1-Pad10)") (class "Default")
      (node (ref "FL1") (pin "10") (pinfunction "10_10") (pintype "bidirectional"))
    )
    (net (code "220") (name "unconnected-(FL1-Pad11)") (class "Default")
      (node (ref "FL1") (pin "11") (pinfunction "11_11") (pintype "bidirectional"))
    )
    (net (code "221") (name "unconnected-(FL1-Pad12)") (class "Default")
      (node (ref "FL1") (pin "12") (pinfunction "12_12") (pintype "bidirectional"))
    )
    (net (code "222") (name "unconnected-(H1-MOUNT-PadB2,8)") (class "Default")
      (node (ref "H1") (pin "B2,8") (pinfunction "MOUNT_B2,8") (pintype "passive"))
    )
    (net (code "223") (name "unconnected-(H2-MOUNT-PadB2,8)") (class "Default")
      (node (ref "H2") (pin "B2,8") (pinfunction "MOUNT_B2,8") (pintype "passive"))
    )
    (net (code "224") (name "unconnected-(IC3-NC-PadE2)") (class "Default")
      (node (ref "IC3") (pin "E2") (pinfunction "NC_E2") (pintype "no_connect"))
    )
    (net (code "225") (name "unconnected-(IC4-NC_1-Pad1)") (class "Default")
      (node (ref "IC4") (pin "1") (pinfunction "NC_1_1") (pintype "bidirectional"))
    )
    (net (code "226") (name "unconnected-(IC4-NC_2-Pad2)") (class "Default")
      (node (ref "IC4") (pin "2") (pinfunction "NC_2_2") (pintype "bidirectional"))
    )
    (net (code "227") (name "unconnected-(IC4-NC_3-Pad3)") (class "Default")
      (node (ref "IC4") (pin "3") (pinfunction "NC_3_3") (pintype "bidirectional"))
    )
    (net (code "228") (name "unconnected-(IC4-NC_4-Pad7)") (class "Default")
      (node (ref "IC4") (pin "7") (pinfunction "NC_4_7") (pintype "bidirectional"))
    )
    (net (code "229") (name "unconnected-(IC7-NC-Pad2)") (class "Default")
      (node (ref "IC7") (pin "2") (pinfunction "NC_2") (pintype "no_connect"))
    )
    (net (code "230") (name "unconnected-(IC8-CCM_CLK1_N-PadP13)") (class "Default")
      (node (ref "IC8") (pin "P13") (pinfunction "CCM_CLK1_N_P13") (pintype "bidirectional"))
    )
    (net (code "231") (name "unconnected-(IC8-CCM_CLK1_P-PadN13)") (class "Default")
      (node (ref "IC8") (pin "N13") (pinfunction "CCM_CLK1_P_N13") (pintype "bidirectional"))
    )
    (net (code "232") (name "unconnected-(IC8-GPANAIO-PadN10)") (class "Default")
      (node (ref "IC8") (pin "N10") (pinfunction "GPANAIO_N10") (pintype "bidirectional"))
    )
    (net (code "233") (name "unconnected-(IC8-USB_OTG1_CHD_B-PadN12)") (class "Default")
      (node (ref "IC8") (pin "N12") (pinfunction "USB_OTG1_CHD_B_N12") (pintype "bidirectional"))
    )
    (net (code "234") (name "unconnected-(IC8-USB_OTG2_DN-PadN7)") (class "Default")
      (node (ref "IC8") (pin "N7") (pinfunction "USB_OTG2_DN_N7") (pintype "bidirectional"))
    )
    (net (code "235") (name "unconnected-(IC8-USB_OTG2_DP-PadP7)") (class "Default")
      (node (ref "IC8") (pin "P7") (pinfunction "USB_OTG2_DP_P7") (pintype "bidirectional"))
    )
    (net (code "236") (name "unconnected-(IC8-USB_OTG2_VBUS-PadP6)") (class "Default")
      (node (ref "IC8") (pin "P6") (pinfunction "USB_OTG2_VBUS_P6") (pintype "bidirectional"))
    )
    (net (code "237") (name "unconnected-(IC9-REF_CLK-Pad16)") (class "Default")
      (node (ref "IC9") (pin "16") (pinfunction "REF_CLK_16") (pintype "bidirectional"))
    )
    (net (code "238") (name "unconnected-(IC9-XO-Pad7)") (class "Default")
      (node (ref "IC9") (pin "7") (pinfunction "XO_7") (pintype "bidirectional"))
    )
    (net (code "239") (name "unconnected-(J1-SBU1-PadA8)") (class "Default")
      (node (ref "J1") (pin "A8") (pinfunction "SBU1_A8") (pintype "bidirectional"))
    )
    (net (code "240") (name "unconnected-(J1-SBU2-PadB8)") (class "Default")
      (node (ref "J1") (pin "B8") (pinfunction "SBU2_B8") (pintype "bidirectional"))
    )
    (net (code "241") (name "unconnected-(J4-Pad1)") (class "Default")
      (node (ref "J4") (pin "1") (pinfunction "1_1") (pintype "bidirectional"))
    )
    (net (code "242") (name "unconnected-(J4-Pad3)") (class "Default")
      (node (ref "J4") (pin "3") (pinfunction "3_3") (pintype "bidirectional"))
    )
    (net (code "243") (name "unconnected-(J4-Pad6)") (class "Default")
      (node (ref "J4") (pin "6") (pinfunction "6_6") (pintype "bidirectional"))
    )
    (net (code "244") (name "unconnected-(J4-Pad7)") (class "Default")
      (node (ref "J4") (pin "7") (pinfunction "7_7") (pintype "bidirectional"))
    )
    (net (code "245") (name "unconnected-(J4-Pad8)") (class "Default")
      (node (ref "J4") (pin "8") (pinfunction "8_8") (pintype "bidirectional"))
    )
    (net (code "246") (name "unconnected-(J4-Pad9)") (class "Default")
      (node (ref "J4") (pin "9") (pinfunction "9_9") (pintype "bidirectional"))
    )
    (net (code "247") (name "unconnected-(J8-Pad7)") (class "Default")
      (node (ref "J8") (pin "7") (pinfunction "7_7") (pintype "passive"))
    )
    (net (code "248") (name "unconnected-(RN1-Pad15)") (class "Default")
      (node (ref "RN1") (pin "15") (pinfunction "15_15") (pintype "bidirectional"))
    )
    (net (code "249") (name "unconnected-(RN1-Pad16)") (class "Default")
      (node (ref "RN1") (pin "16") (pinfunction "16_16") (pintype "bidirectional"))
    )
    (net (code "250") (name "unconnected-(RN2-Pad9)") (class "Default")
      (node (ref "RN2") (pin "9") (pinfunction "9_9") (pintype "bidirectional"))
    )
    (net (code "251") (name "unconnected-(RN2-Pad10)") (class "Default")
      (node (ref "RN2") (pin "10") (pinfunction "10_10") (pintype "bidirectional"))
    )
    (net (code "252") (name "unconnected-(RN2-Pad11)") (class "Default")
      (node (ref "RN2") (pin "11") (pinfunction "11_11") (pintype "bidirectional"))
    )
    (net (code "253") (name "unconnected-(U3-BT_GPIO_3-Pad6)") (class "Default")
      (node (ref "U3") (pin "6") (pinfunction "BT_GPIO_3_6") (pintype "bidirectional"))
    )
    (net (code "254") (name "unconnected-(U3-BT_GPIO_4-Pad7)") (class "Default")
      (node (ref "U3") (pin "7") (pinfunction "BT_GPIO_4_7") (pintype "bidirectional"))
    )
    (net (code "255") (name "unconnected-(U3-BT_GPIO_5-Pad13)") (class "Default")
      (node (ref "U3") (pin "13") (pinfunction "BT_GPIO_5_13") (pintype "bidirectional"))
    )
    (net (code "256") (name "unconnected-(U3-BT_I2S_DO-Pad16)") (class "Default")
      (node (ref "U3") (pin "16") (pinfunction "BT_I2S_DO_16") (pintype "bidirectional"))
    )
    (net (code "257") (name "unconnected-(U3-BT_PCM_CLK-Pad11)") (class "Default")
      (node (ref "U3") (pin "11") (pinfunction "BT_PCM_CLK_11") (pintype "bidirectional"))
    )
    (net (code "258") (name "unconnected-(U3-BT_PCM_IN-Pad9)") (class "Default")
      (node (ref "U3") (pin "9") (pinfunction "BT_PCM_IN_9") (pintype "input"))
    )
    (net (code "259") (name "unconnected-(U3-BT_PCM_OUT-Pad10)") (class "Default")
      (node (ref "U3") (pin "10") (pinfunction "BT_PCM_OUT_10") (pintype "output"))
    )
    (net (code "260") (name "unconnected-(U3-BT_PCM_SYNC-Pad8)") (class "Default")
      (node (ref "U3") (pin "8") (pinfunction "BT_PCM_SYNC_8") (pintype "bidirectional"))
    )
    (net (code "261") (name "unconnected-(U3-WL_GPIO_1-Pad18)") (class "Default")
      (node (ref "U3") (pin "18") (pinfunction "WL_GPIO_1_18") (pintype "bidirectional"))
    )
    (net (code "262") (name "unconnected-(U3-WL_GPIO_2-Pad17)") (class "Default")
      (node (ref "U3") (pin "17") (pinfunction "WL_GPIO_2_17") (pintype "bidirectional"))
    )
    (net (code "263") (name "unconnected-(U3-WL_GPIO_4-Pad15)") (class "Default")
      (node (ref "U3") (pin "15") (pinfunction "WL_GPIO_4_15") (pintype "bidirectional"))
    )
    (net (code "264") (name "unconnected-(U3-~{BT_UART_RTS_N}-Pad5)") (class "Default")
      (node (ref "U3") (pin "5") (pinfunction "~{BT_UART_RTS_N}_5") (pintype "output"))
    )
  )
)
